# Buck-15.net
KiCad netlist of a schematic drawn in Altium Designer
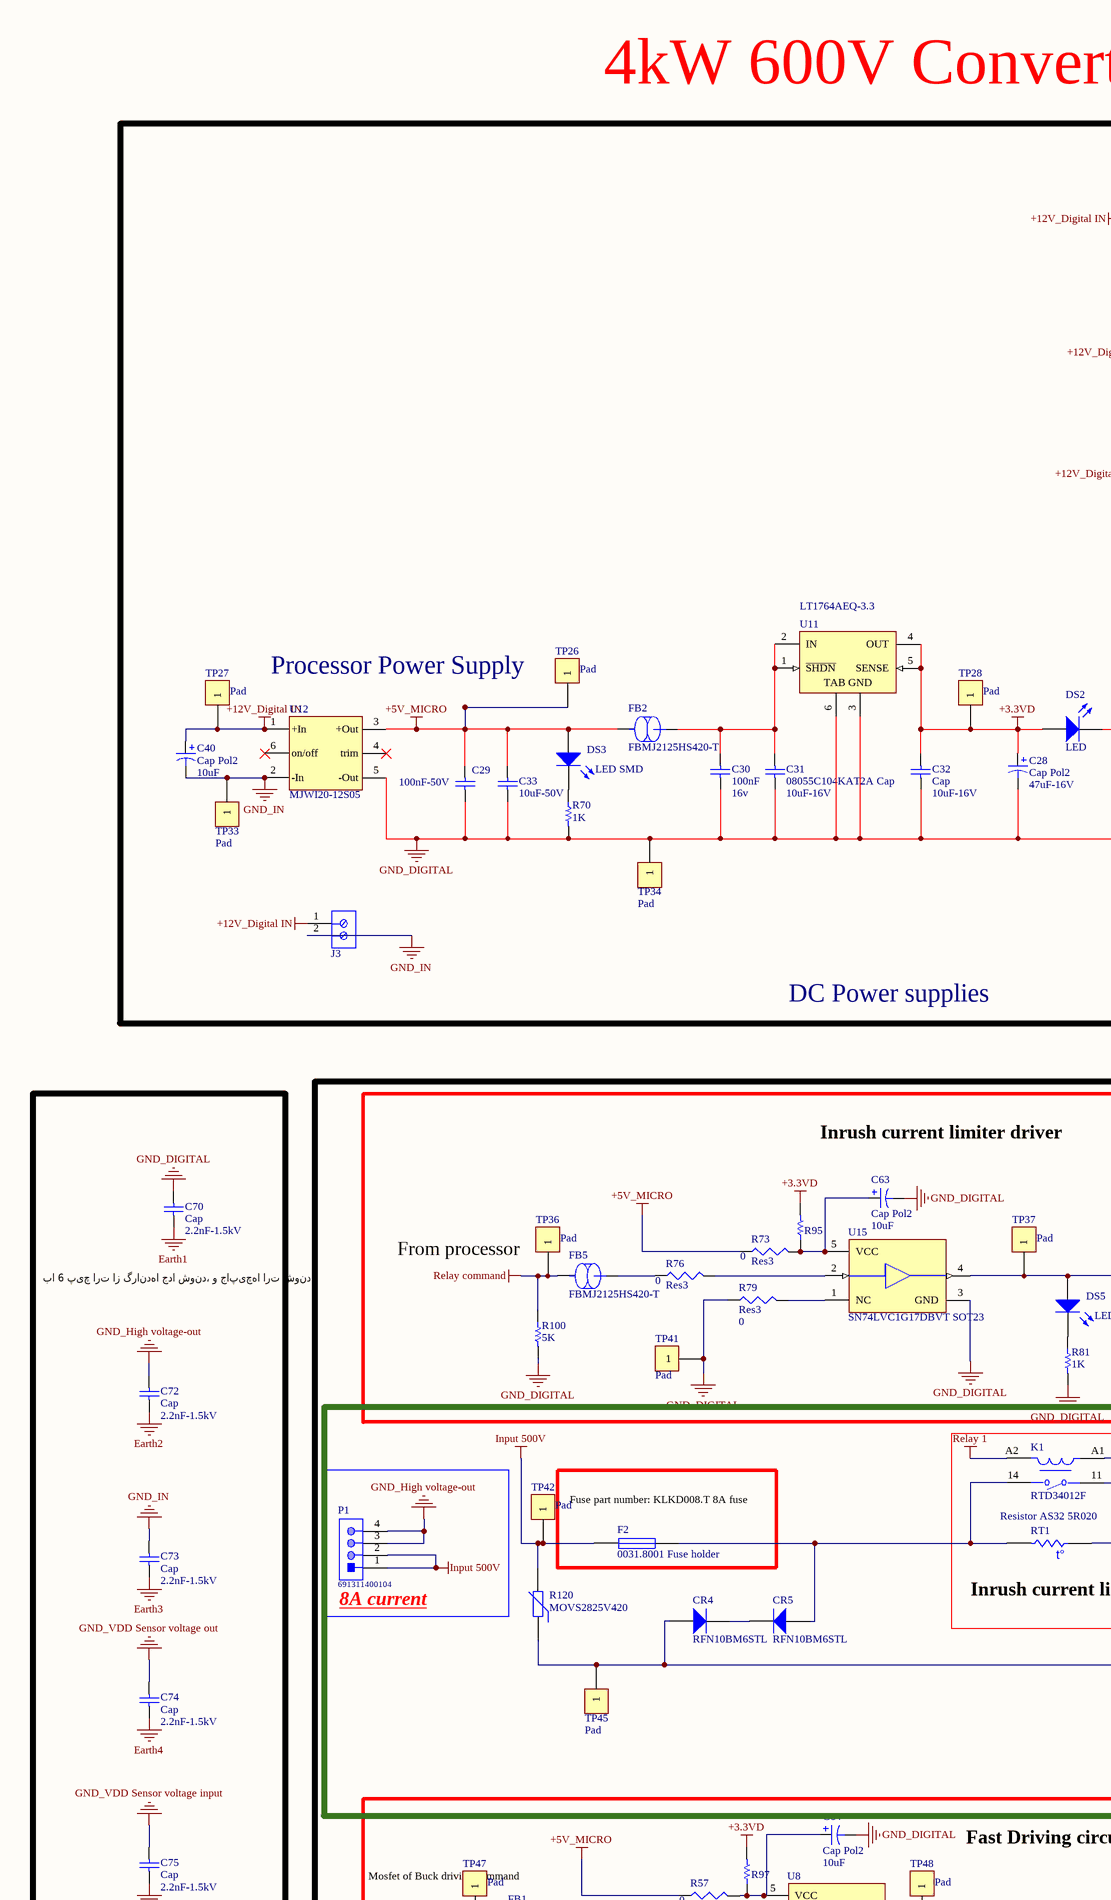
[diagram p0: Buck-15.SchDoc, top left]
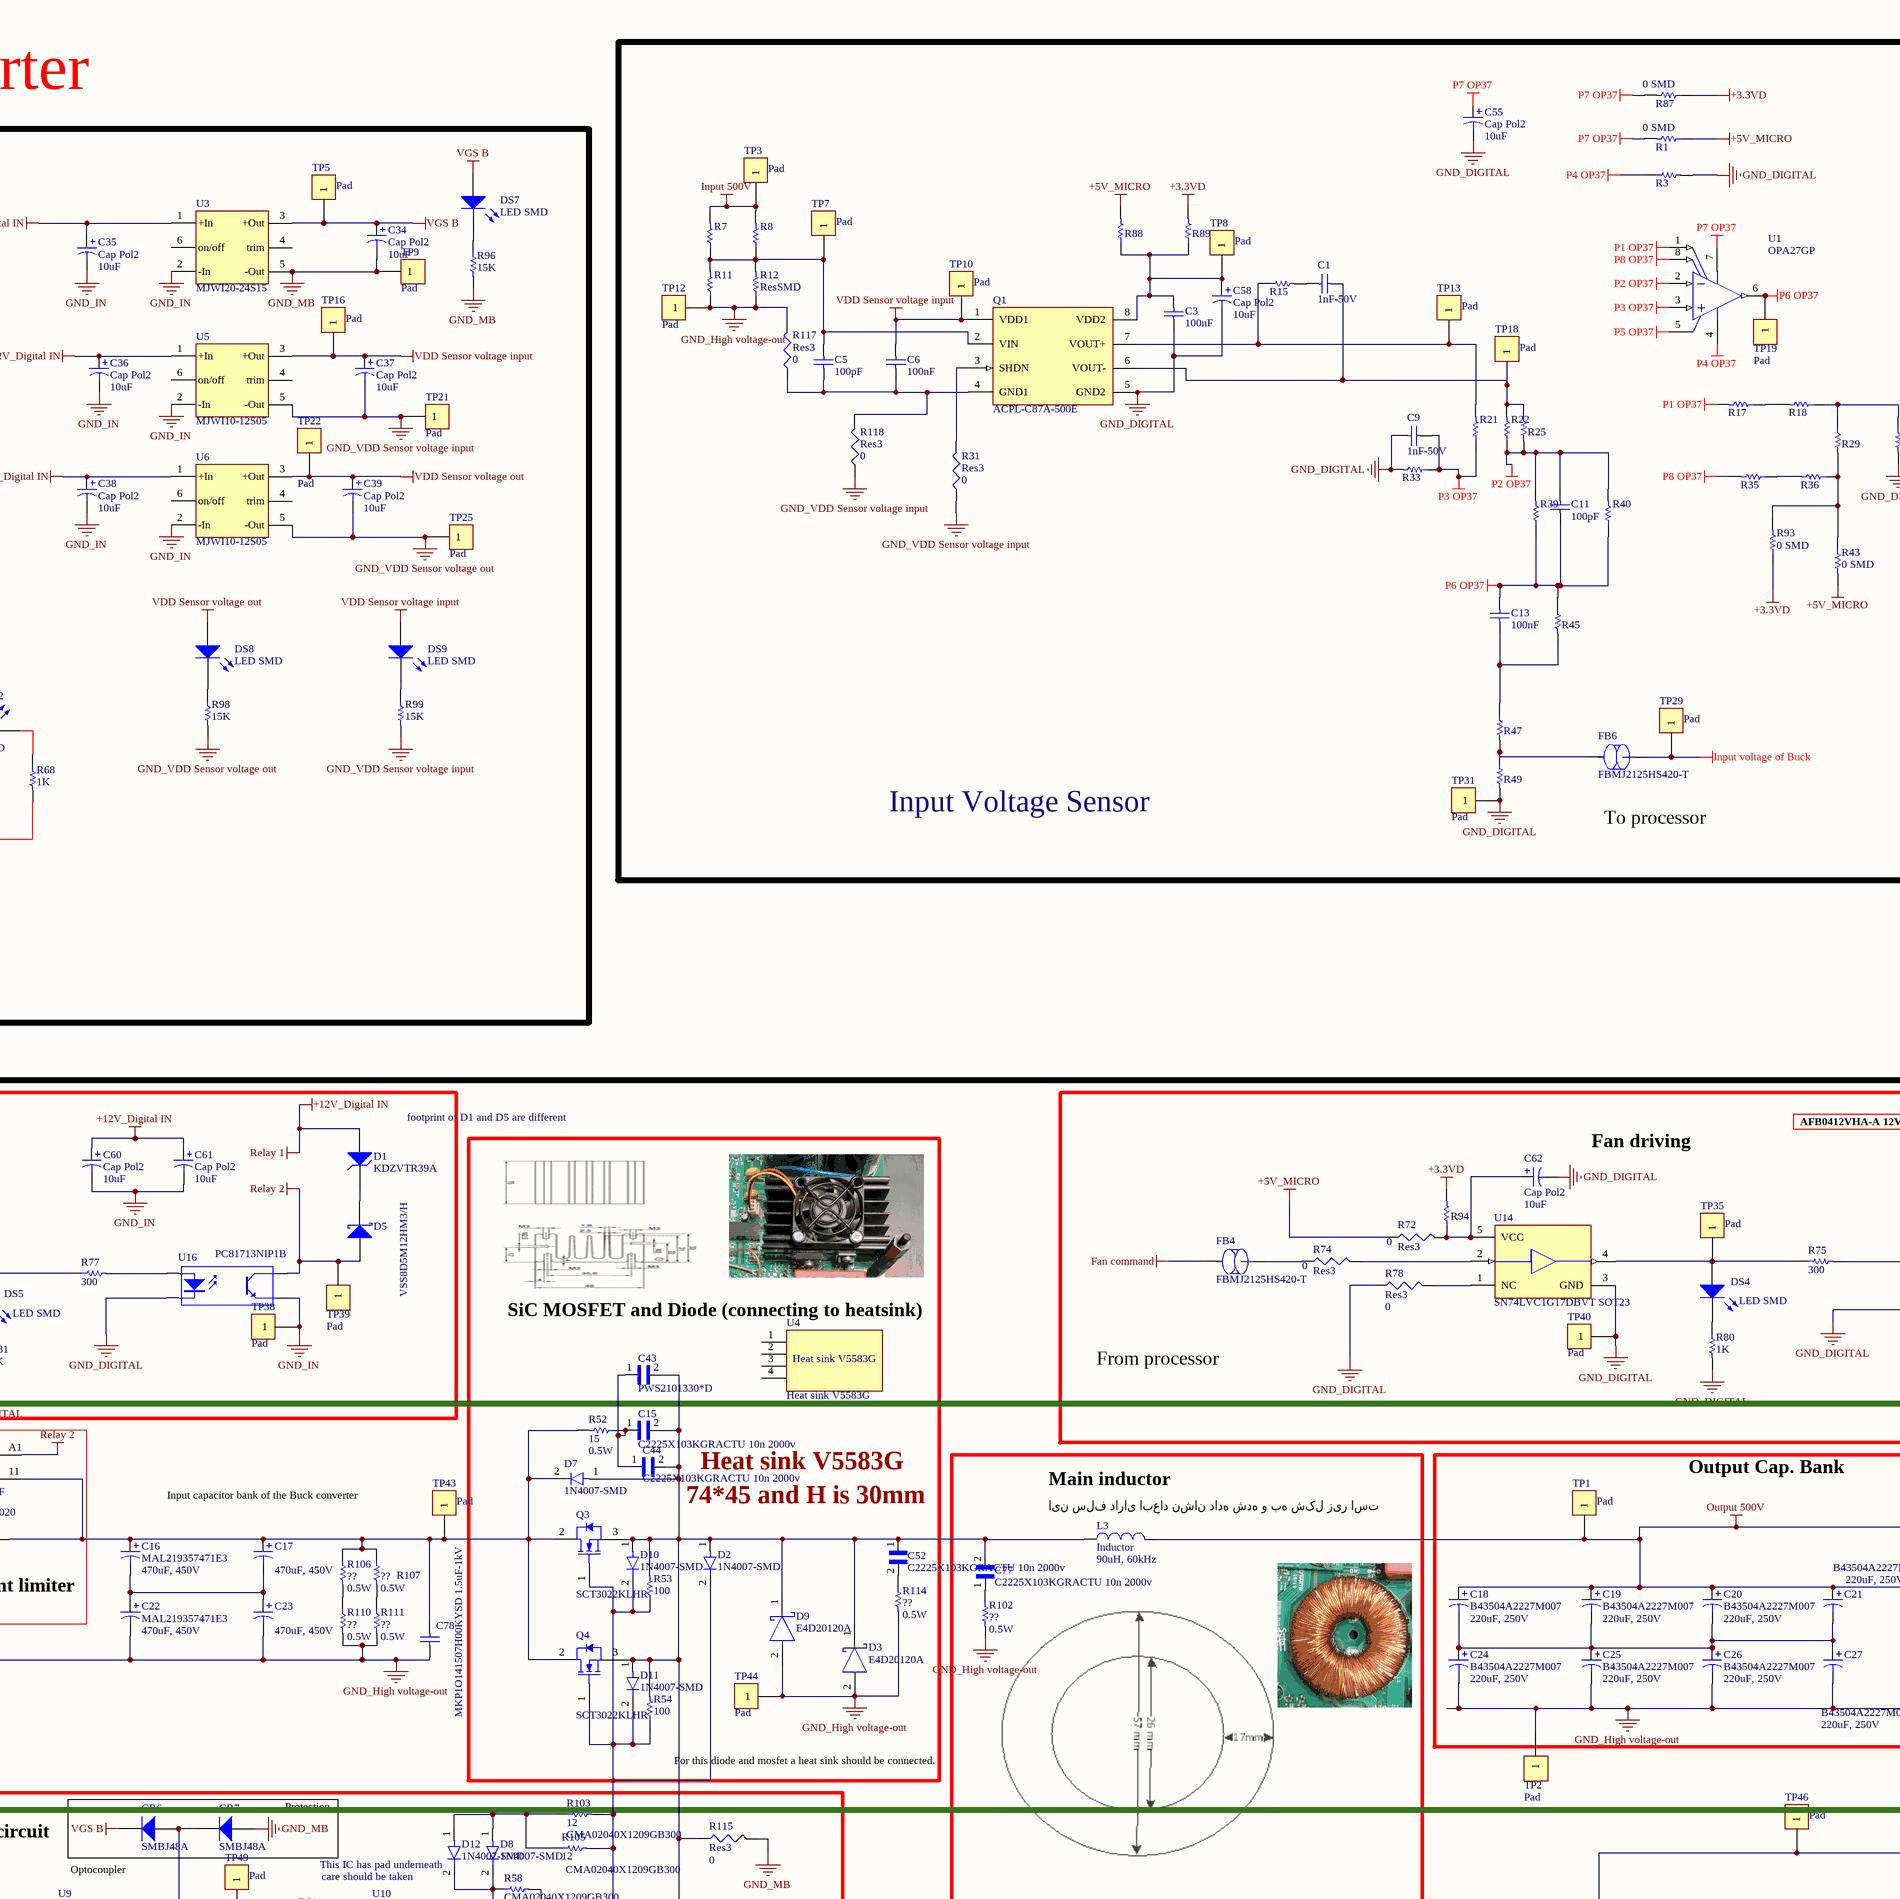
[diagram p1: Buck-15.SchDoc, top middle]
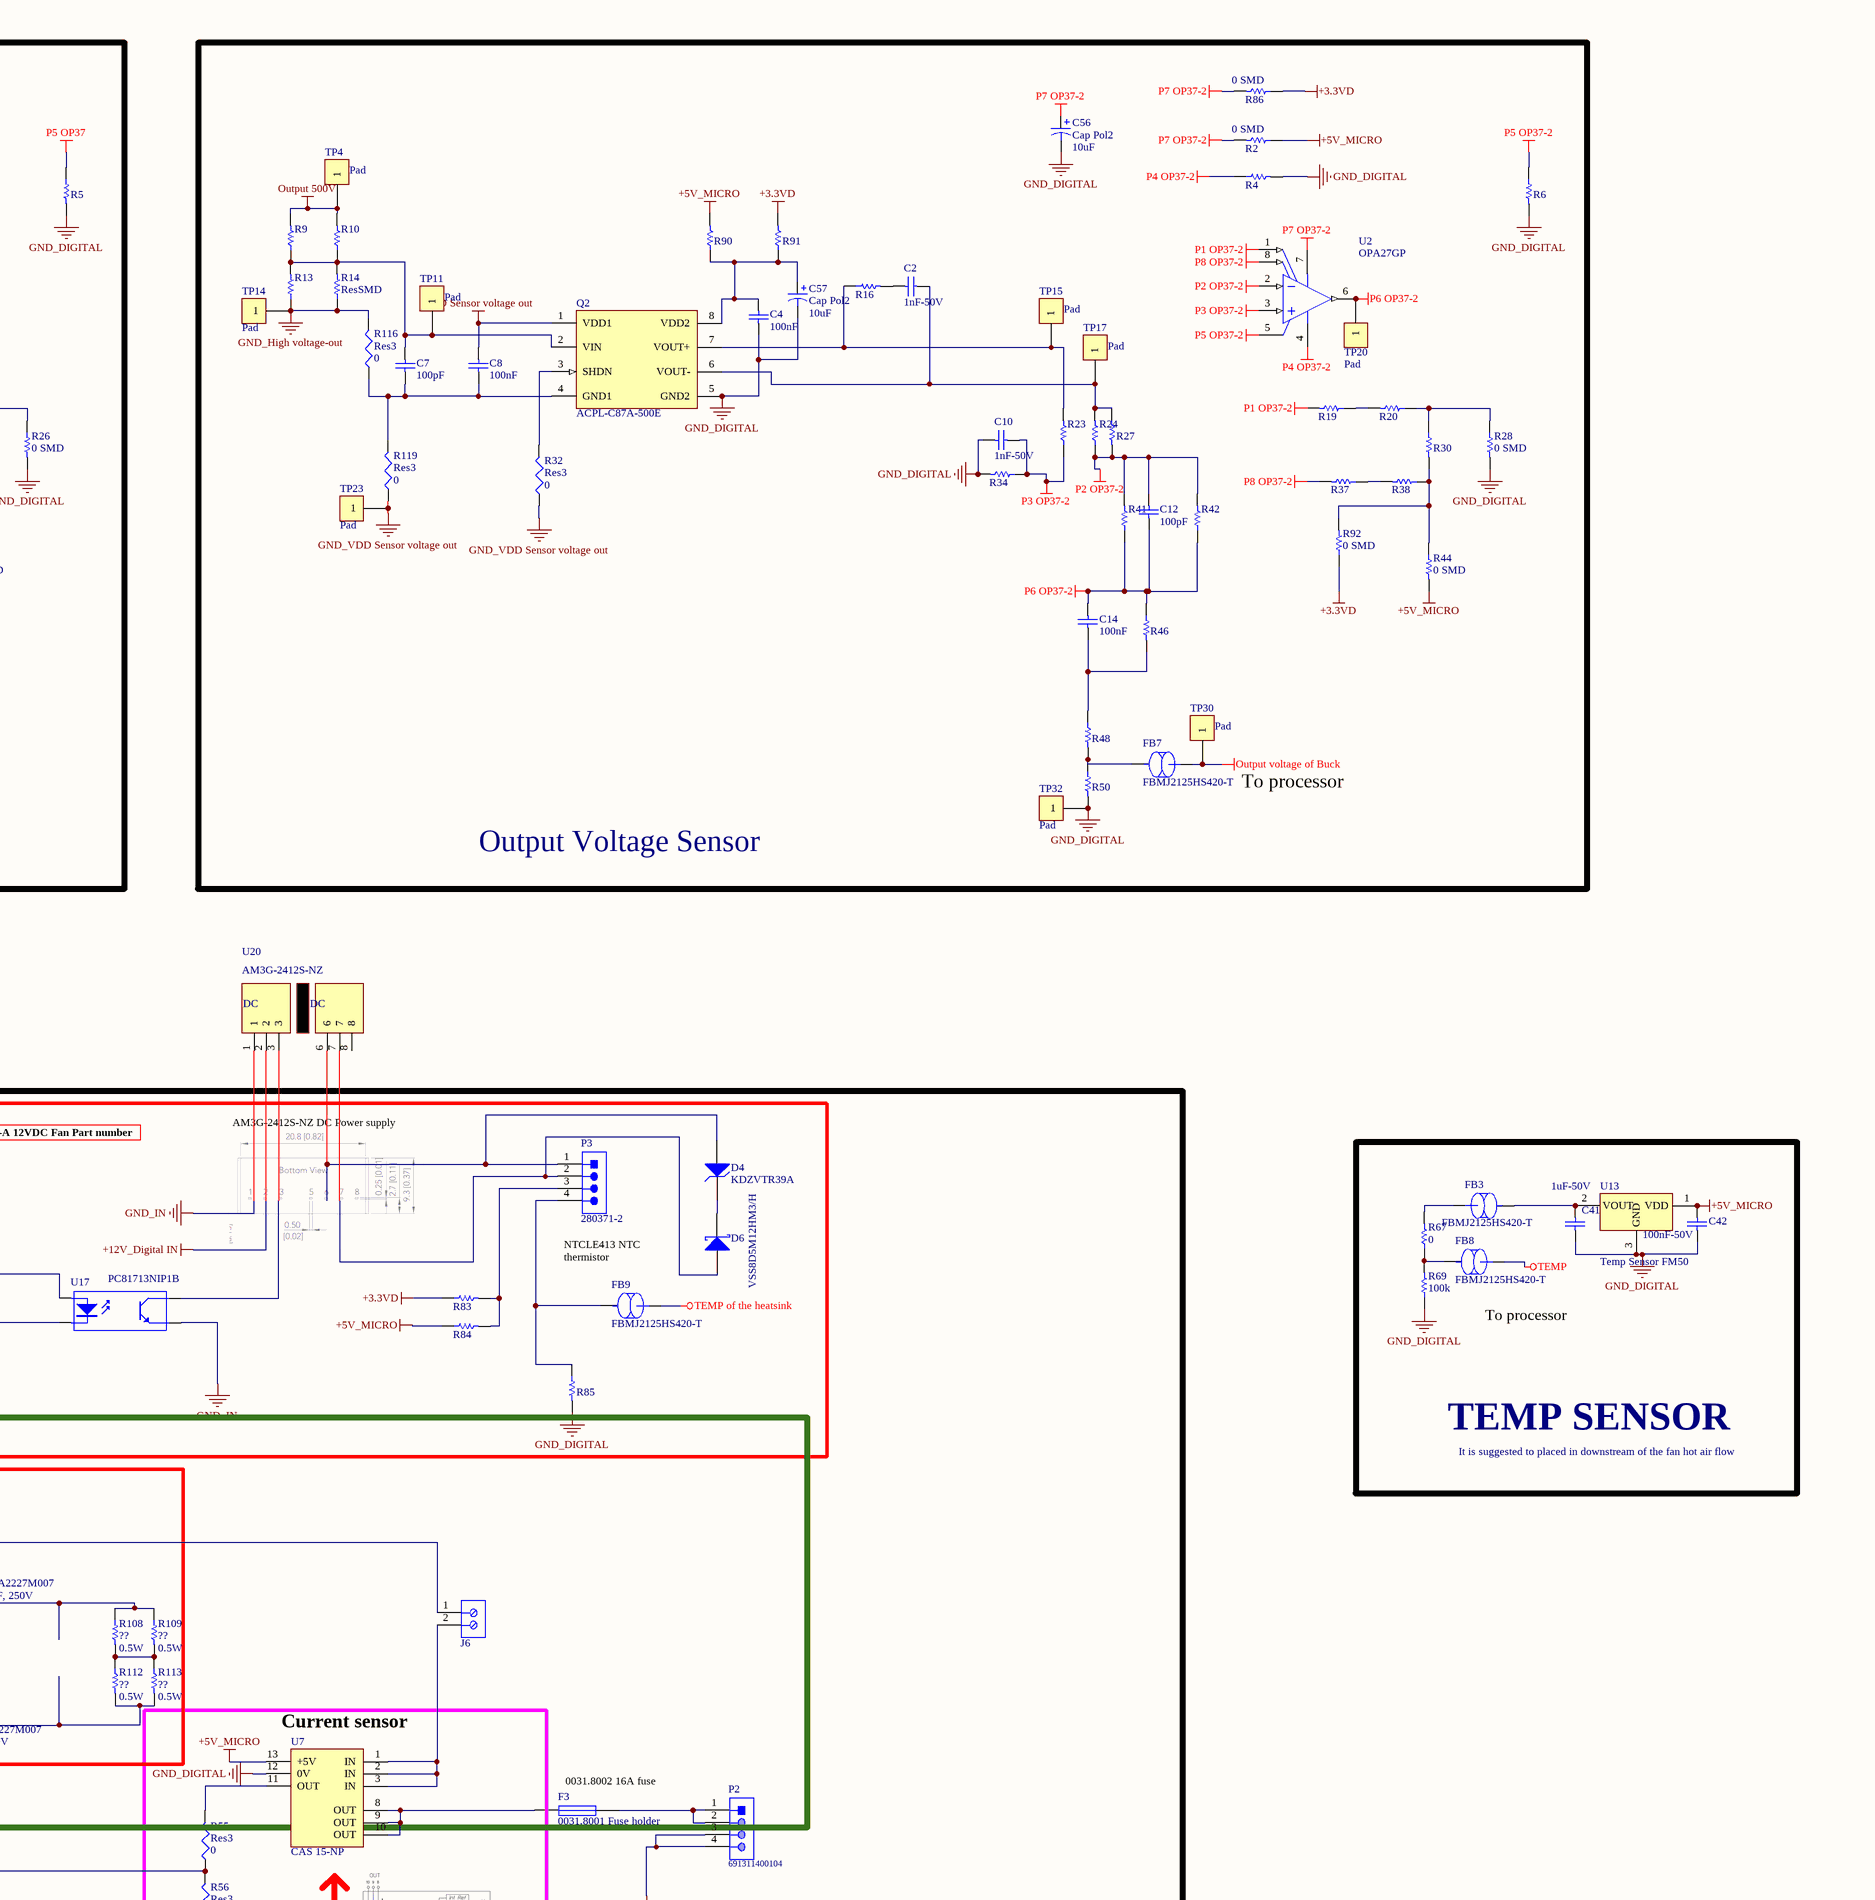
[diagram p2: Buck-15.SchDoc, top right]
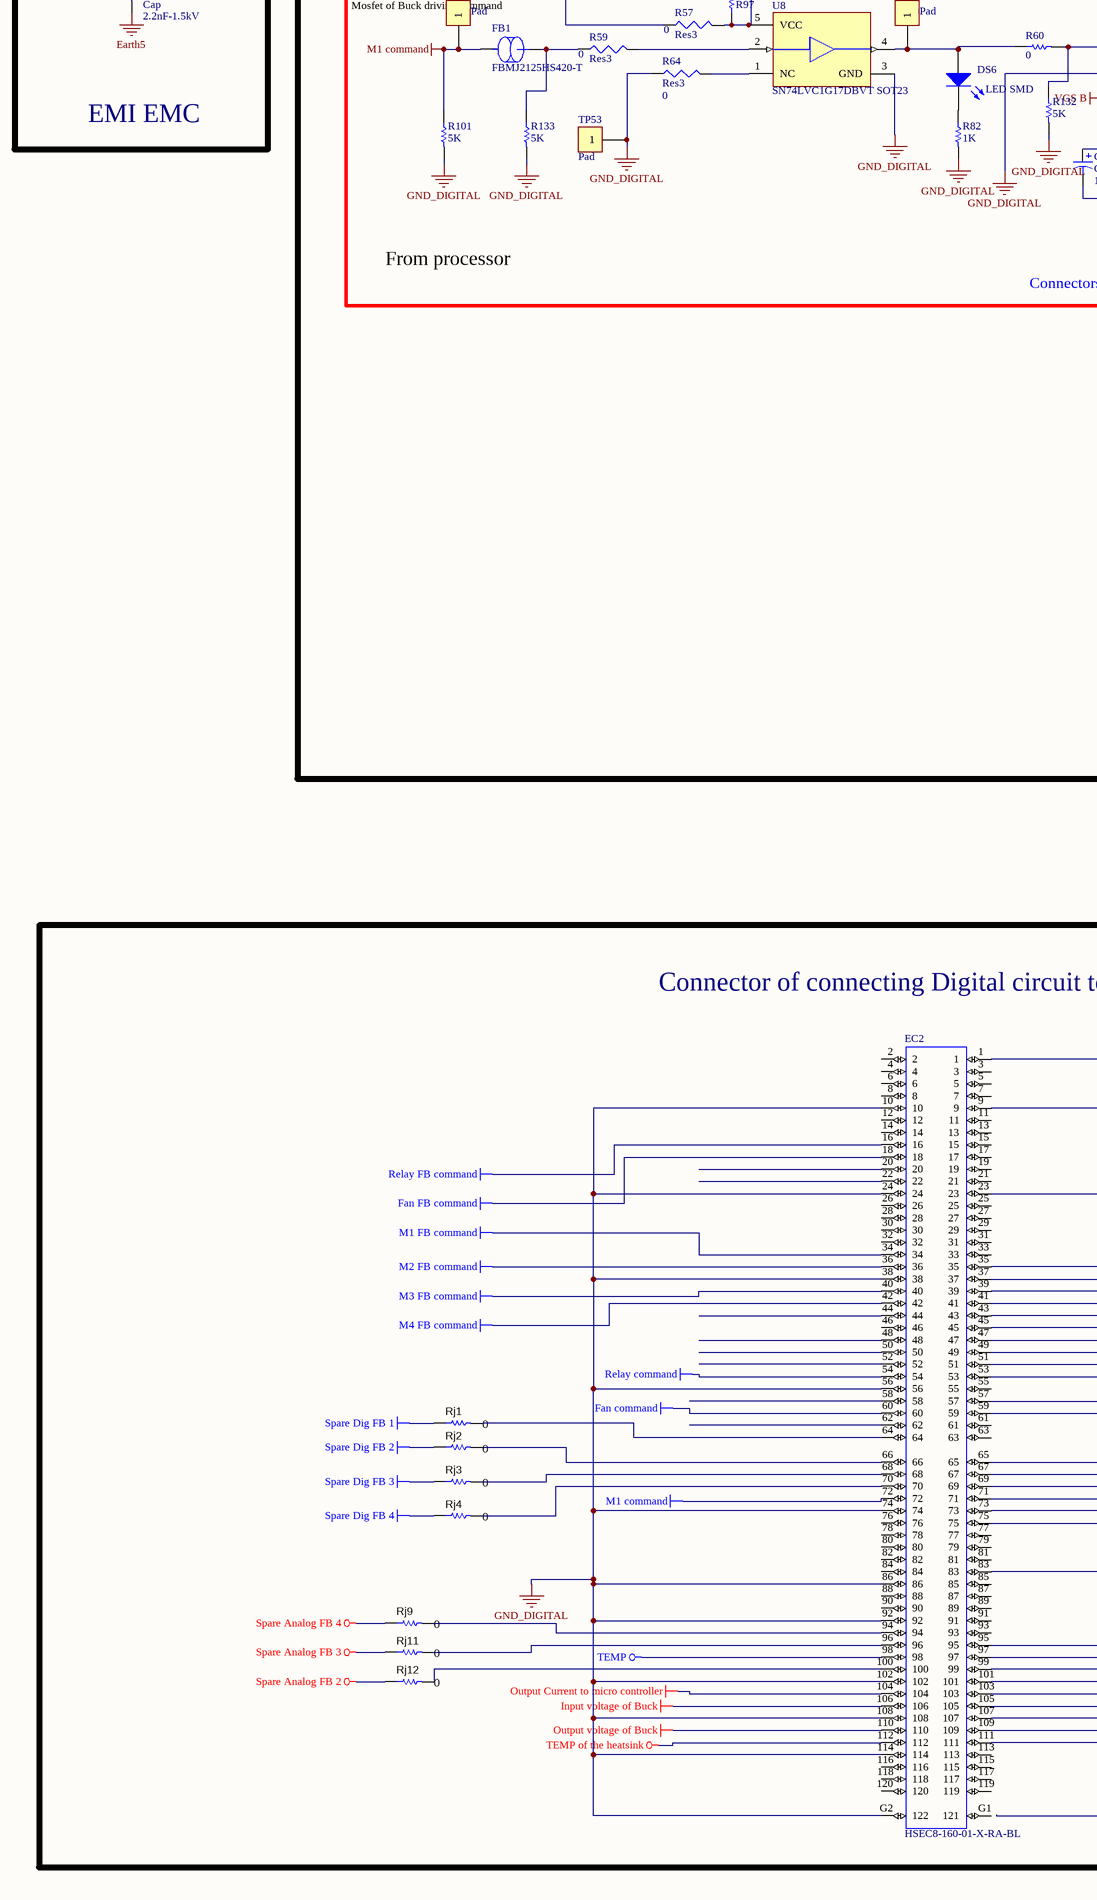
[diagram p3: Buck-15.SchDoc, bottom left]
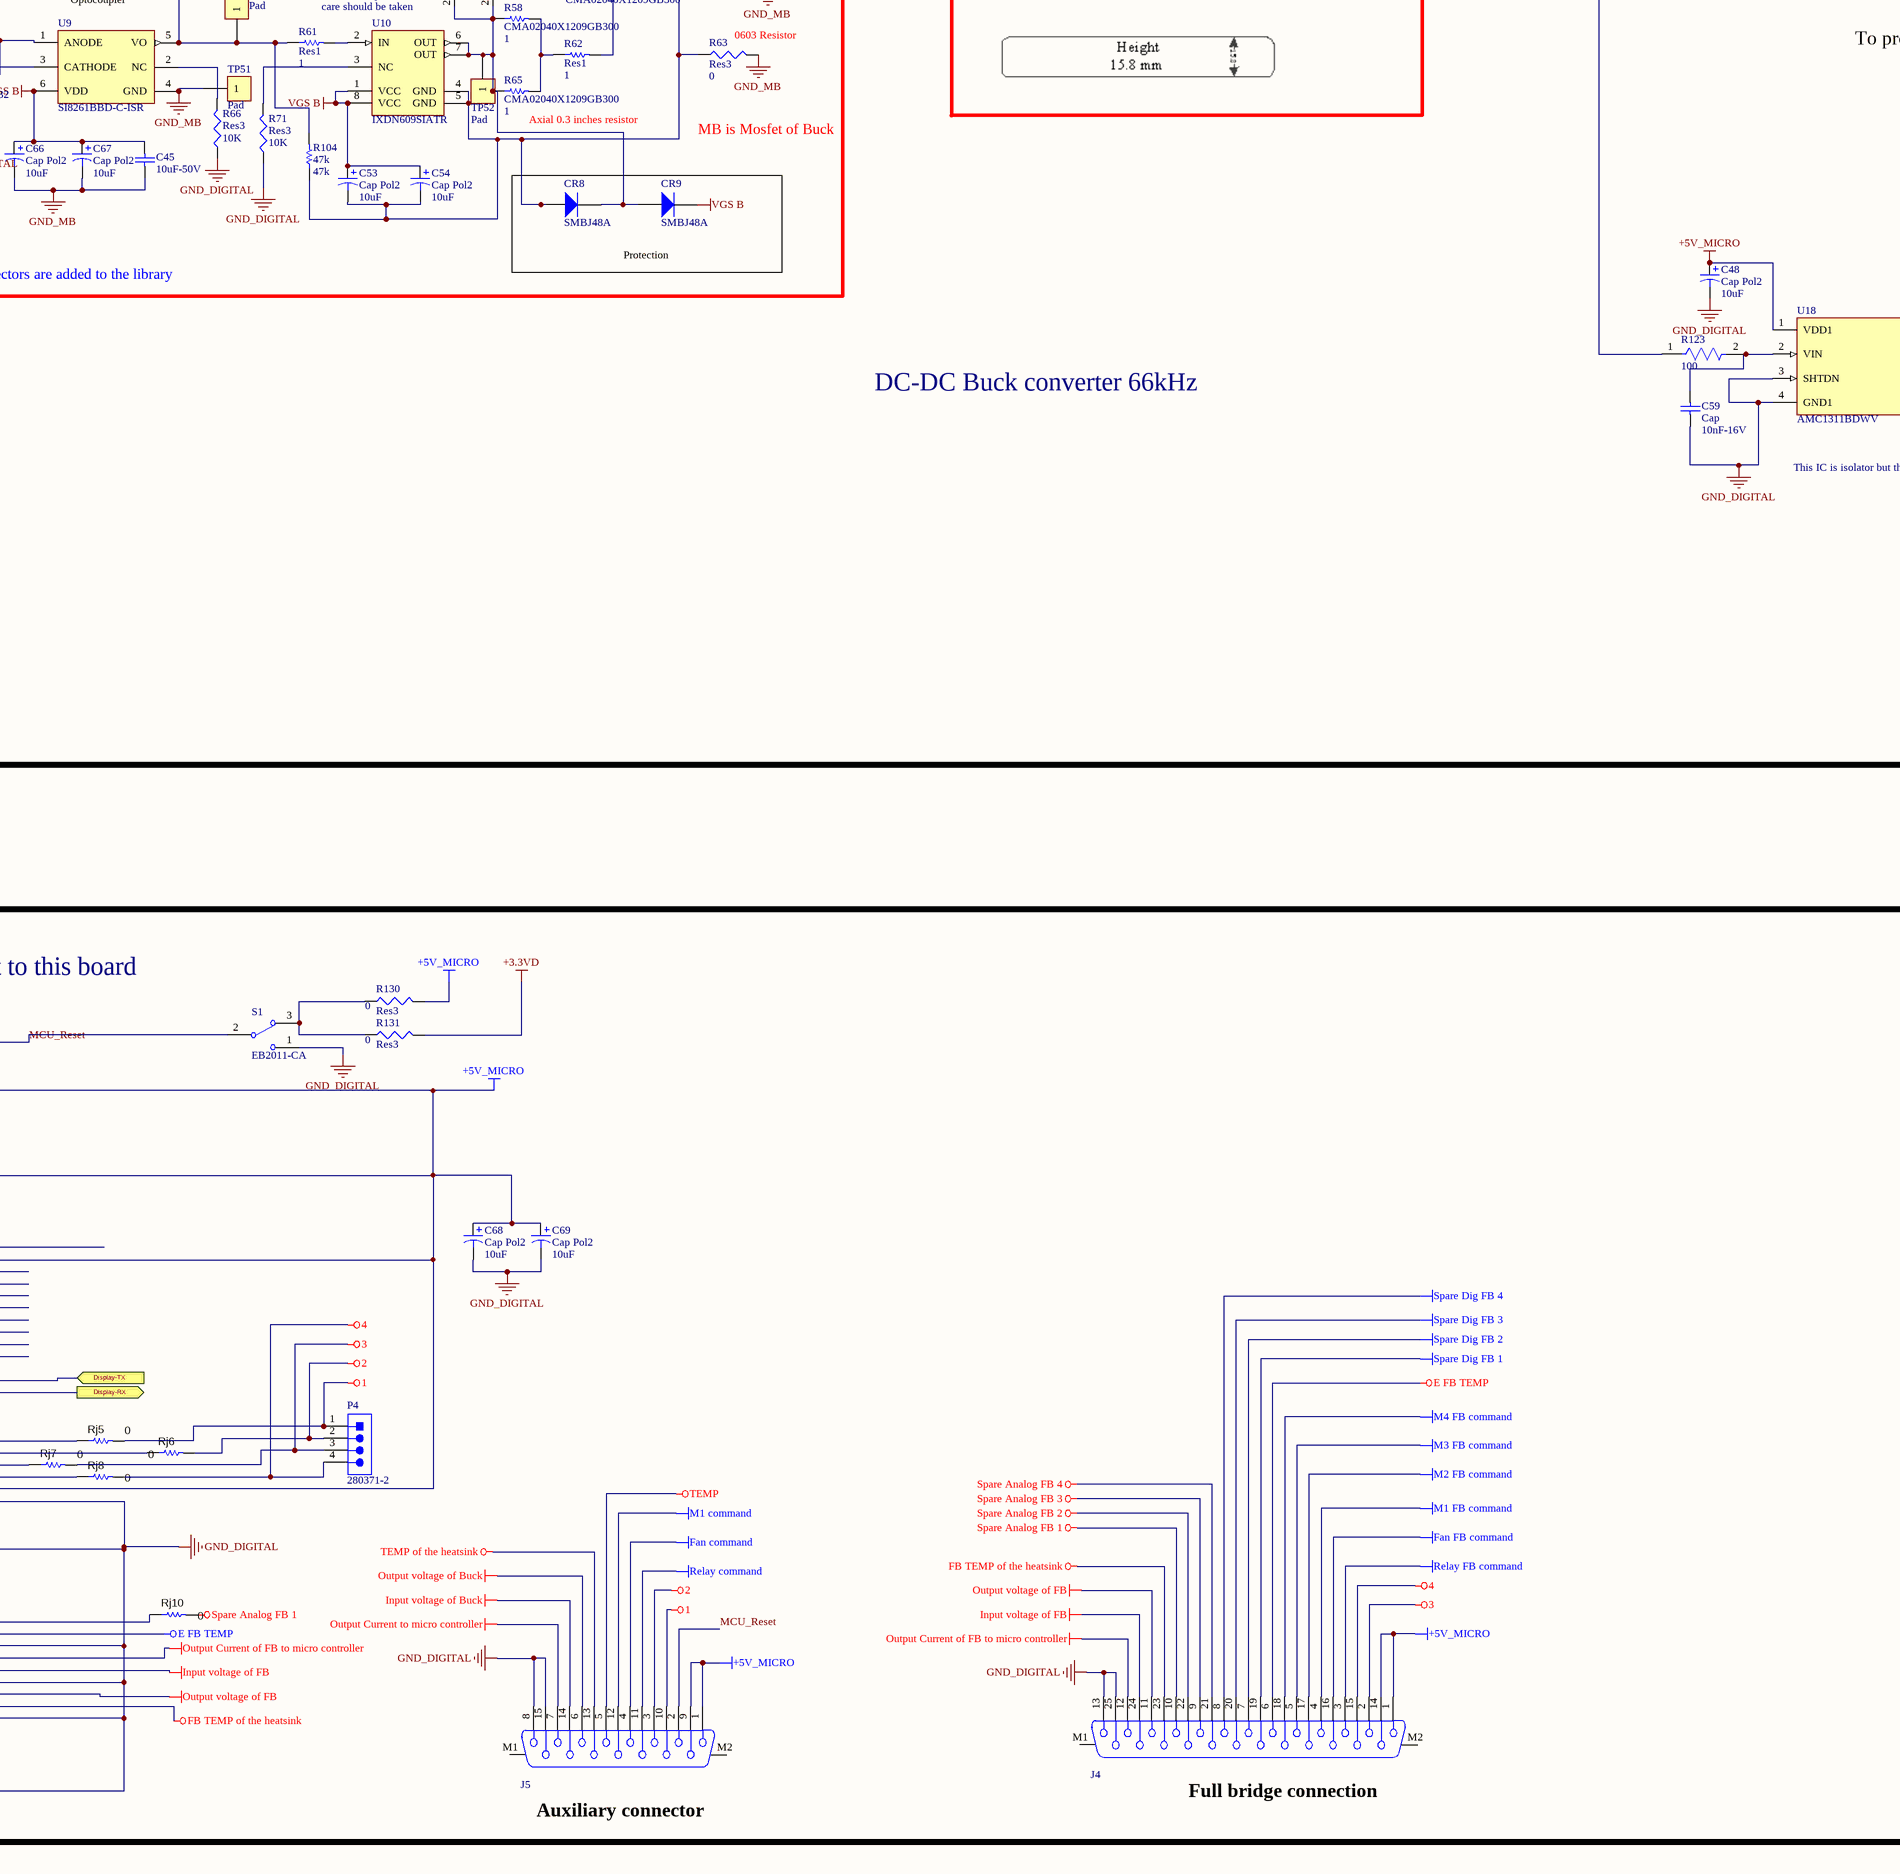
[diagram p4: Buck-15.SchDoc, bottom middle]
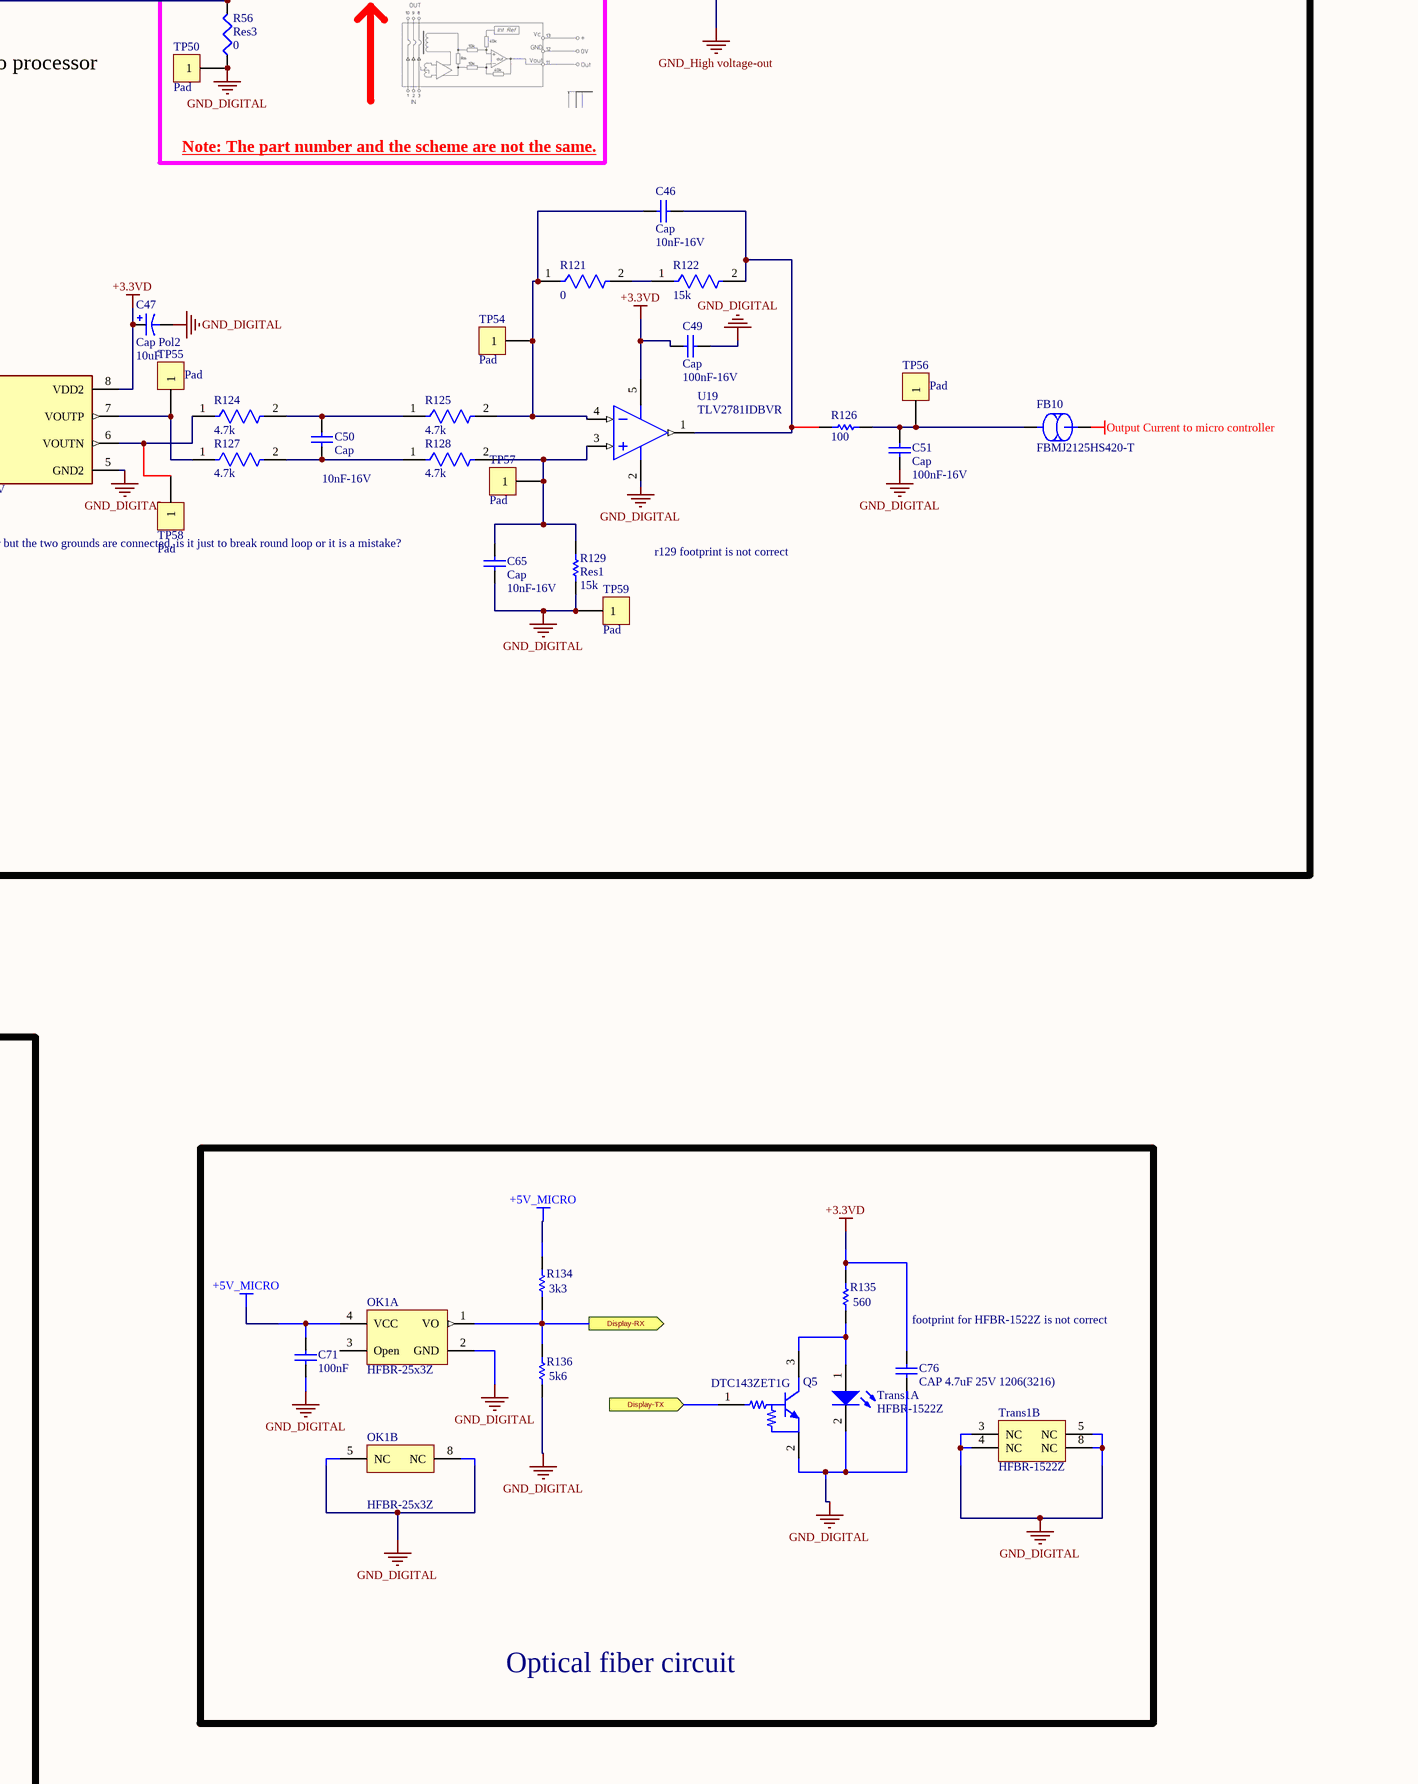
[diagram p5: Buck-15.SchDoc, bottom right]

(export (version "E")
  (design (tool "Eeschema 10.0.6"))
  (components
    (comp (ref "C1") (value "1nF-50V") (footprint "Buck:C0805") (libsource (lib "MYLIB") (part "CapSMD")))
    (comp (ref "C2") (value "1nF-50V") (footprint "Buck:C0805") (libsource (lib "MYLIB") (part "CapSMD")))
    (comp (ref "C3")
      (value "100nF")
      (footprint "Buck:C0805")
      (description "None polar capacitor")
      (libsource (lib "Mylib") (part "Cap ceramic"))
    )
    (comp (ref "C4")
      (value "100nF")
      (footprint "Buck:C0805")
      (description "None polar capacitor")
      (libsource (lib "Mylib") (part "Cap ceramic"))
    )
    (comp (ref "C5")
      (value "100pF")
      (footprint "Buck:C0805")
      (description "None polar capacitor")
      (libsource (lib "Mylib") (part "Cap ceramic"))
    )
    (comp (ref "C6")
      (value "100nF")
      (footprint "Buck:C0805")
      (description "None polar capacitor")
      (libsource (lib "Mylib") (part "Cap ceramic"))
    )
    (comp (ref "C7")
      (value "100pF")
      (footprint "Buck:C0805")
      (description "None polar capacitor")
      (libsource (lib "Mylib") (part "Cap ceramic"))
    )
    (comp (ref "C8")
      (value "100nF")
      (footprint "Buck:C0805")
      (description "None polar capacitor")
      (libsource (lib "Mylib") (part "Cap ceramic"))
    )
    (comp (ref "C9") (value "1nF-50V") (footprint "Buck:C0805") (libsource (lib "MYLIB") (part "CapSMD")))
    (comp (ref "C10") (value "1nF-50V") (footprint "Buck:C0805") (libsource (lib "MYLIB") (part "CapSMD")))
    (comp (ref "C11")
      (value "100pF")
      (footprint "Buck:C0805")
      (description "None polar capacitor")
      (libsource (lib "Mylib") (part "Cap ceramic"))
    )
    (comp (ref "C12")
      (value "100pF")
      (footprint "Buck:C0805")
      (description "None polar capacitor")
      (libsource (lib "Mylib") (part "Cap ceramic"))
    )
    (comp (ref "C13")
      (value "100nF")
      (footprint "Buck:C0805")
      (description "None polar capacitor")
      (libsource (lib "Mylib") (part "Cap ceramic"))
    )
    (comp (ref "C14")
      (value "100nF")
      (footprint "Buck:C0805")
      (description "None polar capacitor")
      (libsource (lib "Mylib") (part "Cap ceramic"))
    )
    (comp (ref "C15")
      (value "C2225X103KGRACTU 10n 2000v")
      (footprint "Buck:C2225")
      (fields (field (name "MF") "AVX") (field (name "MP") "LD052C153JAB2A"))
      (libsource (lib "") (part "Ceramic disk capacitor_1"))
    )
    (comp (ref "C16")
      (value "MAL219357471E3")
      (footprint "Buck:RB-193 PUR-SI-35x50")
      (description "Polarized Capacitor (Axial)")
      (fields (field (name "ALTIUM_VALUE") "470uF, 450V") (field (name "PUBLISHER") "Altium Limited"))
      (libsource (lib "SCH") (part "Cap Pol2"))
    )
    (comp (ref "C17")
      (value "470uF, 450V")
      (footprint "Buck:RB-193 PUR-SI-35x50")
      (description "Polarized Capacitor (Axial)")
      (fields (field (name "Comment") "MAL219357471E3") (field (name "PUBLISHER") "Altium Limited"))
      (libsource (lib "SCH") (part "Cap Pol2"))
    )
    (comp (ref "C18")
      (value "B43504A2227M007")
      (footprint "Buck:RB-B43504")
      (description "Polarized Capacitor (Axial)")
      (fields (field (name "ALTIUM_VALUE") "220uF, 250V") (field (name "PUBLISHER") "Altium Limited"))
      (libsource (lib "SCH") (part "Cap Pol2"))
    )
    (comp (ref "C19")
      (value "B43504A2227M007")
      (footprint "Buck:RB-B43504")
      (description "Polarized Capacitor (Axial)")
      (fields (field (name "ALTIUM_VALUE") "220uF, 250V") (field (name "PUBLISHER") "Altium Limited"))
      (libsource (lib "SCH") (part "Cap Pol2"))
    )
    (comp (ref "C20")
      (value "B43504A2227M007")
      (footprint "Buck:RB-B43504")
      (description "Polarized Capacitor (Axial)")
      (fields (field (name "ALTIUM_VALUE") "220uF, 250V") (field (name "PUBLISHER") "Altium Limited"))
      (libsource (lib "SCH") (part "Cap Pol2"))
    )
    (comp (ref "C21")
      (value "B43504A2227M007")
      (footprint "Buck:RB-B43504")
      (description "Polarized Capacitor (Axial)")
      (fields (field (name "ALTIUM_VALUE") "220uF, 250V") (field (name "PUBLISHER") "Altium Limited"))
      (libsource (lib "SCH") (part "Cap Pol2"))
    )
    (comp (ref "C22")
      (value "MAL219357471E3")
      (footprint "Buck:RB-193 PUR-SI-35x50")
      (description "Polarized Capacitor (Axial)")
      (fields (field (name "ALTIUM_VALUE") "470uF, 450V") (field (name "PUBLISHER") "Altium Limited"))
      (libsource (lib "SCH") (part "Cap Pol2"))
    )
    (comp (ref "C23")
      (value "470uF, 450V")
      (footprint "Buck:RB-193 PUR-SI-35x50")
      (description "Polarized Capacitor (Axial)")
      (fields (field (name "Comment") "MAL219357471E3") (field (name "PUBLISHER") "Altium Limited"))
      (libsource (lib "SCH") (part "Cap Pol2"))
    )
    (comp (ref "C24")
      (value "B43504A2227M007")
      (footprint "Buck:RB-B43504")
      (description "Polarized Capacitor (Axial)")
      (fields (field (name "ALTIUM_VALUE") "220uF, 250V") (field (name "PUBLISHER") "Altium Limited"))
      (libsource (lib "SCH") (part "Cap Pol2"))
    )
    (comp (ref "C25")
      (value "B43504A2227M007")
      (footprint "Buck:RB-B43504")
      (description "Polarized Capacitor (Axial)")
      (fields (field (name "ALTIUM_VALUE") "220uF, 250V") (field (name "PUBLISHER") "Altium Limited"))
      (libsource (lib "SCH") (part "Cap Pol2"))
    )
    (comp (ref "C26")
      (value "B43504A2227M007")
      (footprint "Buck:RB-B43504")
      (description "Polarized Capacitor (Axial)")
      (fields (field (name "ALTIUM_VALUE") "220uF, 250V") (field (name "PUBLISHER") "Altium Limited"))
      (libsource (lib "SCH") (part "Cap Pol2"))
    )
    (comp (ref "C27")
      (value "B43504A2227M007")
      (footprint "Buck:RB-B43504")
      (description "Polarized Capacitor (Axial)")
      (fields (field (name "ALTIUM_VALUE") "220uF, 250V") (field (name "PUBLISHER") "Altium Limited"))
      (libsource (lib "SCH") (part "Cap Pol2"))
    )
    (comp (ref "C28")
      (value "Cap Pol2")
      (footprint "Buck:CAP_Aluminum-G6.3")
      (description "Polarized Capacitor (Axial)")
      (fields (field (name "ALTIUM_VALUE") "47uF-16V") (field (name "PUBLISHER") "Altium Limited"))
      (libsource (lib "SCH") (part "Cap Pol2"))
    )
    (comp (ref "C29") (value "100nF-50V") (footprint "Buck:C0805") (libsource (lib "MYLIB") (part "CapSMD")))
    (comp (ref "C30")
      (value "100nF")
      (footprint "Buck:C0805")
      (description "None polar capacitor")
      (fields (field (name "VOLTE") "16v"))
      (libsource (lib "Mylib") (part "Cap ceramic"))
    )
    (comp (ref "C31")
      (value "08055C104KAT2A Cap")
      (footprint "Buck:C0805")
      (description "Capacitor")
      (fields (field (name "ALTIUM_VALUE") "10uF-16V") (field (name "PUBLISHER") "Altium Limited"))
      (libsource (lib "SCH") (part "Cap"))
    )
    (comp (ref "C32")
      (value "Cap")
      (footprint "Buck:C0805")
      (description "Capacitor")
      (fields (field (name "ALTIUM_VALUE") "10uF-16V") (field (name "PUBLISHER") "Altium Limited"))
      (libsource (lib "SCH") (part "Cap"))
    )
    (comp (ref "C33") (value "10uF-50V") (footprint "Buck:C0805") (libsource (lib "") (part "CapSMD_1")))
    (comp (ref "C34")
      (value "Cap Pol2")
      (footprint "Buck:CAP_Aluminum-G6.3")
      (description "Polarized Capacitor (Axial)")
      (fields (field (name "ALTIUM_VALUE") "10uF") (field (name "PUBLISHER") "Altium Limited"))
      (libsource (lib "SCH") (part "Cap Pol2"))
    )
    (comp (ref "C35")
      (value "Cap Pol2")
      (footprint "Buck:CAP_Aluminum-G6.3")
      (description "Polarized Capacitor (Axial)")
      (fields (field (name "ALTIUM_VALUE") "10uF") (field (name "PUBLISHER") "Altium Limited"))
      (libsource (lib "SCH") (part "Cap Pol2"))
    )
    (comp (ref "C36")
      (value "Cap Pol2")
      (footprint "Buck:CAP_Aluminum-G6.3")
      (description "Polarized Capacitor (Axial)")
      (fields (field (name "ALTIUM_VALUE") "10uF") (field (name "PUBLISHER") "Altium Limited"))
      (libsource (lib "SCH") (part "Cap Pol2"))
    )
    (comp (ref "C37")
      (value "Cap Pol2")
      (footprint "Buck:CAP_Aluminum-G6.3")
      (description "Polarized Capacitor (Axial)")
      (fields (field (name "ALTIUM_VALUE") "10uF") (field (name "PUBLISHER") "Altium Limited"))
      (libsource (lib "SCH") (part "Cap Pol2"))
    )
    (comp (ref "C38")
      (value "Cap Pol2")
      (footprint "Buck:CAP_Aluminum-G6.3")
      (description "Polarized Capacitor (Axial)")
      (fields (field (name "ALTIUM_VALUE") "10uF") (field (name "PUBLISHER") "Altium Limited"))
      (libsource (lib "SCH") (part "Cap Pol2"))
    )
    (comp (ref "C39")
      (value "Cap Pol2")
      (footprint "Buck:CAP_Aluminum-G6.3")
      (description "Polarized Capacitor (Axial)")
      (fields (field (name "ALTIUM_VALUE") "10uF") (field (name "PUBLISHER") "Altium Limited"))
      (libsource (lib "SCH") (part "Cap Pol2"))
    )
    (comp (ref "C40")
      (value "Cap Pol2")
      (footprint "Buck:CAP_Aluminum-G6.3")
      (description "Polarized Capacitor (Axial)")
      (fields (field (name "ALTIUM_VALUE") "10uF") (field (name "PUBLISHER") "Altium Limited"))
      (libsource (lib "SCH") (part "Cap Pol2"))
    )
    (comp (ref "C41") (value "1uF-50V") (footprint "Buck:C0805") (libsource (lib "MYLIB") (part "CapSMD")))
    (comp (ref "C42") (value "100nF-50V") (footprint "Buck:C0805") (libsource (lib "MYLIB") (part "CapSMD")))
    (comp (ref "C43")
      (value "PWS2101330*D")
      (footprint "Buck:AXIAL0.9")
      (fields (field (name "MF") "AVX") (field (name "MP") "LD052C153JAB2A"))
      (libsource (lib "") (part "Ceramic disk capacitor_1"))
    )
    (comp (ref "C44")
      (value "C2225X103KGRACTU 10n 2000v")
      (footprint "Buck:C2225")
      (fields (field (name "MF") "AVX") (field (name "MP") "LD052C153JAB2A"))
      (libsource (lib "") (part "Ceramic disk capacitor_1"))
    )
    (comp (ref "C45") (value "10uF-50V") (footprint "Buck:C0805") (libsource (lib "") (part "CapSMD_1")))
    (comp (ref "C46")
      (value "Cap")
      (footprint "Buck:C0805")
      (description "Capacitor")
      (fields (field (name "ALTIUM_VALUE") "10nF-16V") (field (name "PUBLISHER") "Altium Limited"))
      (libsource (lib "SCH") (part "Cap"))
    )
    (comp (ref "C47")
      (value "Cap Pol2")
      (footprint "Buck:CAP_Aluminum-G6.3")
      (description "Polarized Capacitor (Axial)")
      (fields (field (name "ALTIUM_VALUE") "10uF") (field (name "PUBLISHER") "Altium Limited"))
      (libsource (lib "SCH") (part "Cap Pol2"))
    )
    (comp (ref "C48")
      (value "Cap Pol2")
      (footprint "Buck:CAP_Aluminum-G6.3")
      (description "Polarized Capacitor (Axial)")
      (fields (field (name "ALTIUM_VALUE") "10uF") (field (name "PUBLISHER") "Altium Limited"))
      (libsource (lib "SCH") (part "Cap Pol2"))
    )
    (comp (ref "C49")
      (value "Cap")
      (footprint "Buck:C0805")
      (description "Capacitor")
      (fields (field (name "ALTIUM_VALUE") "100nF-16V") (field (name "PUBLISHER") "Altium Limited"))
      (libsource (lib "SCH") (part "Cap"))
    )
    (comp (ref "C50")
      (value "Cap")
      (footprint "Buck:C0805")
      (description "Capacitor")
      (fields (field (name "ALTIUM_VALUE") "10nF-16V") (field (name "PUBLISHER") "Altium Limited"))
      (libsource (lib "SCH") (part "Cap"))
    )
    (comp (ref "C51")
      (value "Cap")
      (footprint "Buck:C0805")
      (description "Capacitor")
      (fields (field (name "ALTIUM_VALUE") "100nF-16V") (field (name "PUBLISHER") "Altium Limited"))
      (libsource (lib "SCH") (part "Cap"))
    )
    (comp (ref "C52")
      (value "C2225X103KGRACTU 10n 2000v")
      (footprint "Buck:C2225")
      (fields (field (name "MF") "AVX") (field (name "MP") "LD052C153JAB2A"))
      (libsource (lib "") (part "Ceramic disk capacitor_2"))
    )
    (comp (ref "C53")
      (value "Cap Pol2")
      (footprint "Buck:CAP_Aluminum-G6.3")
      (description "Polarized Capacitor (Axial)")
      (fields (field (name "ALTIUM_VALUE") "10uF") (field (name "PUBLISHER") "Altium Limited"))
      (libsource (lib "SCH") (part "Cap Pol2"))
    )
    (comp (ref "C54")
      (value "Cap Pol2")
      (footprint "Buck:CAP_Aluminum-G6.3")
      (description "Polarized Capacitor (Axial)")
      (fields (field (name "ALTIUM_VALUE") "10uF") (field (name "PUBLISHER") "Altium Limited"))
      (libsource (lib "SCH") (part "Cap Pol2"))
    )
    (comp (ref "C55")
      (value "Cap Pol2")
      (footprint "Buck:CAP_Aluminum-G6.3")
      (description "Polarized Capacitor (Axial)")
      (fields (field (name "ALTIUM_VALUE") "10uF") (field (name "PUBLISHER") "Altium Limited"))
      (libsource (lib "SCH") (part "Cap Pol2"))
    )
    (comp (ref "C56")
      (value "Cap Pol2")
      (footprint "Buck:CAP_Aluminum-G6.3")
      (description "Polarized Capacitor (Axial)")
      (fields (field (name "ALTIUM_VALUE") "10uF") (field (name "PUBLISHER") "Altium Limited"))
      (libsource (lib "SCH") (part "Cap Pol2"))
    )
    (comp (ref "C57")
      (value "Cap Pol2")
      (footprint "Buck:CAP_Aluminum-G6.3")
      (description "Polarized Capacitor (Axial)")
      (fields (field (name "ALTIUM_VALUE") "10uF") (field (name "PUBLISHER") "Altium Limited"))
      (libsource (lib "SCH") (part "Cap Pol2"))
    )
    (comp (ref "C58")
      (value "Cap Pol2")
      (footprint "Buck:CAP_Aluminum-G6.3")
      (description "Polarized Capacitor (Axial)")
      (fields (field (name "ALTIUM_VALUE") "10uF") (field (name "PUBLISHER") "Altium Limited"))
      (libsource (lib "SCH") (part "Cap Pol2"))
    )
    (comp (ref "C59")
      (value "Cap")
      (footprint "Buck:C0805")
      (description "Capacitor")
      (fields (field (name "ALTIUM_VALUE") "10nF-16V") (field (name "PUBLISHER") "Altium Limited"))
      (libsource (lib "SCH") (part "Cap"))
    )
    (comp (ref "C60")
      (value "Cap Pol2")
      (footprint "Buck:CAP_Aluminum-G6.3")
      (description "Polarized Capacitor (Axial)")
      (fields (field (name "ALTIUM_VALUE") "10uF") (field (name "PUBLISHER") "Altium Limited"))
      (libsource (lib "SCH") (part "Cap Pol2"))
    )
    (comp (ref "C61")
      (value "Cap Pol2")
      (footprint "Buck:CAP_Aluminum-G6.3")
      (description "Polarized Capacitor (Axial)")
      (fields (field (name "ALTIUM_VALUE") "10uF") (field (name "PUBLISHER") "Altium Limited"))
      (libsource (lib "SCH") (part "Cap Pol2"))
    )
    (comp (ref "C62")
      (value "Cap Pol2")
      (footprint "Buck:CAP_Aluminum-G6.3")
      (description "Polarized Capacitor (Axial)")
      (fields (field (name "ALTIUM_VALUE") "10uF") (field (name "PUBLISHER") "Altium Limited"))
      (libsource (lib "SCH") (part "Cap Pol2"))
    )
    (comp (ref "C63")
      (value "Cap Pol2")
      (footprint "Buck:CAP_Aluminum-G6.3")
      (description "Polarized Capacitor (Axial)")
      (fields (field (name "ALTIUM_VALUE") "10uF") (field (name "PUBLISHER") "Altium Limited"))
      (libsource (lib "SCH") (part "Cap Pol2"))
    )
    (comp (ref "C64")
      (value "Cap Pol2")
      (footprint "Buck:CAP_Aluminum-G6.3")
      (description "Polarized Capacitor (Axial)")
      (fields (field (name "ALTIUM_VALUE") "10uF") (field (name "PUBLISHER") "Altium Limited"))
      (libsource (lib "SCH") (part "Cap Pol2"))
    )
    (comp (ref "C65")
      (value "Cap")
      (footprint "Buck:C0805")
      (description "Capacitor")
      (fields (field (name "ALTIUM_VALUE") "10nF-16V") (field (name "PUBLISHER") "Altium Limited"))
      (libsource (lib "SCH") (part "Cap"))
    )
    (comp (ref "C66")
      (value "Cap Pol2")
      (footprint "Buck:CAP_Aluminum-G6.3")
      (description "Polarized Capacitor (Axial)")
      (fields (field (name "ALTIUM_VALUE") "10uF") (field (name "PUBLISHER") "Altium Limited"))
      (libsource (lib "SCH") (part "Cap Pol2"))
    )
    (comp (ref "C67")
      (value "Cap Pol2")
      (footprint "Buck:CAP_Aluminum-G6.3")
      (description "Polarized Capacitor (Axial)")
      (fields (field (name "ALTIUM_VALUE") "10uF") (field (name "PUBLISHER") "Altium Limited"))
      (libsource (lib "SCH") (part "Cap Pol2"))
    )
    (comp (ref "C68")
      (value "Cap Pol2")
      (footprint "Buck:CAP_Aluminum-G6.3")
      (description "Polarized Capacitor (Axial)")
      (fields (field (name "ALTIUM_VALUE") "10uF") (field (name "PUBLISHER") "Altium Limited"))
      (libsource (lib "SCH") (part "Cap Pol2"))
    )
    (comp (ref "C69")
      (value "Cap Pol2")
      (footprint "Buck:CAP_Aluminum-G6.3")
      (description "Polarized Capacitor (Axial)")
      (fields (field (name "ALTIUM_VALUE") "10uF") (field (name "PUBLISHER") "Altium Limited"))
      (libsource (lib "SCH") (part "Cap Pol2"))
    )
    (comp (ref "C70")
      (value "Cap")
      (footprint "Buck:RAD_13X4X9_P10")
      (description "Capacitor")
      (fields (field (name "AY1222M47Y5UC63L0") "2.2nF-1.5kV") (field (name "PUBLISHER") "Altium Limited"))
      (libsource (lib "SCH") (part "Cap"))
    )
    (comp (ref "C71")
      (value "100nF")
      (footprint "Buck:C0805")
      (description "None polar capacitor")
      (libsource (lib "Mylib") (part "Cap ceramic"))
    )
    (comp (ref "C72")
      (value "Cap")
      (footprint "Buck:RAD_13X4X9_P10")
      (description "Capacitor")
      (fields (field (name "AY1222M47Y5UC63L0") "2.2nF-1.5kV") (field (name "PUBLISHER") "Altium Limited"))
      (libsource (lib "SCH") (part "Cap"))
    )
    (comp (ref "C73")
      (value "Cap")
      (footprint "Buck:RAD_13X4X9_P10")
      (description "Capacitor")
      (fields (field (name "AY1222M47Y5UC63L0") "2.2nF-1.5kV") (field (name "PUBLISHER") "Altium Limited"))
      (libsource (lib "SCH") (part "Cap"))
    )
    (comp (ref "C74")
      (value "Cap")
      (footprint "Buck:RAD_13X4X9_P10")
      (description "Capacitor")
      (fields (field (name "AY1222M47Y5UC63L0") "2.2nF-1.5kV") (field (name "PUBLISHER") "Altium Limited"))
      (libsource (lib "SCH") (part "Cap"))
    )
    (comp (ref "C75")
      (value "Cap")
      (footprint "Buck:RAD_13X4X9_P10")
      (description "Capacitor")
      (fields (field (name "AY1222M47Y5UC63L0") "2.2nF-1.5kV") (field (name "PUBLISHER") "Altium Limited"))
      (libsource (lib "SCH") (part "Cap"))
    )
    (comp (ref "C76")
      (value "CAP 4.7uF 25V 1206(3216)")
      (footprint "Buck:C1206")
      (description "CAP 4.7uF 25V ±5% 1206 (3216 Metric) Thickness 1.9mm SMD")
      (fields (field (name "TOLERANCE") "Â±5%"))
      (libsource (lib "Miscellaneous Devices") (part "CAP"))
    )
    (comp (ref "C77")
      (value "C2225X103KGRACTU 10n 2000v")
      (footprint "Buck:C2225")
      (fields (field (name "MF") "AVX") (field (name "MP") "LD052C153JAB2A"))
      (libsource (lib "Capacitors dip") (part "Ceramic disk capacitor"))
    )
    (comp (ref "C78")
      (value "MKP1O141507H00KYSD 1.5uF-1kV")
      (footprint "Buck:RAD_41.5X24X45.5_P37.5")
      (libsource (lib "MYLIB") (part "CapSMD"))
    )
    (comp (ref "CR4")
      (value "RFN10BM6STL")
      (footprint "Buck:RFN10BM")
      (libsource (lib "MYLIB") (part "DiodeSMD4.5mm"))
    )
    (comp (ref "CR5")
      (value "RFN10BM6STL")
      (footprint "Buck:RFN10BM")
      (libsource (lib "MYLIB") (part "DiodeSMD4.5mm"))
    )
    (comp (ref "CR6")
      (value "SMBJ48A")
      (footprint "Buck:SMB (DO-214AA)")
      (libsource (lib "MYLIB") (part "DiodeSMD4.5mm"))
    )
    (comp (ref "CR7")
      (value "SMBJ48A")
      (footprint "Buck:SMB (DO-214AA)")
      (libsource (lib "MYLIB") (part "DiodeSMD4.5mm"))
    )
    (comp (ref "CR8")
      (value "SMBJ48A")
      (footprint "Buck:SMB (DO-214AA)")
      (libsource (lib "MYLIB") (part "DiodeSMD4.5mm"))
    )
    (comp (ref "CR9")
      (value "SMBJ48A")
      (footprint "Buck:SMB (DO-214AA)")
      (libsource (lib "MYLIB") (part "DiodeSMD4.5mm"))
    )
    (comp (ref "D1")
      (value "KDZVTR39A")
      (footprint "Buck:SOD-123FL")
      (description "Zener Diode")
      (fields (field (name "PUBLISHER") "Altium Limited"))
      (libsource (lib "Miscellaneous Devices") (part "D Zener"))
    )
    (comp (ref "D2")
      (value "1N4007-SMD")
      (footprint "Buck:SMA (DO-214AC)")
      (description "Diode Standard 1000V 1A Through Hole DO-204AL _DO-41_")
      (fields (field (name "MF") "ON Semiconductor") (field (name "MP") "1N4007"))
      (libsource (lib "AC-DC Power supply") (part "1N4007"))
    )
    (comp (ref "D3")
      (value "E4D20120A")
      (footprint "Buck:FP-TO-220-2-MFG")
      (description "E SERIES, 20 AMP, 1200V G4 SCHOT")
      (libsource (lib "Miscellaneous Devices") (part "1d6ec82d83fb6aee721767c19dac4b9"))
    )
    (comp (ref "D4")
      (value "KDZVTR39A")
      (footprint "Buck:SOD-123FL")
      (description "Zener Diode")
      (fields (field (name "PUBLISHER") "Altium Limited"))
      (libsource (lib "Miscellaneous Devices") (part "D Zener"))
    )
    (comp (ref "D5")
      (value "VSS8D5M12HM3/H")
      (footprint "Buck:DO-221AD")
      (description "Schottky Diode")
      (fields (field (name "PUBLISHER") "Altium Limited"))
      (libsource (lib "Miscellaneous Devices") (part "D Schottky"))
    )
    (comp (ref "D6")
      (value "VSS8D5M12HM3/H")
      (footprint "Buck:DO-221AD")
      (description "Schottky Diode")
      (fields (field (name "PUBLISHER") "Altium Limited"))
      (libsource (lib "Miscellaneous Devices") (part "D Schottky"))
    )
    (comp (ref "D7")
      (value "1N4007-SMD")
      (footprint "Buck:SMA (DO-214AC)")
      (description "Diode Standard 1000V 1A Through Hole DO-204AL _DO-41_")
      (fields (field (name "MF") "ON Semiconductor") (field (name "MP") "1N4007"))
      (libsource (lib "AC-DC Power supply") (part "1N4007"))
    )
    (comp (ref "D8")
      (value "1N4007-SMD")
      (footprint "Buck:SMA (DO-214AC)")
      (description "Diode Standard 1000V 1A Through Hole DO-204AL _DO-41_")
      (fields (field (name "MF") "ON Semiconductor") (field (name "MP") "1N4007"))
      (libsource (lib "AC-DC Power supply") (part "1N4007"))
    )
    (comp (ref "D9")
      (value "E4D20120A")
      (footprint "Buck:FP-TO-220-2-MFG")
      (description "E SERIES, 20 AMP, 1200V G4 SCHOT")
      (libsource (lib "Miscellaneous Devices") (part "1d6ec82d83fb6aee721767c19dac4b9"))
    )
    (comp (ref "D10")
      (value "1N4007-SMD")
      (footprint "Buck:SMA (DO-214AC)")
      (description "Diode Standard 1000V 1A Through Hole DO-204AL _DO-41_")
      (fields (field (name "MF") "ON Semiconductor") (field (name "MP") "1N4007"))
      (libsource (lib "AC-DC Power supply") (part "1N4007"))
    )
    (comp (ref "D11")
      (value "1N4007-SMD")
      (footprint "Buck:SMA (DO-214AC)")
      (description "Diode Standard 1000V 1A Through Hole DO-204AL _DO-41_")
      (fields (field (name "MF") "ON Semiconductor") (field (name "MP") "1N4007"))
      (libsource (lib "AC-DC Power supply") (part "1N4007"))
    )
    (comp (ref "D12")
      (value "1N4007-SMD")
      (footprint "Buck:SMA (DO-214AC)")
      (description "Diode Standard 1000V 1A Through Hole DO-204AL _DO-41_")
      (fields (field (name "MF") "ON Semiconductor") (field (name "MP") "1N4007"))
      (libsource (lib "AC-DC Power supply") (part "1N4007"))
    )
    (comp (ref "DS2") (value "LED") (footprint "Buck:LED0805") (libsource (lib "SCH") (part "LED")))
    (comp (ref "DS3")
      (value "LED SMD")
      (footprint "Buck:LED0805")
      (description "Blue SURFACE MOUNT LED LAMP, -40 to +85 ,0805 SIZE")
      (fields (field (name "PART NUMBER") "QTLP630C-7"))
      (libsource (lib "kashizadeh_ali") (part "LED"))
    )
    (comp (ref "DS4")
      (value "LED SMD")
      (footprint "Buck:LED0805")
      (description "Blue SURFACE MOUNT LED LAMP, -40 to +85 ,0805 SIZE")
      (fields (field (name "PART NUMBER") "QTLP630C-7"))
      (libsource (lib "kashizadeh_ali") (part "LED"))
    )
    (comp (ref "DS5")
      (value "LED SMD")
      (footprint "Buck:LED0805")
      (description "Blue SURFACE MOUNT LED LAMP, -40 to +85 ,0805 SIZE")
      (fields (field (name "PART NUMBER") "QTLP630C-7"))
      (libsource (lib "kashizadeh_ali") (part "LED"))
    )
    (comp (ref "DS6")
      (value "LED SMD")
      (footprint "Buck:LED0805")
      (description "Blue SURFACE MOUNT LED LAMP, -40 to +85 ,0805 SIZE")
      (fields (field (name "PART NUMBER") "QTLP630C-7"))
      (libsource (lib "kashizadeh_ali") (part "LED"))
    )
    (comp (ref "DS7") (value "LED SMD") (footprint "Buck:LED0805") (libsource (lib "MYLIB") (part "LED SMD")))
    (comp (ref "DS8") (value "LED SMD") (footprint "Buck:LED0805") (libsource (lib "MYLIB") (part "LED SMD")))
    (comp (ref "DS9") (value "LED SMD") (footprint "Buck:LED0805") (libsource (lib "MYLIB") (part "LED SMD")))
    (comp (ref "EC2")
      (value "HSEC8-160-01-X-RA-BL")
      (footprint "Buck:HSEC816001LRA")
      (description "0.8MM HIGH SPEED ASSEMBLY.")
      (libsource (lib "HSEC8-160-01-X-RA-BL") (part "HSEC8-160-01-X-RA-BL"))
    )
    (comp (ref "F2")
      (value "0031.8001 Fuse holder")
      (footprint "Buck:00318001")
      (description "Fuse")
      (fields (field (name "PUBLISHER") "Altium Limited"))
      (libsource (lib "Miscellaneous Devices") (part "Fuse 1"))
    )
    (comp (ref "F3")
      (value "0031.8001 Fuse holder")
      (footprint "Buck:00318001")
      (description "Fuse")
      (fields (field (name "PUBLISHER") "Altium Limited"))
      (libsource (lib "Miscellaneous Devices") (part "Fuse 1"))
    )
    (comp (ref "FB1")
      (value "FBMJ2125HS420-T")
      (footprint "Buck:L0805")
      (libsource (lib "No_avaran") (part "FERRITE CHIP"))
    )
    (comp (ref "FB2")
      (value "FBMJ2125HS420-T")
      (footprint "Buck:L0805")
      (libsource (lib "No_avaran") (part "FERRITE CHIP"))
    )
    (comp (ref "FB3")
      (value "FBMJ2125HS420-T")
      (footprint "Buck:L0805")
      (libsource (lib "") (part "FERRITE CHIP_1"))
    )
    (comp (ref "FB4")
      (value "FBMJ2125HS420-T")
      (footprint "Buck:L0805")
      (libsource (lib "No_avaran") (part "FERRITE CHIP"))
    )
    (comp (ref "FB5")
      (value "FBMJ2125HS420-T")
      (footprint "Buck:L0805")
      (libsource (lib "No_avaran") (part "FERRITE CHIP"))
    )
    (comp (ref "FB6")
      (value "FBMJ2125HS420-T")
      (footprint "Buck:L0805")
      (libsource (lib "No_avaran") (part "FERRITE CHIP"))
    )
    (comp (ref "FB7")
      (value "FBMJ2125HS420-T")
      (footprint "Buck:L0805")
      (libsource (lib "No_avaran") (part "FERRITE CHIP"))
    )
    (comp (ref "FB8")
      (value "FBMJ2125HS420-T")
      (footprint "Buck:L0805")
      (libsource (lib "No_avaran") (part "FERRITE CHIP"))
    )
    (comp (ref "FB9")
      (value "FBMJ2125HS420-T")
      (footprint "Buck:L0805")
      (libsource (lib "No_avaran") (part "FERRITE CHIP"))
    )
    (comp (ref "FB10")
      (value "FBMJ2125HS420-T")
      (footprint "Buck:L0805")
      (libsource (lib "No_avaran") (part "FERRITE CHIP"))
    )
    (comp (ref "J3")
      (value "691101710002")
      (footprint "Buck:691101710002")
      (description "WR-TBL Series 101 Horizontal Entry Modular, THT, pitch 5mm, 2p")
      (fields (field (name "MANUFACTURER") "Wurth Elektronik"))
      (libsource (lib "Altium_WR-TBL (rev22b)") (part "691101710002"))
    )
    (comp (ref "J4")
      (value "61802525123")
      (footprint "Buck:61802525123")
      (description "WR-DSUB Female PCB Connector, Straight, 25p")
      (fields (field (name "MANUFACTURER") "Wurth Elektronik"))
      (libsource (lib "WR-DSUB") (part "61802525123"))
    )
    (comp (ref "J5")
      (value "61801525123")
      (footprint "Buck:61801525123")
      (description "WR-DSUB Female PCB Connector, Straight, 15p")
      (fields (field (name "MANUFACTURER") "Wurth Elektronik"))
      (libsource (lib "WR-DSUB") (part "61801525123"))
    )
    (comp (ref "J6")
      (value "691101710002")
      (footprint "Buck:691101710002")
      (description "WR-TBL Series 101 Horizontal Entry Modular, THT, pitch 5mm, 2p")
      (fields (field (name "MANUFACTURER") "Wurth Elektronik"))
      (libsource (lib "Altium_WR-TBL (rev22b)") (part "691101710002"))
    )
    (comp (ref "K1")
      (value "RTD34012F")
      (footprint "Buck:FP-RTD34012F-MFG")
      (description "RELAY GEN PURPOSE SPST 16A 12V")
      (libsource (lib "Miscellaneous Devices") (part "36ad11d084bb552319afff42e0065da"))
    )
    (comp (ref "L3")
      (value "Inductor")
      (footprint "Buck:Buck_Inductor_L3")
      (fields (field (name "ALTIUM_VALUE") "90uH, 60kHz") (field (name "PUBLISHER") "Altium Limited"))
      (libsource (lib "Miscellaneous Devices") (part "Inductor"))
    )
    (comp (ref "OK1")
      (value "HFBR-25x3Z")
      (footprint "Buck:HFBR-2533Z")
      (description "The Versatile Fiber Optic Connection, 40 kBd, -40 to 85 degC, 4-Pin, RoHS, Rail/Tube")
      (libsource (lib "HFBR_Tx_Rx") (part "HFBR-25x3Z"))
    )
    (comp (ref "P1")
      (value "691311400104")
      (footprint "Buck:691311400104")
      (description "Serie 3114 - 7.62mm Close Vertical PCB Header WR-TBL, 4 pin")
      (fields (field (name "MANUFACTURER") "Wurth Elektronik") (field (name "PUBLISHER") "WurthElektronik"))
      (libsource (lib "Miscellaneous Devices") (part "WE-CN-1P-M-R4"))
    )
    (comp (ref "P2")
      (value "691311400104")
      (footprint "Buck:691311400104")
      (description "Serie 3114 - 7.62mm Close Vertical PCB Header WR-TBL, 4 pin")
      (fields (field (name "MANUFACTURER") "Wurth Elektronik") (field (name "PUBLISHER") "WurthElektronik"))
      (libsource (lib "Miscellaneous Connectors") (part "WE-CN-1P-M-R4"))
    )
    (comp (ref "P3")
      (value "280371-2")
      (footprint "TECO-280371-2_V")
      (fields (field (name "MANUFACTURER") "TE Connectivity"))
      (libsource (lib "Altium Content Vault") (part "CN-1P-M-R4"))
    )
    (comp (ref "P4")
      (value "280371-2")
      (footprint "TECO-280371-2_V")
      (fields (field (name "MANUFACTURER") "TE Connectivity"))
      (libsource (lib "Altium Content Vault") (part "CN-1P-M-R4"))
    )
    (comp (ref "Q1")
      (value "ACPL-C87A-500E")
      (footprint "FP-SSO-8-MFG")
      (description "IC OPAMP ISOLATION 100KHZ 8SO")
      (libsource (lib "Altium Content Vault") (part "b42ed144594ce334135a4fb1ded0a30"))
    )
    (comp (ref "Q2")
      (value "ACPL-C87A-500E")
      (footprint "FP-SSO-8-MFG")
      (description "IC OPAMP ISOLATION 100KHZ 8SO")
      (libsource (lib "Altium Content Vault") (part "b42ed144594ce334135a4fb1ded0a30"))
    )
    (comp (ref "Q3")
      (value "SCT3022KLHR")
      (footprint "INF-PG-TO247-3-44")
      (fields (field (name "MANUFACTURER") "Infineon") (field (name "PARTNUMBER") "IPW60R099CP"))
      (libsource (lib "Altium Content Vault") (part "INF-NEMOS-GDS-3"))
    )
    (comp (ref "Q4")
      (value "SCT3022KLHR")
      (footprint "INF-PG-TO247-3-44")
      (fields (field (name "MANUFACTURER") "Infineon") (field (name "PARTNUMBER") "IPW60R099CP"))
      (libsource (lib "Altium Content Vault") (part "INF-NEMOS-GDS-3"))
    )
    (comp (ref "Q5")
      (value "DTC143ZET1G")
      (footprint "Buck:ONSC-SC-75-3-463-01_V")
      (fields (field (name "MANUFACTURER") "On Semiconductor"))
      (libsource (lib "Miscellaneous Devices") (part "ONSC-BRT-NPN-B1E2C3-3"))
    )
    (comp (ref "R1") (value "0 SMD") (footprint "Buck:R0805") (libsource (lib "MYLIB") (part "ResSMD")))
    (comp (ref "R2") (value "0 SMD") (footprint "Buck:R0805") (libsource (lib "MYLIB") (part "ResSMD")))
    (comp (ref "R3") (value "ResSMD") (footprint "Buck:R0805") (libsource (lib "MYLIB") (part "ResSMD")))
    (comp (ref "R4") (value "ResSMD") (footprint "Buck:R0805") (libsource (lib "MYLIB") (part "ResSMD")))
    (comp (ref "R5") (value "ResSMD") (footprint "Buck:R0805") (libsource (lib "MYLIB") (part "ResSMD")))
    (comp (ref "R6") (value "ResSMD") (footprint "Buck:R0805") (libsource (lib "MYLIB") (part "ResSMD")))
    (comp (ref "R7") (value "ResSMD") (footprint "Buck:R0805") (libsource (lib "MYLIB") (part "ResSMD")))
    (comp (ref "R8") (value "ResSMD") (footprint "Buck:R0805") (libsource (lib "MYLIB") (part "ResSMD")))
    (comp (ref "R9") (value "ResSMD") (footprint "Buck:R0805") (libsource (lib "MYLIB") (part "ResSMD")))
    (comp (ref "R10") (value "ResSMD") (footprint "Buck:R0805") (libsource (lib "MYLIB") (part "ResSMD")))
    (comp (ref "R11") (value "ResSMD") (footprint "Buck:R0805") (libsource (lib "MYLIB") (part "ResSMD")))
    (comp (ref "R12") (value "ResSMD") (footprint "Buck:R0805") (libsource (lib "MYLIB") (part "ResSMD")))
    (comp (ref "R13") (value "ResSMD") (footprint "Buck:R0805") (libsource (lib "MYLIB") (part "ResSMD")))
    (comp (ref "R14") (value "ResSMD") (footprint "Buck:R0805") (libsource (lib "MYLIB") (part "ResSMD")))
    (comp (ref "R15") (value "ResSMD") (footprint "Buck:R0805") (libsource (lib "MYLIB") (part "ResSMD")))
    (comp (ref "R16") (value "ResSMD") (footprint "Buck:R0805") (libsource (lib "MYLIB") (part "ResSMD")))
    (comp (ref "R17") (value "ResSMD") (footprint "Buck:R0805") (libsource (lib "MYLIB") (part "ResSMD")))
    (comp (ref "R18") (value "ResSMD") (footprint "Buck:R0805") (libsource (lib "MYLIB") (part "ResSMD")))
    (comp (ref "R19") (value "ResSMD") (footprint "Buck:R0805") (libsource (lib "MYLIB") (part "ResSMD")))
    (comp (ref "R20") (value "ResSMD") (footprint "Buck:R0805") (libsource (lib "MYLIB") (part "ResSMD")))
    (comp (ref "R21") (value "ResSMD") (footprint "Buck:R0805") (libsource (lib "MYLIB") (part "ResSMD")))
    (comp (ref "R22") (value "ResSMD") (footprint "Buck:R0805") (libsource (lib "MYLIB") (part "ResSMD")))
    (comp (ref "R23") (value "ResSMD") (footprint "Buck:R0805") (libsource (lib "MYLIB") (part "ResSMD")))
    (comp (ref "R24") (value "ResSMD") (footprint "Buck:R0805") (libsource (lib "MYLIB") (part "ResSMD")))
    (comp (ref "R25") (value "ResSMD") (footprint "Buck:R0805") (libsource (lib "MYLIB") (part "ResSMD")))
    (comp (ref "R26") (value "0 SMD") (footprint "Buck:R0805") (libsource (lib "MYLIB") (part "ResSMD")))
    (comp (ref "R27") (value "ResSMD") (footprint "Buck:R0805") (libsource (lib "MYLIB") (part "ResSMD")))
    (comp (ref "R28") (value "0 SMD") (footprint "Buck:R0805") (libsource (lib "MYLIB") (part "ResSMD")))
    (comp (ref "R29") (value "ResSMD") (footprint "Buck:R0805") (libsource (lib "MYLIB") (part "ResSMD")))
    (comp (ref "R30") (value "ResSMD") (footprint "Buck:R0805") (libsource (lib "MYLIB") (part "ResSMD")))
    (comp (ref "R31")
      (value "Res3")
      (footprint "Buck:R0603")
      (description "Resistor")
      (fields (field (name "ALTIUM_VALUE") "0") (field (name "PUBLISHER") "Altium Limited"))
      (libsource (lib "Miscellaneous Devices") (part "Res3"))
    )
    (comp (ref "R32")
      (value "Res3")
      (footprint "Buck:R0603")
      (description "Resistor")
      (fields (field (name "ALTIUM_VALUE") "0") (field (name "PUBLISHER") "Altium Limited"))
      (libsource (lib "Miscellaneous Devices") (part "Res3"))
    )
    (comp (ref "R33") (value "ResSMD") (footprint "Buck:R0805") (libsource (lib "MYLIB") (part "ResSMD")))
    (comp (ref "R34") (value "ResSMD") (footprint "Buck:R0805") (libsource (lib "MYLIB") (part "ResSMD")))
    (comp (ref "R35") (value "ResSMD") (footprint "Buck:R0805") (libsource (lib "MYLIB") (part "ResSMD")))
    (comp (ref "R36") (value "ResSMD") (footprint "Buck:R0805") (libsource (lib "MYLIB") (part "ResSMD")))
    (comp (ref "R37") (value "ResSMD") (footprint "Buck:R0805") (libsource (lib "MYLIB") (part "ResSMD")))
    (comp (ref "R38") (value "ResSMD") (footprint "Buck:R0805") (libsource (lib "MYLIB") (part "ResSMD")))
    (comp (ref "R39") (value "ResSMD") (footprint "Buck:R0805") (libsource (lib "MYLIB") (part "ResSMD")))
    (comp (ref "R40") (value "ResSMD") (footprint "Buck:R0805") (libsource (lib "MYLIB") (part "ResSMD")))
    (comp (ref "R41") (value "ResSMD") (footprint "Buck:R0805") (libsource (lib "MYLIB") (part "ResSMD")))
    (comp (ref "R42") (value "ResSMD") (footprint "Buck:R0805") (libsource (lib "MYLIB") (part "ResSMD")))
    (comp (ref "R43") (value "0 SMD") (footprint "Buck:R0805") (libsource (lib "MYLIB") (part "ResSMD")))
    (comp (ref "R44") (value "0 SMD") (footprint "Buck:R0805") (libsource (lib "MYLIB") (part "ResSMD")))
    (comp (ref "R45") (value "ResSMD") (footprint "Buck:R0805") (libsource (lib "MYLIB") (part "ResSMD")))
    (comp (ref "R46") (value "ResSMD") (footprint "Buck:R0805") (libsource (lib "MYLIB") (part "ResSMD")))
    (comp (ref "R47") (value "ResSMD") (footprint "Buck:R0805") (libsource (lib "MYLIB") (part "ResSMD")))
    (comp (ref "R48") (value "ResSMD") (footprint "Buck:R0805") (libsource (lib "MYLIB") (part "ResSMD")))
    (comp (ref "R49") (value "ResSMD") (footprint "Buck:R0805") (libsource (lib "MYLIB") (part "ResSMD")))
    (comp (ref "R50") (value "ResSMD") (footprint "Buck:R0805") (libsource (lib "MYLIB") (part "ResSMD")))
    (comp (ref "R52")
      (value "15")
      (footprint "AXIAL-0.5")
      (description "Semiconductor Resistor")
      (fields (field (name "ALTIUM_VALUE") "0.5W") (field (name "PUBLISHER") "Altium Limited"))
      (libsource (lib "Miscellaneous Devices") (part "Res Semi"))
    )
    (comp (ref "R53") (value "100") (footprint "Buck:R0805") (libsource (lib "MYLIB") (part "ResSMD")))
    (comp (ref "R54") (value "100") (footprint "Buck:R0805") (libsource (lib "MYLIB") (part "ResSMD")))
    (comp (ref "R55")
      (value "Res3")
      (footprint "Buck:R0603")
      (description "Resistor")
      (fields (field (name "ALTIUM_VALUE") "0") (field (name "PUBLISHER") "Altium Limited"))
      (libsource (lib "Miscellaneous Devices") (part "Res3"))
    )
    (comp (ref "R56")
      (value "Res3")
      (footprint "Buck:R0603")
      (description "Resistor")
      (fields (field (name "ALTIUM_VALUE") "0") (field (name "PUBLISHER") "Altium Limited"))
      (libsource (lib "Miscellaneous Devices") (part "Res3"))
    )
    (comp (ref "R57")
      (value "Res3")
      (footprint "Buck:R0603")
      (description "Resistor")
      (fields (field (name "ALTIUM_VALUE") "0") (field (name "PUBLISHER") "Altium Limited"))
      (libsource (lib "Miscellaneous Devices") (part "Res3"))
    )
    (comp (ref "R58")
      (value "CMA02040X1209GB300")
      (footprint "Buck:MMF50S")
      (description "Resistor")
      (fields (field (name "ALTIUM_VALUE") "1") (field (name "PUBLISHER") "Altium Limited"))
      (libsource (lib "Miscellaneous Devices") (part "Res1"))
    )
    (comp (ref "R59")
      (value "Res3")
      (footprint "Buck:R0603")
      (description "Resistor")
      (fields (field (name "ALTIUM_VALUE") "0") (field (name "PUBLISHER") "Altium Limited"))
      (libsource (lib "Miscellaneous Devices") (part "Res3"))
    )
    (comp (ref "R60") (value "0") (footprint "Buck:R0805") (libsource (lib "MYLIB") (part "ResSMD")))
    (comp (ref "R61")
      (value "Res1")
      (footprint "Buck:R0805")
      (description "Resistor")
      (fields (field (name "ALTIUM_VALUE") "1") (field (name "PUBLISHER") "Altium Limited"))
      (libsource (lib "Miscellaneous Devices") (part "Res1"))
    )
    (comp (ref "R62")
      (value "Res1")
      (footprint "Buck:R0805")
      (description "Resistor")
      (fields (field (name "ALTIUM_VALUE") "1") (field (name "PUBLISHER") "Altium Limited"))
      (libsource (lib "Miscellaneous Devices") (part "Res1"))
    )
    (comp (ref "R63")
      (value "Res3")
      (footprint "Buck:R0603")
      (description "Resistor")
      (fields (field (name "ALTIUM_VALUE") "0") (field (name "PUBLISHER") "Altium Limited"))
      (libsource (lib "Miscellaneous Devices") (part "Res3"))
    )
    (comp (ref "R64")
      (value "Res3")
      (footprint "Buck:R0603")
      (description "Resistor")
      (fields (field (name "ALTIUM_VALUE") "0") (field (name "PUBLISHER") "Altium Limited"))
      (libsource (lib "Miscellaneous Devices") (part "Res3"))
    )
    (comp (ref "R65")
      (value "CMA02040X1209GB300")
      (footprint "Buck:MMF50S")
      (description "Resistor")
      (fields (field (name "ALTIUM_VALUE") "1") (field (name "PUBLISHER") "Altium Limited"))
      (libsource (lib "Miscellaneous Devices") (part "Res1"))
    )
    (comp (ref "R66")
      (value "Res3")
      (footprint "Buck:R0603")
      (description "Resistor")
      (fields (field (name "ALTIUM_VALUE") "10K") (field (name "PUBLISHER") "Altium Limited"))
      (libsource (lib "Miscellaneous Devices") (part "Res3"))
    )
    (comp (ref "R67") (value "0") (footprint "Buck:R0805") (libsource (lib "MYLIB") (part "ResSMD")))
    (comp (ref "R68")
      (value "1K")
      (footprint "Buck:R0805")
      (description "resistor 1/4 wat")
      (libsource (lib "Mylib") (part "Res"))
    )
    (comp (ref "R69") (value "100k") (footprint "Buck:R0805") (libsource (lib "MYLIB") (part "ResSMD")))
    (comp (ref "R70") (value "1K") (footprint "Buck:R0805") (libsource (lib "MYLIB") (part "ResSMD")))
    (comp (ref "R71")
      (value "Res3")
      (footprint "Buck:R0603")
      (description "Resistor")
      (fields (field (name "ALTIUM_VALUE") "10K") (field (name "PUBLISHER") "Altium Limited"))
      (libsource (lib "Miscellaneous Devices") (part "Res3"))
    )
    (comp (ref "R72")
      (value "Res3")
      (footprint "Buck:R0603")
      (description "Resistor")
      (fields (field (name "ALTIUM_VALUE") "0") (field (name "PUBLISHER") "Altium Limited"))
      (libsource (lib "Miscellaneous Devices") (part "Res3"))
    )
    (comp (ref "R73")
      (value "Res3")
      (footprint "Buck:R0603")
      (description "Resistor")
      (fields (field (name "ALTIUM_VALUE") "0") (field (name "PUBLISHER") "Altium Limited"))
      (libsource (lib "Miscellaneous Devices") (part "Res3"))
    )
    (comp (ref "R74")
      (value "Res3")
      (footprint "Buck:R0603")
      (description "Resistor")
      (fields (field (name "ALTIUM_VALUE") "0") (field (name "PUBLISHER") "Altium Limited"))
      (libsource (lib "Miscellaneous Devices") (part "Res3"))
    )
    (comp (ref "R75")
      (value "300")
      (footprint "Footprint_950322:R0805")
      (libsource (lib "MYLIB") (part "ResSMD"))
    )
    (comp (ref "R76")
      (value "Res3")
      (footprint "Buck:R0603")
      (description "Resistor")
      (fields (field (name "ALTIUM_VALUE") "0") (field (name "PUBLISHER") "Altium Limited"))
      (libsource (lib "Miscellaneous Devices") (part "Res3"))
    )
    (comp (ref "R77")
      (value "300")
      (footprint "Footprint_950322:R0805")
      (libsource (lib "MYLIB") (part "ResSMD"))
    )
    (comp (ref "R78")
      (value "Res3")
      (footprint "Buck:R0603")
      (description "Resistor")
      (fields (field (name "ALTIUM_VALUE") "0") (field (name "PUBLISHER") "Altium Limited"))
      (libsource (lib "Miscellaneous Devices") (part "Res3"))
    )
    (comp (ref "R79")
      (value "Res3")
      (footprint "Buck:R0603")
      (description "Resistor")
      (fields (field (name "ALTIUM_VALUE") "0") (field (name "PUBLISHER") "Altium Limited"))
      (libsource (lib "Miscellaneous Devices") (part "Res3"))
    )
    (comp (ref "R80") (value "1K") (footprint "Buck:R0805") (libsource (lib "MYLIB") (part "ResSMD")))
    (comp (ref "R81") (value "1K") (footprint "Buck:R0805") (libsource (lib "MYLIB") (part "ResSMD")))
    (comp (ref "R82") (value "1K") (footprint "Buck:R0805") (libsource (lib "MYLIB") (part "ResSMD")))
    (comp (ref "R83") (value "ResSMD") (footprint "Buck:R0805") (libsource (lib "MYLIB") (part "ResSMD")))
    (comp (ref "R84") (value "ResSMD") (footprint "Buck:R0805") (libsource (lib "MYLIB") (part "ResSMD")))
    (comp (ref "R85") (value "ResSMD") (footprint "Buck:R0805") (libsource (lib "MYLIB") (part "ResSMD")))
    (comp (ref "R86") (value "0 SMD") (footprint "Buck:R0805") (libsource (lib "MYLIB") (part "ResSMD")))
    (comp (ref "R87") (value "0 SMD") (footprint "Buck:R0805") (libsource (lib "MYLIB") (part "ResSMD")))
    (comp (ref "R88") (value "ResSMD") (footprint "Buck:R0805") (libsource (lib "MYLIB") (part "ResSMD")))
    (comp (ref "R89") (value "ResSMD") (footprint "Buck:R0805") (libsource (lib "MYLIB") (part "ResSMD")))
    (comp (ref "R90") (value "ResSMD") (footprint "Buck:R0805") (libsource (lib "MYLIB") (part "ResSMD")))
    (comp (ref "R91") (value "ResSMD") (footprint "Buck:R0805") (libsource (lib "MYLIB") (part "ResSMD")))
    (comp (ref "R92") (value "0 SMD") (footprint "Buck:R0805") (libsource (lib "MYLIB") (part "ResSMD")))
    (comp (ref "R93") (value "0 SMD") (footprint "Buck:R0805") (libsource (lib "MYLIB") (part "ResSMD")))
    (comp (ref "R94") (value "ResSMD") (footprint "Buck:R0805") (libsource (lib "MYLIB") (part "ResSMD")))
    (comp (ref "R95") (value "ResSMD") (footprint "Buck:R0805") (libsource (lib "MYLIB") (part "ResSMD")))
    (comp (ref "R96") (value "15K") (footprint "Buck:R0805") (libsource (lib "MYLIB") (part "ResSMD")))
    (comp (ref "R97") (value "ResSMD") (footprint "Buck:R0805") (libsource (lib "MYLIB") (part "ResSMD")))
    (comp (ref "R98") (value "15K") (footprint "Buck:R0805") (libsource (lib "MYLIB") (part "ResSMD")))
    (comp (ref "R99") (value "15K") (footprint "Buck:R0805") (libsource (lib "MYLIB") (part "ResSMD")))
    (comp (ref "R100") (value "5K") (footprint "Buck:R0805") (libsource (lib "MYLIB") (part "ResSMD")))
    (comp (ref "R101") (value "5K") (footprint "Buck:R0805") (libsource (lib "MYLIB") (part "ResSMD")))
    (comp (ref "R102")
      (value "??")
      (footprint "AXIAL-0.5")
      (description "Semiconductor Resistor")
      (fields (field (name "ALTIUM_VALUE") "0.5W") (field (name "PUBLISHER") "Altium Limited"))
      (libsource (lib "Miscellaneous Devices") (part "Res Semi"))
    )
    (comp (ref "R103")
      (value "12")
      (footprint "Buck:R0805")
      (description "Semiconductor Resistor")
      (fields (field (name "ALTIUM_VALUE") "CMA02040X1209GB300") (field (name "PUBLISHER") "Altium Limited"))
      (libsource (lib "Miscellaneous Devices") (part "Res Semi"))
    )
    (comp (ref "R104")
      (value "47k")
      (footprint "Buck:R0805")
      (description "Resistor")
      (fields (field (name "ALTIUM_VALUE") "47k") (field (name "PUBLISHER") "Altium Limited"))
      (libsource (lib "Miscellaneous Devices") (part "Res1"))
    )
    (comp (ref "R105")
      (value "12")
      (footprint "Buck:R0805")
      (description "Semiconductor Resistor")
      (fields (field (name "ALTIUM_VALUE") "CMA02040X1209GB300") (field (name "PUBLISHER") "Altium Limited"))
      (libsource (lib "Miscellaneous Devices") (part "Res Semi"))
    )
    (comp (ref "R106")
      (value "??")
      (footprint "AXIAL-0.5")
      (description "Semiconductor Resistor")
      (fields (field (name "ALTIUM_VALUE") "0.5W") (field (name "PUBLISHER") "Altium Limited"))
      (libsource (lib "Miscellaneous Devices") (part "Res Semi"))
    )
    (comp (ref "R107")
      (value "??")
      (footprint "AXIAL-0.5")
      (description "Semiconductor Resistor")
      (fields (field (name "ALTIUM_VALUE") "0.5W") (field (name "PUBLISHER") "Altium Limited"))
      (libsource (lib "Miscellaneous Devices") (part "Res Semi"))
    )
    (comp (ref "R108")
      (value "??")
      (footprint "AXIAL-0.5")
      (description "Semiconductor Resistor")
      (fields (field (name "ALTIUM_VALUE") "0.5W") (field (name "PUBLISHER") "Altium Limited"))
      (libsource (lib "Miscellaneous Devices") (part "Res Semi"))
    )
    (comp (ref "R109")
      (value "??")
      (footprint "AXIAL-0.5")
      (description "Semiconductor Resistor")
      (fields (field (name "ALTIUM_VALUE") "0.5W") (field (name "PUBLISHER") "Altium Limited"))
      (libsource (lib "Miscellaneous Devices") (part "Res Semi"))
    )
    (comp (ref "R110")
      (value "??")
      (footprint "AXIAL-0.5")
      (description "Semiconductor Resistor")
      (fields (field (name "ALTIUM_VALUE") "0.5W") (field (name "PUBLISHER") "Altium Limited"))
      (libsource (lib "Miscellaneous Devices") (part "Res Semi"))
    )
    (comp (ref "R111")
      (value "??")
      (footprint "AXIAL-0.5")
      (description "Semiconductor Resistor")
      (fields (field (name "ALTIUM_VALUE") "0.5W") (field (name "PUBLISHER") "Altium Limited"))
      (libsource (lib "Miscellaneous Devices") (part "Res Semi"))
    )
    (comp (ref "R112")
      (value "??")
      (footprint "AXIAL-0.5")
      (description "Semiconductor Resistor")
      (fields (field (name "ALTIUM_VALUE") "0.5W") (field (name "PUBLISHER") "Altium Limited"))
      (libsource (lib "Miscellaneous Devices") (part "Res Semi"))
    )
    (comp (ref "R113")
      (value "??")
      (footprint "AXIAL-0.5")
      (description "Semiconductor Resistor")
      (fields (field (name "ALTIUM_VALUE") "0.5W") (field (name "PUBLISHER") "Altium Limited"))
      (libsource (lib "Miscellaneous Devices") (part "Res Semi"))
    )
    (comp (ref "R114")
      (value "??")
      (footprint "AXIAL-0.5")
      (description "Semiconductor Resistor")
      (fields (field (name "ALTIUM_VALUE") "0.5W") (field (name "PUBLISHER") "Altium Limited"))
      (libsource (lib "Miscellaneous Devices") (part "Res Semi"))
    )
    (comp (ref "R115")
      (value "Res3")
      (footprint "Buck:R0603")
      (description "Resistor")
      (fields (field (name "ALTIUM_VALUE") "0") (field (name "PUBLISHER") "Altium Limited"))
      (libsource (lib "Miscellaneous Devices") (part "Res3"))
    )
    (comp (ref "R116")
      (value "Res3")
      (footprint "Buck:R0603")
      (description "Resistor")
      (fields (field (name "ALTIUM_VALUE") "0") (field (name "PUBLISHER") "Altium Limited"))
      (libsource (lib "Miscellaneous Devices") (part "Res3"))
    )
    (comp (ref "R117")
      (value "Res3")
      (footprint "Buck:R0603")
      (description "Resistor")
      (fields (field (name "ALTIUM_VALUE") "0") (field (name "PUBLISHER") "Altium Limited"))
      (libsource (lib "Miscellaneous Devices") (part "Res3"))
    )
    (comp (ref "R118")
      (value "Res3")
      (footprint "Buck:R0603")
      (description "Resistor")
      (fields (field (name "ALTIUM_VALUE") "0") (field (name "PUBLISHER") "Altium Limited"))
      (libsource (lib "Miscellaneous Devices") (part "Res3"))
    )
    (comp (ref "R119")
      (value "Res3")
      (footprint "Buck:R0603")
      (description "Resistor")
      (fields (field (name "ALTIUM_VALUE") "0") (field (name "PUBLISHER") "Altium Limited"))
      (libsource (lib "Miscellaneous Devices") (part "Res3"))
    )
    (comp (ref "R120")
      (value "MOVS2825V420")
      (footprint "Buck:MOVS2825V420")
      (description "Varistor (Voltage-Sensitive Resistor)")
      (fields (field (name "PUBLISHER") "Altium Limited"))
      (libsource (lib "Miscellaneous Devices") (part "Res Varistor"))
    )
    (comp (ref "R121")
      (value "0")
      (footprint "Buck:R0805")
      (description "RES Thick Film, 2kΩ, 1%, 0.25W, 100ppm/°C, 1206")
      (fields (field (name "TOLERANCE") "1%"))
      (libsource (lib "Miscellaneous Devices") (part "1029c3af85768c4190bb7ad29bc67b5"))
    )
    (comp (ref "R122")
      (value "15k")
      (footprint "Buck:R0805")
      (description "RES Thick Film, 2kΩ, 1%, 0.25W, 100ppm/°C, 1206")
      (fields (field (name "TOLERANCE") "1%"))
      (libsource (lib "Miscellaneous Devices") (part "1029c3af85768c4190bb7ad29bc67b5"))
    )
    (comp (ref "R123")
      (value "100")
      (footprint "Buck:R0805")
      (description "RES Thick Film, 2kΩ, 1%, 0.25W, 100ppm/°C, 1206")
      (fields (field (name "TOLERANCE") "1%"))
      (libsource (lib "Miscellaneous Devices") (part "1029c3af85768c4190bb7ad29bc67b5"))
    )
    (comp (ref "R124")
      (value "4.7k")
      (footprint "Buck:R0805")
      (description "RES Thick Film, 2kΩ, 1%, 0.25W, 100ppm/°C, 1206")
      (fields (field (name "TOLERANCE") "1%"))
      (libsource (lib "Miscellaneous Devices") (part "1029c3af85768c4190bb7ad29bc67b5"))
    )
    (comp (ref "R125")
      (value "4.7k")
      (footprint "Buck:R0805")
      (description "RES Thick Film, 2kΩ, 1%, 0.25W, 100ppm/°C, 1206")
      (fields (field (name "TOLERANCE") "1%"))
      (libsource (lib "Miscellaneous Devices") (part "1029c3af85768c4190bb7ad29bc67b5"))
    )
    (comp (ref "R126") (value "100") (footprint "Buck:R0805") (libsource (lib "MYLIB") (part "ResSMD")))
    (comp (ref "R127")
      (value "4.7k")
      (footprint "Buck:R0805")
      (description "RES Thick Film, 2kΩ, 1%, 0.25W, 100ppm/°C, 1206")
      (fields (field (name "TOLERANCE") "1%"))
      (libsource (lib "Miscellaneous Devices") (part "1029c3af85768c4190bb7ad29bc67b5"))
    )
    (comp (ref "R128")
      (value "4.7k")
      (footprint "Buck:R0805")
      (description "RES Thick Film, 2kΩ, 1%, 0.25W, 100ppm/°C, 1206")
      (fields (field (name "TOLERANCE") "1%"))
      (libsource (lib "Miscellaneous Devices") (part "1029c3af85768c4190bb7ad29bc67b5"))
    )
    (comp (ref "R129")
      (value "Res1")
      (footprint "Buck:R0805")
      (description "Resistor")
      (fields (field (name "ALTIUM_VALUE") "15k") (field (name "PUBLISHER") "Altium Limited"))
      (libsource (lib "Miscellaneous Devices") (part "Res1"))
    )
    (comp (ref "R130")
      (value "Res3")
      (footprint "Buck:R0603")
      (description "Resistor")
      (fields (field (name "ALTIUM_VALUE") "0") (field (name "PUBLISHER") "Altium Limited"))
      (libsource (lib "Miscellaneous Devices") (part "Res3"))
    )
    (comp (ref "R131")
      (value "Res3")
      (footprint "Buck:R0603")
      (description "Resistor")
      (fields (field (name "ALTIUM_VALUE") "0") (field (name "PUBLISHER") "Altium Limited"))
      (libsource (lib "Miscellaneous Devices") (part "Res3"))
    )
    (comp (ref "R132") (value "5K") (footprint "Buck:R0805") (libsource (lib "MYLIB") (part "ResSMD")))
    (comp (ref "R133") (value "5K") (footprint "Buck:R0805") (libsource (lib "MYLIB") (part "ResSMD")))
    (comp (ref "R134")
      (value "RC0603JR-13820RL")
      (footprint "Buck:R0805")
      (fields (field (name "MANUFACTURER") "Yageo") (field (name "RESISTANCE") "3k3"))
      (libsource (lib "Miscellaneous Devices") (part "RES"))
    )
    (comp (ref "R135")
      (value "RC0603JR-13820RL")
      (footprint "Buck:R0805")
      (fields (field (name "MANUFACTURER") "Yageo") (field (name "RESISTANCE") "560"))
      (libsource (lib "Miscellaneous Devices") (part "RES"))
    )
    (comp (ref "R136")
      (value "RC0603JR-13820RL")
      (footprint "Buck:R0805")
      (fields (field (name "MANUFACTURER") "Yageo") (field (name "RESISTANCE") "5k6"))
      (libsource (lib "Miscellaneous Devices") (part "RES"))
    )
    (comp (ref "Rj1")
      (value "ERJ-3GEY0R00V")
      (footprint "Buck:R0603")
      (description "RES, 0, 5%, 0.1 W, 0603")
      (fields
        (field (name "VALUEDISPLAYED") "0")
        (field (name "MANUFACTURER") "Panasonic")
        (field (name "PUBLISHER") "Texas Instruments")
      )
      (libsource (lib "Resistor_0603") (part "ERJ-3GEY0R00V"))
    )
    (comp (ref "Rj2")
      (value "ERJ-3GEY0R00V")
      (footprint "Buck:R0603")
      (description "RES, 0, 5%, 0.1 W, 0603")
      (fields
        (field (name "VALUEDISPLAYED") "0")
        (field (name "MANUFACTURER") "Panasonic")
        (field (name "PUBLISHER") "Texas Instruments")
      )
      (libsource (lib "Resistor_0603") (part "ERJ-3GEY0R00V"))
    )
    (comp (ref "Rj3")
      (value "ERJ-3GEY0R00V")
      (footprint "Buck:R0603")
      (description "RES, 0, 5%, 0.1 W, 0603")
      (fields
        (field (name "VALUEDISPLAYED") "0")
        (field (name "MANUFACTURER") "Panasonic")
        (field (name "PUBLISHER") "Texas Instruments")
      )
      (libsource (lib "Resistor_0603") (part "ERJ-3GEY0R00V"))
    )
    (comp (ref "Rj4")
      (value "ERJ-3GEY0R00V")
      (footprint "Buck:R0603")
      (description "RES, 0, 5%, 0.1 W, 0603")
      (fields
        (field (name "VALUEDISPLAYED") "0")
        (field (name "MANUFACTURER") "Panasonic")
        (field (name "PUBLISHER") "Texas Instruments")
      )
      (libsource (lib "Resistor_0603") (part "ERJ-3GEY0R00V"))
    )
    (comp (ref "Rj5")
      (value "ERJ-3GEY0R00V")
      (footprint "Buck:R0603")
      (description "RES, 0, 5%, 0.1 W, 0603")
      (fields
        (field (name "VALUEDISPLAYED") "0")
        (field (name "MANUFACTURER") "Panasonic")
        (field (name "PUBLISHER") "Texas Instruments")
      )
      (libsource (lib "Resistor_0603") (part "ERJ-3GEY0R00V"))
    )
    (comp (ref "Rj6")
      (value "ERJ-3GEY0R00V")
      (footprint "Buck:R0603")
      (description "RES, 0, 5%, 0.1 W, 0603")
      (fields
        (field (name "VALUEDISPLAYED") "0")
        (field (name "MANUFACTURER") "Panasonic")
        (field (name "PUBLISHER") "Texas Instruments")
      )
      (libsource (lib "Resistor_0603") (part "ERJ-3GEY0R00V"))
    )
    (comp (ref "Rj7")
      (value "ERJ-3GEY0R00V")
      (footprint "Buck:R0603")
      (description "RES, 0, 5%, 0.1 W, 0603")
      (fields
        (field (name "VALUEDISPLAYED") "0")
        (field (name "MANUFACTURER") "Panasonic")
        (field (name "PUBLISHER") "Texas Instruments")
      )
      (libsource (lib "Resistor_0603") (part "ERJ-3GEY0R00V"))
    )
    (comp (ref "Rj8")
      (value "ERJ-3GEY0R00V")
      (footprint "Buck:R0603")
      (description "RES, 0, 5%, 0.1 W, 0603")
      (fields
        (field (name "VALUEDISPLAYED") "0")
        (field (name "MANUFACTURER") "Panasonic")
        (field (name "PUBLISHER") "Texas Instruments")
      )
      (libsource (lib "Resistor_0603") (part "ERJ-3GEY0R00V"))
    )
    (comp (ref "Rj9")
      (value "ERJ-3GEY0R00V")
      (footprint "Buck:R0603")
      (description "RES, 0, 5%, 0.1 W, 0603")
      (fields
        (field (name "VALUEDISPLAYED") "0")
        (field (name "MANUFACTURER") "Panasonic")
        (field (name "PUBLISHER") "Texas Instruments")
      )
      (libsource (lib "Resistor_0603") (part "ERJ-3GEY0R00V"))
    )
    (comp (ref "Rj10")
      (value "ERJ-3GEY0R00V")
      (footprint "Buck:R0603")
      (description "RES, 0, 5%, 0.1 W, 0603")
      (fields
        (field (name "VALUEDISPLAYED") "0")
        (field (name "MANUFACTURER") "Panasonic")
        (field (name "PUBLISHER") "Texas Instruments")
      )
      (libsource (lib "Resistor_0603") (part "ERJ-3GEY0R00V"))
    )
    (comp (ref "Rj11")
      (value "ERJ-3GEY0R00V")
      (footprint "Buck:R0603")
      (description "RES, 0, 5%, 0.1 W, 0603")
      (fields
        (field (name "VALUEDISPLAYED") "0")
        (field (name "MANUFACTURER") "Panasonic")
        (field (name "PUBLISHER") "Texas Instruments")
      )
      (libsource (lib "Resistor_0603") (part "ERJ-3GEY0R00V"))
    )
    (comp (ref "Rj12")
      (value "ERJ-3GEY0R00V")
      (footprint "Buck:R0603")
      (description "RES, 0, 5%, 0.1 W, 0603")
      (fields
        (field (name "VALUEDISPLAYED") "0")
        (field (name "MANUFACTURER") "Panasonic")
        (field (name "PUBLISHER") "Texas Instruments")
      )
      (libsource (lib "Resistor_0603") (part "ERJ-3GEY0R00V"))
    )
    (comp (ref "RT1")
      (value "Resistor AS32 5R020")
      (footprint "Buck:AS32 5R020")
      (description "Thermistor")
      (fields (field (name "PUBLISHER") "Altium Limited"))
      (libsource (lib "Miscellaneous Devices") (part "Res Thermal"))
    )
    (comp (ref "S1")
      (value "EB2011-CA")
      (footprint "Buck:EB2011-CA")
      (description "SPDT Subminiature Toggle Switch, Right Angle Mounting, Vertical Actuation")
      (fields (field (name "PUBLISHER") "Altium Limited"))
      (libsource (lib "Miscellaneous Devices") (part "SW-SPDT"))
    )
    (comp (ref "TP1")
      (value "Pad")
      (footprint "Buck:TP-0.5mm")
      (libsource (lib "MYLIB") (part "Con1 pin-Small"))
    )
    (comp (ref "TP2")
      (value "Pad")
      (footprint "Buck:TP-0.5mm")
      (libsource (lib "") (part "Con1 pin-Small_2"))
    )
    (comp (ref "TP3")
      (value "Pad")
      (footprint "Buck:TP-0.5mm")
      (libsource (lib "MYLIB") (part "Con1 pin-Small"))
    )
    (comp (ref "TP4")
      (value "Pad")
      (footprint "Buck:TP-0.5mm")
      (libsource (lib "MYLIB") (part "Con1 pin-Small"))
    )
    (comp (ref "TP5")
      (value "Pad")
      (footprint "Buck:TP-0.5mm")
      (libsource (lib "MYLIB") (part "Con1 pin-Small"))
    )
    (comp (ref "TP7")
      (value "Pad")
      (footprint "Buck:TP-0.5mm")
      (libsource (lib "MYLIB") (part "Con1 pin-Small"))
    )
    (comp (ref "TP8")
      (value "Pad")
      (footprint "Buck:TP-0.5mm")
      (libsource (lib "MYLIB") (part "Con1 pin-Small"))
    )
    (comp (ref "TP9")
      (value "Pad")
      (footprint "Buck:TP-0.5mm")
      (libsource (lib "") (part "Con1 pin-Small_3"))
    )
    (comp (ref "TP10")
      (value "Pad")
      (footprint "Buck:TP-0.5mm")
      (libsource (lib "MYLIB") (part "Con1 pin-Small"))
    )
    (comp (ref "TP11")
      (value "Pad")
      (footprint "Buck:TP-0.5mm")
      (libsource (lib "MYLIB") (part "Con1 pin-Small"))
    )
    (comp (ref "TP12")
      (value "Pad")
      (footprint "Buck:TP-0.5mm")
      (libsource (lib "") (part "Con1 pin-Small_1"))
    )
    (comp (ref "TP13")
      (value "Pad")
      (footprint "Buck:TP-0.5mm")
      (libsource (lib "MYLIB") (part "Con1 pin-Small"))
    )
    (comp (ref "TP14")
      (value "Pad")
      (footprint "Buck:TP-0.5mm")
      (libsource (lib "") (part "Con1 pin-Small_1"))
    )
    (comp (ref "TP15")
      (value "Pad")
      (footprint "Buck:TP-0.5mm")
      (libsource (lib "MYLIB") (part "Con1 pin-Small"))
    )
    (comp (ref "TP16")
      (value "Pad")
      (footprint "Buck:TP-0.5mm")
      (libsource (lib "MYLIB") (part "Con1 pin-Small"))
    )
    (comp (ref "TP17")
      (value "Pad")
      (footprint "Buck:TP-0.5mm")
      (libsource (lib "MYLIB") (part "Con1 pin-Small"))
    )
    (comp (ref "TP18")
      (value "Pad")
      (footprint "Buck:TP-0.5mm")
      (libsource (lib "MYLIB") (part "Con1 pin-Small"))
    )
    (comp (ref "TP19")
      (value "Pad")
      (footprint "Buck:TP-0.5mm")
      (libsource (lib "") (part "Con1 pin-Small_2"))
    )
    (comp (ref "TP20")
      (value "Pad")
      (footprint "Buck:TP-0.5mm")
      (libsource (lib "") (part "Con1 pin-Small_2"))
    )
    (comp (ref "TP21")
      (value "Pad")
      (footprint "Buck:TP-0.5mm")
      (libsource (lib "") (part "Con1 pin-Small_3"))
    )
    (comp (ref "TP22")
      (value "Pad")
      (footprint "Buck:TP-0.5mm")
      (libsource (lib "MYLIB") (part "Con1 pin-Small"))
    )
    (comp (ref "TP23")
      (value "Pad")
      (footprint "Buck:TP-0.5mm")
      (libsource (lib "") (part "Con1 pin-Small_1"))
    )
    (comp (ref "TP25")
      (value "Pad")
      (footprint "Buck:TP-0.5mm")
      (libsource (lib "") (part "Con1 pin-Small_3"))
    )
    (comp (ref "TP26")
      (value "Pad")
      (footprint "Buck:TP-0.5mm")
      (libsource (lib "MYLIB") (part "Con1 pin-Small"))
    )
    (comp (ref "TP27")
      (value "Pad")
      (footprint "Buck:TP-0.5mm")
      (libsource (lib "MYLIB") (part "Con1 pin-Small"))
    )
    (comp (ref "TP28")
      (value "Pad")
      (footprint "Buck:TP-0.5mm")
      (libsource (lib "MYLIB") (part "Con1 pin-Small"))
    )
    (comp (ref "TP29")
      (value "Pad")
      (footprint "Buck:TP-0.5mm")
      (libsource (lib "MYLIB") (part "Con1 pin-Small"))
    )
    (comp (ref "TP30")
      (value "Pad")
      (footprint "Buck:TP-0.5mm")
      (libsource (lib "MYLIB") (part "Con1 pin-Small"))
    )
    (comp (ref "TP31")
      (value "Pad")
      (footprint "Buck:TP-0.5mm")
      (libsource (lib "") (part "Con1 pin-Small_1"))
    )
    (comp (ref "TP32")
      (value "Pad")
      (footprint "Buck:TP-0.5mm")
      (libsource (lib "") (part "Con1 pin-Small_1"))
    )
    (comp (ref "TP33")
      (value "Pad")
      (footprint "Buck:TP-0.5mm")
      (libsource (lib "") (part "Con1 pin-Small_2"))
    )
    (comp (ref "TP34")
      (value "Pad")
      (footprint "Buck:TP-0.5mm")
      (libsource (lib "") (part "Con1 pin-Small_2"))
    )
    (comp (ref "TP35")
      (value "Pad")
      (footprint "Buck:TP-0.5mm")
      (libsource (lib "MYLIB") (part "Con1 pin-Small"))
    )
    (comp (ref "TP36")
      (value "Pad")
      (footprint "Buck:TP-0.5mm")
      (libsource (lib "MYLIB") (part "Con1 pin-Small"))
    )
    (comp (ref "TP37")
      (value "Pad")
      (footprint "Buck:TP-0.5mm")
      (libsource (lib "MYLIB") (part "Con1 pin-Small"))
    )
    (comp (ref "TP38")
      (value "Pad")
      (footprint "Buck:TP-0.5mm")
      (libsource (lib "") (part "Con1 pin-Small_1"))
    )
    (comp (ref "TP39")
      (value "Pad")
      (footprint "Buck:TP-0.5mm")
      (libsource (lib "") (part "Con1 pin-Small_2"))
    )
    (comp (ref "TP40")
      (value "Pad")
      (footprint "Buck:TP-0.5mm")
      (libsource (lib "") (part "Con1 pin-Small_1"))
    )
    (comp (ref "TP41")
      (value "Pad")
      (footprint "Buck:TP-0.5mm")
      (libsource (lib "") (part "Con1 pin-Small_1"))
    )
    (comp (ref "TP42")
      (value "Pad")
      (footprint "Buck:TP-0.5mm")
      (libsource (lib "MYLIB") (part "Con1 pin-Small"))
    )
    (comp (ref "TP43")
      (value "Pad")
      (footprint "Buck:TP-0.5mm")
      (libsource (lib "MYLIB") (part "Con1 pin-Small"))
    )
    (comp (ref "TP44")
      (value "Pad")
      (footprint "Buck:TP-0.5mm")
      (libsource (lib "") (part "Con1 pin-Small_1"))
    )
    (comp (ref "TP45")
      (value "Pad")
      (footprint "Buck:TP-0.5mm")
      (libsource (lib "") (part "Con1 pin-Small_2"))
    )
    (comp (ref "TP46")
      (value "Pad")
      (footprint "Buck:TP-0.5mm")
      (libsource (lib "MYLIB") (part "Con1 pin-Small"))
    )
    (comp (ref "TP47")
      (value "Pad")
      (footprint "Buck:TP-0.5mm")
      (libsource (lib "MYLIB") (part "Con1 pin-Small"))
    )
    (comp (ref "TP48")
      (value "Pad")
      (footprint "Buck:TP-0.5mm")
      (libsource (lib "MYLIB") (part "Con1 pin-Small"))
    )
    (comp (ref "TP49")
      (value "Pad")
      (footprint "Buck:TP-0.5mm")
      (libsource (lib "MYLIB") (part "Con1 pin-Small"))
    )
    (comp (ref "TP50")
      (value "Pad")
      (footprint "Buck:TP-0.5mm")
      (libsource (lib "") (part "Con1 pin-Small_1"))
    )
    (comp (ref "TP51")
      (value "Pad")
      (footprint "Buck:TP-0.5mm")
      (libsource (lib "") (part "Con1 pin-Small_3"))
    )
    (comp (ref "TP52")
      (value "Pad")
      (footprint "Buck:TP-0.5mm")
      (libsource (lib "") (part "Con1 pin-Small_2"))
    )
    (comp (ref "TP53")
      (value "Pad")
      (footprint "Buck:TP-0.5mm")
      (libsource (lib "") (part "Con1 pin-Small_1"))
    )
    (comp (ref "TP54")
      (value "Pad")
      (footprint "Buck:TP-0.5mm")
      (libsource (lib "") (part "Con1 pin-Small_1"))
    )
    (comp (ref "TP55")
      (value "Pad")
      (footprint "Buck:TP-0.5mm")
      (libsource (lib "MYLIB") (part "Con1 pin-Small"))
    )
    (comp (ref "TP56")
      (value "Pad")
      (footprint "Buck:TP-0.5mm")
      (libsource (lib "MYLIB") (part "Con1 pin-Small"))
    )
    (comp (ref "TP57")
      (value "Pad")
      (footprint "Buck:TP-0.5mm")
      (libsource (lib "") (part "Con1 pin-Small_1"))
    )
    (comp (ref "TP58")
      (value "Pad")
      (footprint "Buck:TP-0.5mm")
      (libsource (lib "") (part "Con1 pin-Small_2"))
    )
    (comp (ref "TP59")
      (value "Pad")
      (footprint "Buck:TP-0.5mm")
      (libsource (lib "") (part "Con1 pin-Small_3"))
    )
    (comp (ref "Trans1")
      (value "HFBR-1522Z")
      (footprint "Buck:HFBR-1522Z")
      (description "The Versatile Fiber Optic Connection, 5 V, -40 to 85 degC, 6-Pin THD, RoHS, Tube")
      (fields (field (name "MANUFACTURER") "Avago"))
      (libsource (lib "") (part "HFBR-1522Z_1"))
    )
    (comp (ref "U1")
      (value "OPA27GP")
      (footprint "P0008A")
      (fields (field (name "MANUFACTURER") "Texas Instruments"))
      (libsource (lib "Altium Content Vault") (part "TI-OPA27-X8"))
    )
    (comp (ref "U2")
      (value "OPA27GP")
      (footprint "P0008A")
      (fields (field (name "MANUFACTURER") "Texas Instruments"))
      (libsource (lib "Altium Content Vault") (part "TI-OPA27-X8"))
    )
    (comp (ref "U3")
      (value "MJWI20-24S15")
      (footprint "Buck:MJWI15-24S15")
      (libsource (lib "MYLIB") (part "MINMAX-MJWI20"))
    )
    (comp (ref "U4")
      (value "Heat sink V5583G")
      (footprint "Buck:Buck_heatsink")
      (libsource (lib "Buck") (part "Heat sink V5583G"))
    )
    (comp (ref "U5")
      (value "MJWI10-12S05")
      (footprint "Buck:MJWI15-24S05")
      (libsource (lib "MYLIB") (part "MINMAX-MJWI20"))
    )
    (comp (ref "U6")
      (value "MJWI10-12S05")
      (footprint "Buck:MJWI15-24S05")
      (libsource (lib "MYLIB") (part "MINMAX-MJWI20"))
    )
    (comp (ref "U7")
      (value "CAS 15-NP")
      (footprint "Buck:CAS 15-NP")
      (description "Current Transducer, 5 V, -40 to 85 degC, 10-Pin THD, RoHS, Tray")
      (fields (field (name "MANUFACTURER") "LEM") (field (name "PARTNUMBER") "LTSR 15-NP"))
      (libsource (lib "Buck") (part "CAS 15-NP"))
    )
    (comp (ref "U8")
      (value "SN74LVC1G17DBVT SOT23")
      (footprint "SOT95P280X145-5N:SOT95P280X145-5N")
      (description "IC BUF NON-INVERT 5.5V SC70-5")
      (libsource (lib "Miscellaneous Devices") (part "333895c48767551a2a38df23237d11a"))
    )
    (comp (ref "U9")
      (value "SI8261BBD-C-ISR")
      (footprint "SLAB-SDIP6_N")
      (fields (field (name "PARTNUMBER") "Si8261BBD-C-IS") (field (name "MANUFACTURER") "Silicon Labs"))
      (libsource (lib "Altium Content Vault") (part "SLAB-Si8261X-SDIP-6"))
    )
    (comp (ref "U10")
      (value "IXDN609SIATR")
      (footprint "Buck:IXDN609SIATR")
      (fields (field (name "PARTNUMBER") "IXDN609SI"))
      (libsource (lib "Miscellaneous Devices") (part "IXYS-IXDN609-8"))
    )
    (comp (ref "U11")
      (value "LT1764AEQ-3.3")
      (footprint "Buck:LT1764AEQ33TRPBF")
      (fields (field (name "MANUFACTURER") "Linear Technology"))
      (libsource (lib "Linear Technology Power Management LDO Linear Regulators") (part "LT1764AEQ-3.3"))
    )
    (comp (ref "U12")
      (value "MJWI20-12S05")
      (footprint "Buck:MJWI15-24S05")
      (libsource (lib "MYLIB") (part "MINMAX-MJWI20"))
    )
    (comp (ref "U13")
      (value "Temp Sensor FM50")
      (footprint "Buck:SOT-23")
      (libsource (lib "MYLIB") (part "Temp Sensor FM50"))
    )
    (comp (ref "U14")
      (value "SN74LVC1G17DBVT SOT23")
      (footprint "SOT95P280X145-5N:SOT95P280X145-5N")
      (description "IC BUF NON-INVERT 5.5V SC70-5")
      (libsource (lib "Miscellaneous Devices") (part "333895c48767551a2a38df23237d11a"))
    )
    (comp (ref "U15")
      (value "SN74LVC1G17DBVT SOT23")
      (footprint "SOT95P280X145-5N")
      (description "IC BUF NON-INVERT 5.5V SC70-5")
      (libsource (lib "Miscellaneous Devices") (part "333895c48767551a2a38df23237d11a"))
    )
    (comp (ref "U16")
      (value "PC81713NIP1B")
      (footprint "Buck:SOP-4L")
      (libsource (lib "MYLIB") (part "PC817"))
    )
    (comp (ref "U17")
      (value "PC81713NIP1B")
      (footprint "Buck:SOP-4L")
      (libsource (lib "MYLIB") (part "PC817"))
    )
    (comp (ref "U18")
      (value "AMC1311BDWV")
      (footprint "FP-DWV0008A-MFG")
      (description "IC ISOLATION 8SOIC")
      (fields
        (field (name "MANUFACTURER") "Texas Instruments")
        (field (name "OCTOPART") "https://octopart.com/amc1311bdwv-texas+instruments-88030782")
      )
      (libsource (lib "Altium Content Vault") (part "59c49c505aa37719ef898ce9673978d"))
    )
    (comp (ref "U19")
      (value "TLV2781IDBVR")
      (footprint "DBV0005A_L")
      (fields (field (name "PARTNUMBER") "OPA320AIDBVR") (field (name "MANUFACTURER") "Texas Instruments"))
      (libsource (lib "Altium Content Vault") (part "TI-OPA_SM7XXXX-DBV5"))
    )
    (comp (ref "U20")
      (value "AM3G-2412S-NZ")
      (footprint "Buck:AM3G-2412S-NZ")
      (libsource (lib "Buck") (part "AM3G-2412S-NZ"))
    )
  )
  (nets
    (net (code "1") (name "+3.3VD") (class "Default")
      (node (ref "C28") (pin "1") (pinfunction "1_1") (pintype "passive"))
      (node (ref "C32") (pin "2") (pinfunction "2_2") (pintype "passive"))
      (node (ref "C47") (pin "1") (pinfunction "1_1") (pintype "passive"))
      (node (ref "C49") (pin "2") (pinfunction "2_2") (pintype "passive"))
      (node (ref "C76") (pin "2") (pinfunction "2_2") (pintype "passive"))
      (node (ref "DS2") (pin "1") (pinfunction "A_1") (pintype "passive"))
      (node (ref "R131") (pin "2") (pinfunction "2_2") (pintype "passive"))
      (node (ref "R135") (pin "1") (pinfunction "1_1") (pintype "passive"))
      (node (ref "R83") (pin "1") (pinfunction "1_1") (pintype "passive"))
      (node (ref "R86") (pin "1") (pinfunction "1_1") (pintype "passive"))
      (node (ref "R87") (pin "1") (pinfunction "1_1") (pintype "passive"))
      (node (ref "R89") (pin "2") (pinfunction "2_2") (pintype "passive"))
      (node (ref "R91") (pin "2") (pinfunction "2_2") (pintype "passive"))
      (node (ref "R92") (pin "1") (pinfunction "1_1") (pintype "passive"))
      (node (ref "R93") (pin "1") (pinfunction "1_1") (pintype "passive"))
      (node (ref "R94") (pin "2") (pinfunction "2_2") (pintype "passive"))
      (node (ref "R95") (pin "2") (pinfunction "2_2") (pintype "passive"))
      (node (ref "R97") (pin "2") (pinfunction "2_2") (pintype "passive"))
      (node (ref "TP28") (pin "1") (pinfunction "1_1") (pintype "passive"))
      (node (ref "U11") (pin "4") (pinfunction "OUT_4") (pintype "power_in"))
      (node (ref "U11") (pin "5") (pinfunction "SENSE_5") (pintype "input"))
      (node (ref "U18") (pin "8") (pinfunction "VDD2_8") (pintype "power_in"))
      (node (ref "U19") (pin "5") (pinfunction "V+_5") (pintype "power_in"))
    )
    (net (code "2") (name "+5V_MICRO") (class "Default")
      (node (ref "C29") (pin "2") (pinfunction "2_2") (pintype "passive"))
      (node (ref "C33") (pin "2") (pinfunction "2_2") (pintype "passive"))
      (node (ref "C42") (pin "2") (pinfunction "2_2") (pintype "passive"))
      (node (ref "C48") (pin "1") (pinfunction "1_1") (pintype "passive"))
      (node (ref "C68") (pin "1") (pinfunction "1_1") (pintype "passive"))
      (node (ref "C69") (pin "1") (pinfunction "1_1") (pintype "passive"))
      (node (ref "C71") (pin "1") (pinfunction "1_1") (pintype "passive"))
      (node (ref "DS3") (pin "1") (pinfunction "A_1") (pintype "passive"))
      (node (ref "EC2") (pin "23") (pinfunction "23_23") (pintype "bidirectional"))
      (node (ref "EC2") (pin "37") (pinfunction "37_37") (pintype "bidirectional"))
      (node (ref "EC2") (pin "73") (pinfunction "73_73") (pintype "bidirectional"))
      (node (ref "EC2") (pin "9") (pinfunction "9_9") (pintype "bidirectional"))
      (node (ref "FB2") (pin "1") (pinfunction "1_1") (pintype "power_in"))
      (node (ref "J4") (pin "1") (pinfunction "1_1") (pintype "passive"))
      (node (ref "J4") (pin "14") (pinfunction "14_14") (pintype "passive"))
      (node (ref "J5") (pin "1") (pinfunction "1_1") (pintype "passive"))
      (node (ref "J5") (pin "9") (pinfunction "9_9") (pintype "passive"))
      (node (ref "OK1") (pin "4") (pinfunction "VCC_4") (pintype "power_in"))
      (node (ref "R1") (pin "1") (pinfunction "1_1") (pintype "passive"))
      (node (ref "R130") (pin "2") (pinfunction "2_2") (pintype "passive"))
      (node (ref "R134") (pin "1") (pinfunction "1_1") (pintype "passive"))
      (node (ref "R2") (pin "1") (pinfunction "1_1") (pintype "passive"))
      (node (ref "R43") (pin "2") (pinfunction "2_2") (pintype "passive"))
      (node (ref "R44") (pin "2") (pinfunction "2_2") (pintype "passive"))
      (node (ref "R57") (pin "1") (pinfunction "1_1") (pintype "passive"))
      (node (ref "R72") (pin "1") (pinfunction "1_1") (pintype "passive"))
      (node (ref "R73") (pin "1") (pinfunction "1_1") (pintype "passive"))
      (node (ref "R84") (pin "1") (pinfunction "1_1") (pintype "passive"))
      (node (ref "R88") (pin "2") (pinfunction "2_2") (pintype "passive"))
      (node (ref "R90") (pin "2") (pinfunction "2_2") (pintype "passive"))
      (node (ref "TP26") (pin "1") (pinfunction "1_1") (pintype "passive"))
      (node (ref "U12") (pin "3") (pinfunction "+Out_3") (pintype "passive"))
      (node (ref "U13") (pin "1") (pinfunction "VDD_1") (pintype "passive"))
      (node (ref "U18") (pin "1") (pinfunction "VDD1_1") (pintype "power_in"))
      (node (ref "U7") (pin "13") (pinfunction "+5V_13") (pintype "passive"))
    )
    (net (code "3") (name "+12V_Digital IN") (class "Default")
      (node (ref "C35") (pin "1") (pinfunction "1_1") (pintype "passive"))
      (node (ref "C36") (pin "1") (pinfunction "1_1") (pintype "passive"))
      (node (ref "C38") (pin "1") (pinfunction "1_1") (pintype "passive"))
      (node (ref "C40") (pin "1") (pinfunction "1_1") (pintype "passive"))
      (node (ref "C60") (pin "1") (pinfunction "1_1") (pintype "passive"))
      (node (ref "C61") (pin "1") (pinfunction "1_1") (pintype "passive"))
      (node (ref "D1") (pin "1") (pinfunction "A_1") (pintype "passive"))
      (node (ref "J3") (pin "1") (pinfunction "1_1") (pintype "passive"))
      (node (ref "K1") (pin "A2") (pinfunction "A2_A2") (pintype "passive"))
      (node (ref "TP27") (pin "1") (pinfunction "1_1") (pintype "passive"))
      (node (ref "U12") (pin "1") (pinfunction "+In_1") (pintype "passive"))
      (node (ref "U20") (pin "2") (pinfunction "2_2") (pintype "passive"))
      (node (ref "U3") (pin "1") (pinfunction "+In_1") (pintype "passive"))
      (node (ref "U5") (pin "1") (pinfunction "+In_1") (pintype "passive"))
      (node (ref "U6") (pin "1") (pinfunction "+In_1") (pintype "passive"))
    )
    (net (code "4") (name "/Display-RX") (class "Default")
      (node (ref "EC2") (pin "59") (pinfunction "59_59") (pintype "bidirectional"))
      (node (ref "OK1") (pin "1") (pinfunction "VO_1") (pintype "output"))
      (node (ref "R134") (pin "2") (pinfunction "2_2") (pintype "passive"))
      (node (ref "R136") (pin "1") (pinfunction "1_1") (pintype "passive"))
    )
    (net (code "5") (name "/Display-TX") (class "Default")
      (node (ref "EC2") (pin "57") (pinfunction "57_57") (pintype "bidirectional"))
      (node (ref "Q5") (pin "1") (pinfunction "B_1") (pintype "passive"))
    )
    (net (code "6") (name "/MCU_Reset") (class "Default")
      (node (ref "EC2") (pin "1") (pinfunction "1_1") (pintype "bidirectional"))
      (node (ref "J5") (pin "2") (pinfunction "2_2") (pintype "passive"))
      (node (ref "S1") (pin "2") (pinfunction "2_2") (pintype "passive"))
    )
    (net (code "7") (name "1") (class "Default")
      (node (ref "J5") (pin "10") (pinfunction "10_10") (pintype "passive"))
      (node (ref "P4") (pin "1") (pinfunction "1_1") (pintype "passive"))
      (node (ref "Rj5") (pin "2") (pinfunction "2_2") (pintype "passive"))
    )
    (net (code "8") (name "2") (class "Default")
      (node (ref "J5") (pin "3") (pinfunction "3_3") (pintype "passive"))
      (node (ref "P4") (pin "2") (pinfunction "2_2") (pintype "passive"))
      (node (ref "Rj6") (pin "2") (pinfunction "2_2") (pintype "passive"))
    )
    (net (code "9") (name "3") (class "Default")
      (node (ref "J4") (pin "2") (pinfunction "2_2") (pintype "passive"))
      (node (ref "P4") (pin "3") (pinfunction "3_3") (pintype "passive"))
      (node (ref "Rj7") (pin "2") (pinfunction "2_2") (pintype "passive"))
    )
    (net (code "10") (name "4") (class "Default")
      (node (ref "J4") (pin "15") (pinfunction "15_15") (pintype "passive"))
      (node (ref "P4") (pin "4") (pinfunction "4_4") (pintype "passive"))
      (node (ref "Rj8") (pin "2") (pinfunction "2_2") (pintype "passive"))
    )
    (net (code "11") (name "E FB TEMP") (class "Default")
      (node (ref "EC2") (pin "97") (pinfunction "97_97") (pintype "bidirectional"))
      (node (ref "J4") (pin "6") (pinfunction "6_6") (pintype "passive"))
    )
    (net (code "12") (name "Earth1") (class "Default")
      (node (ref "C70") (pin "1") (pinfunction "1_1") (pintype "passive"))
    )
    (net (code "13") (name "Earth2") (class "Default")
      (node (ref "C72") (pin "1") (pinfunction "1_1") (pintype "passive"))
    )
    (net (code "14") (name "Earth3") (class "Default")
      (node (ref "C73") (pin "1") (pinfunction "1_1") (pintype "passive"))
    )
    (net (code "15") (name "Earth4") (class "Default")
      (node (ref "C74") (pin "1") (pinfunction "1_1") (pintype "passive"))
    )
    (net (code "16") (name "Earth5") (class "Default")
      (node (ref "C75") (pin "1") (pinfunction "1_1") (pintype "passive"))
    )
    (net (code "17") (name "FB TEMP of the heatsink") (class "Default")
      (node (ref "EC2") (pin "109") (pinfunction "109_109") (pintype "bidirectional"))
      (node (ref "J4") (pin "23") (pinfunction "23_23") (pintype "passive"))
    )
    (net (code "18") (name "Fan FB command") (class "Default")
      (node (ref "EC2") (pin "18") (pinfunction "18_18") (pintype "bidirectional"))
      (node (ref "J4") (pin "16") (pinfunction "16_16") (pintype "passive"))
    )
    (net (code "19") (name "Fan command") (class "Default")
      (node (ref "EC2") (pin "60") (pinfunction "60_60") (pintype "bidirectional"))
      (node (ref "FB4") (pin "1") (pinfunction "1_1") (pintype "power_in"))
      (node (ref "J5") (pin "4") (pinfunction "4_4") (pintype "passive"))
    )
    (net (code "20") (name "GND_DIGITAL") (class "Default")
      (node (ref "C10") (pin "2") (pinfunction "2_2") (pintype "passive"))
      (node (ref "C28") (pin "2") (pinfunction "2_2") (pintype "passive"))
      (node (ref "C29") (pin "1") (pinfunction "1_1") (pintype "passive"))
      (node (ref "C3") (pin "2") (pinfunction "2_2") (pintype "passive"))
      (node (ref "C30") (pin "1") (pinfunction "1_1") (pintype "passive"))
      (node (ref "C31") (pin "1") (pinfunction "1_1") (pintype "passive"))
      (node (ref "C32") (pin "1") (pinfunction "1_1") (pintype "passive"))
      (node (ref "C33") (pin "1") (pinfunction "1_1") (pintype "passive"))
      (node (ref "C4") (pin "2") (pinfunction "2_2") (pintype "passive"))
      (node (ref "C41") (pin "1") (pinfunction "1_1") (pintype "passive"))
      (node (ref "C42") (pin "1") (pinfunction "1_1") (pintype "passive"))
      (node (ref "C47") (pin "2") (pinfunction "2_2") (pintype "passive"))
      (node (ref "C48") (pin "2") (pinfunction "2_2") (pintype "passive"))
      (node (ref "C49") (pin "1") (pinfunction "1_1") (pintype "passive"))
      (node (ref "C51") (pin "1") (pinfunction "1_1") (pintype "passive"))
      (node (ref "C55") (pin "2") (pinfunction "2_2") (pintype "passive"))
      (node (ref "C56") (pin "2") (pinfunction "2_2") (pintype "passive"))
      (node (ref "C57") (pin "2") (pinfunction "2_2") (pintype "passive"))
      (node (ref "C58") (pin "2") (pinfunction "2_2") (pintype "passive"))
      (node (ref "C59") (pin "1") (pinfunction "1_1") (pintype "passive"))
      (node (ref "C62") (pin "2") (pinfunction "2_2") (pintype "passive"))
      (node (ref "C63") (pin "2") (pinfunction "2_2") (pintype "passive"))
      (node (ref "C64") (pin "2") (pinfunction "2_2") (pintype "passive"))
      (node (ref "C65") (pin "1") (pinfunction "1_1") (pintype "passive"))
      (node (ref "C68") (pin "2") (pinfunction "2_2") (pintype "passive"))
      (node (ref "C69") (pin "2") (pinfunction "2_2") (pintype "passive"))
      (node (ref "C70") (pin "2") (pinfunction "2_2") (pintype "passive"))
      (node (ref "C71") (pin "2") (pinfunction "2_2") (pintype "passive"))
      (node (ref "C76") (pin "1") (pinfunction "1_1") (pintype "passive"))
      (node (ref "C9") (pin "2") (pinfunction "2_2") (pintype "passive"))
      (node (ref "EC2") (pin "10") (pinfunction "10_10") (pintype "bidirectional"))
      (node (ref "EC2") (pin "102") (pinfunction "102_102") (pintype "bidirectional"))
      (node (ref "EC2") (pin "105") (pinfunction "105_105") (pintype "bidirectional"))
      (node (ref "EC2") (pin "108") (pinfunction "108_108") (pintype "bidirectional"))
      (node (ref "EC2") (pin "111") (pinfunction "111_111") (pintype "bidirectional"))
      (node (ref "EC2") (pin "114") (pinfunction "114_114") (pintype "bidirectional"))
      (node (ref "EC2") (pin "24") (pinfunction "24_24") (pintype "bidirectional"))
      (node (ref "EC2") (pin "38") (pinfunction "38_38") (pintype "bidirectional"))
      (node (ref "EC2") (pin "56") (pinfunction "56_56") (pintype "bidirectional"))
      (node (ref "EC2") (pin "74") (pinfunction "74_74") (pintype "bidirectional"))
      (node (ref "EC2") (pin "75") (pinfunction "75_75") (pintype "bidirectional"))
      (node (ref "EC2") (pin "83") (pinfunction "83_83") (pintype "bidirectional"))
      (node (ref "EC2") (pin "86") (pinfunction "86_86") (pintype "bidirectional"))
      (node (ref "EC2") (pin "92") (pinfunction "92_92") (pintype "bidirectional"))
      (node (ref "EC2") (pin "99") (pinfunction "99_99") (pintype "bidirectional"))
      (node (ref "EC2") (pin "G2") (pinfunction "122_G2") (pintype "bidirectional"))
      (node (ref "J4") (pin "13") (pinfunction "13_13") (pintype "passive"))
      (node (ref "J4") (pin "25") (pinfunction "25_25") (pintype "passive"))
      (node (ref "J5") (pin "15") (pinfunction "15_15") (pintype "passive"))
      (node (ref "J5") (pin "8") (pinfunction "8_8") (pintype "passive"))
      (node (ref "OK1") (pin "2") (pinfunction "GND_2") (pintype "power_in"))
      (node (ref "OK1") (pin "5") (pinfunction "NC_5") (pintype "passive"))
      (node (ref "OK1") (pin "8") (pinfunction "NC_8") (pintype "passive"))
      (node (ref "Q1") (pin "5") (pinfunction "GND2_5") (pintype "power_in"))
      (node (ref "Q2") (pin "5") (pinfunction "GND2_5") (pintype "power_in"))
      (node (ref "Q5") (pin "2") (pinfunction "E_2") (pintype "passive"))
      (node (ref "R100") (pin "2") (pinfunction "2_2") (pintype "passive"))
      (node (ref "R101") (pin "2") (pinfunction "2_2") (pintype "passive"))
      (node (ref "R129") (pin "1") (pinfunction "1_1") (pintype "passive"))
      (node (ref "R132") (pin "2") (pinfunction "2_2") (pintype "passive"))
      (node (ref "R133") (pin "2") (pinfunction "2_2") (pintype "passive"))
      (node (ref "R136") (pin "2") (pinfunction "2_2") (pintype "passive"))
      (node (ref "R26") (pin "2") (pinfunction "2_2") (pintype "passive"))
      (node (ref "R28") (pin "2") (pinfunction "2_2") (pintype "passive"))
      (node (ref "R3") (pin "2") (pinfunction "2_2") (pintype "passive"))
      (node (ref "R33") (pin "2") (pinfunction "2_2") (pintype "passive"))
      (node (ref "R34") (pin "2") (pinfunction "2_2") (pintype "passive"))
      (node (ref "R4") (pin "2") (pinfunction "2_2") (pintype "passive"))
      (node (ref "R49") (pin "2") (pinfunction "2_2") (pintype "passive"))
      (node (ref "R5") (pin "2") (pinfunction "2_2") (pintype "passive"))
      (node (ref "R50") (pin "2") (pinfunction "2_2") (pintype "passive"))
      (node (ref "R56") (pin "1") (pinfunction "1_1") (pintype "passive"))
      (node (ref "R6") (pin "2") (pinfunction "2_2") (pintype "passive"))
      (node (ref "R64") (pin "1") (pinfunction "1_1") (pintype "passive"))
      (node (ref "R66") (pin "1") (pinfunction "1_1") (pintype "passive"))
      (node (ref "R68") (pin "2") (pinfunction "2_2") (pintype "passive"))
      (node (ref "R69") (pin "1") (pinfunction "1_1") (pintype "passive"))
      (node (ref "R70") (pin "2") (pinfunction "2_2") (pintype "passive"))
      (node (ref "R71") (pin "1") (pinfunction "1_1") (pintype "passive"))
      (node (ref "R78") (pin "1") (pinfunction "1_1") (pintype "passive"))
      (node (ref "R79") (pin "1") (pinfunction "1_1") (pintype "passive"))
      (node (ref "R80") (pin "2") (pinfunction "2_2") (pintype "passive"))
      (node (ref "R81") (pin "2") (pinfunction "2_2") (pintype "passive"))
      (node (ref "R82") (pin "2") (pinfunction "2_2") (pintype "passive"))
      (node (ref "R85") (pin "2") (pinfunction "2_2") (pintype "passive"))
      (node (ref "S1") (pin "1") (pinfunction "1_1") (pintype "passive"))
      (node (ref "TP31") (pin "1") (pinfunction "1_1") (pintype "passive"))
      (node (ref "TP32") (pin "1") (pinfunction "1_1") (pintype "passive"))
      (node (ref "TP34") (pin "1") (pinfunction "1_1") (pintype "passive"))
      (node (ref "TP40") (pin "1") (pinfunction "1_1") (pintype "passive"))
      (node (ref "TP41") (pin "1") (pinfunction "1_1") (pintype "passive"))
      (node (ref "TP50") (pin "1") (pinfunction "1_1") (pintype "passive"))
      (node (ref "TP53") (pin "1") (pinfunction "1_1") (pintype "passive"))
      (node (ref "TP59") (pin "1") (pinfunction "1_1") (pintype "passive"))
      (node (ref "Trans1") (pin "2") (pinfunction "CATHODE_2") (pintype "passive"))
      (node (ref "Trans1") (pin "3") (pinfunction "NC_3") (pintype "passive"))
      (node (ref "Trans1") (pin "4") (pinfunction "NC_4") (pintype "passive"))
      (node (ref "Trans1") (pin "5") (pinfunction "NC_5") (pintype "passive"))
      (node (ref "Trans1") (pin "8") (pinfunction "NC_8") (pintype "passive"))
      (node (ref "U11") (pin "3") (pinfunction "GND_3") (pintype "power_in"))
      (node (ref "U11") (pin "6") (pinfunction "TAB_6") (pintype "power_in"))
      (node (ref "U12") (pin "5") (pinfunction "-Out_5") (pintype "passive"))
      (node (ref "U13") (pin "3") (pinfunction "GND_3") (pintype "passive"))
      (node (ref "U14") (pin "3") (pinfunction "GND_3") (pintype "power_in"))
      (node (ref "U15") (pin "3") (pinfunction "GND_3") (pintype "power_in"))
      (node (ref "U16") (pin "2") (pinfunction "K_2") (pintype "passive"))
      (node (ref "U17") (pin "2") (pinfunction "K_2") (pintype "passive"))
      (node (ref "U18") (pin "3") (pinfunction "SHTDN_3") (pintype "input"))
      (node (ref "U18") (pin "4") (pinfunction "GND1_4") (pintype "power_in"))
      (node (ref "U18") (pin "5") (pinfunction "GND2_5") (pintype "power_in"))
      (node (ref "U19") (pin "2") (pinfunction "V-_2") (pintype "power_in"))
      (node (ref "U7") (pin "12") (pinfunction "0V_12") (pintype "passive"))
      (node (ref "U8") (pin "3") (pinfunction "GND_3") (pintype "power_in"))
      (node (ref "U9") (pin "3") (pinfunction "CATHODE_3") (pintype "passive"))
    )
    (net (code "21") (name "GND_High voltage-out") (class "Default")
      (node (ref "C22") (pin "2") (pinfunction "2_2") (pintype "passive"))
      (node (ref "C23") (pin "2") (pinfunction "2_2") (pintype "passive"))
      (node (ref "C24") (pin "2") (pinfunction "2_2") (pintype "passive"))
      (node (ref "C25") (pin "2") (pinfunction "2_2") (pintype "passive"))
      (node (ref "C26") (pin "2") (pinfunction "2_2") (pintype "passive"))
      (node (ref "C27") (pin "2") (pinfunction "2_2") (pintype "passive"))
      (node (ref "C72") (pin "2") (pinfunction "2_2") (pintype "passive"))
      (node (ref "C78") (pin "1") (pinfunction "1_1") (pintype "passive"))
      (node (ref "CR4") (pin "1") (pinfunction "A_1") (pintype "passive"))
      (node (ref "D3") (pin "2") (pinfunction "A_2") (pintype "passive"))
      (node (ref "D9") (pin "2") (pinfunction "A_2") (pintype "passive"))
      (node (ref "P1") (pin "3") (pinfunction "3_3") (pintype "passive"))
      (node (ref "P1") (pin "4") (pinfunction "4_4") (pintype "passive"))
      (node (ref "P2") (pin "3") (pinfunction "3_3") (pintype "passive"))
      (node (ref "P2") (pin "4") (pinfunction "4_4") (pintype "passive"))
      (node (ref "R102") (pin "2") (pinfunction "2_2") (pintype "passive"))
      (node (ref "R11") (pin "1") (pinfunction "1_1") (pintype "passive"))
      (node (ref "R110") (pin "2") (pinfunction "2_2") (pintype "passive"))
      (node (ref "R111") (pin "2") (pinfunction "2_2") (pintype "passive"))
      (node (ref "R112") (pin "2") (pinfunction "2_2") (pintype "passive"))
      (node (ref "R113") (pin "2") (pinfunction "2_2") (pintype "passive"))
      (node (ref "R114") (pin "2") (pinfunction "2_2") (pintype "passive"))
      (node (ref "R116") (pin "2") (pinfunction "2_2") (pintype "passive"))
      (node (ref "R117") (pin "2") (pinfunction "2_2") (pintype "passive"))
      (node (ref "R12") (pin "1") (pinfunction "1_1") (pintype "passive"))
      (node (ref "R120") (pin "1") (pinfunction "1_1") (pintype "passive"))
      (node (ref "R13") (pin "1") (pinfunction "1_1") (pintype "passive"))
      (node (ref "R14") (pin "1") (pinfunction "1_1") (pintype "passive"))
      (node (ref "TP12") (pin "1") (pinfunction "1_1") (pintype "passive"))
      (node (ref "TP14") (pin "1") (pinfunction "1_1") (pintype "passive"))
      (node (ref "TP2") (pin "1") (pinfunction "1_1") (pintype "passive"))
      (node (ref "TP44") (pin "1") (pinfunction "1_1") (pintype "passive"))
      (node (ref "TP45") (pin "1") (pinfunction "1_1") (pintype "passive"))
    )
    (net (code "22") (name "GND_IN") (class "Default")
      (node (ref "C35") (pin "2") (pinfunction "2_2") (pintype "passive"))
      (node (ref "C36") (pin "2") (pinfunction "2_2") (pintype "passive"))
      (node (ref "C38") (pin "2") (pinfunction "2_2") (pintype "passive"))
      (node (ref "C40") (pin "2") (pinfunction "2_2") (pintype "passive"))
      (node (ref "C60") (pin "2") (pinfunction "2_2") (pintype "passive"))
      (node (ref "C61") (pin "2") (pinfunction "2_2") (pintype "passive"))
      (node (ref "C73") (pin "2") (pinfunction "2_2") (pintype "passive"))
      (node (ref "J3") (pin "2") (pinfunction "2_2") (pintype "passive"))
      (node (ref "TP33") (pin "1") (pinfunction "1_1") (pintype "passive"))
      (node (ref "TP38") (pin "1") (pinfunction "1_1") (pintype "passive"))
      (node (ref "U12") (pin "2") (pinfunction "-In_2") (pintype "passive"))
      (node (ref "U16") (pin "3") (pinfunction "E_3") (pintype "passive"))
      (node (ref "U17") (pin "3") (pinfunction "E_3") (pintype "passive"))
      (node (ref "U20") (pin "1") (pinfunction "1_1") (pintype "passive"))
      (node (ref "U3") (pin "2") (pinfunction "-In_2") (pintype "passive"))
      (node (ref "U5") (pin "2") (pinfunction "-In_2") (pintype "passive"))
      (node (ref "U6") (pin "2") (pinfunction "-In_2") (pintype "passive"))
    )
    (net (code "23") (name "GND_MB") (class "Default")
      (node (ref "C34") (pin "2") (pinfunction "2_2") (pintype "passive"))
      (node (ref "C45") (pin "1") (pinfunction "1_1") (pintype "passive"))
      (node (ref "C66") (pin "2") (pinfunction "2_2") (pintype "passive"))
      (node (ref "C67") (pin "2") (pinfunction "2_2") (pintype "passive"))
      (node (ref "CR7") (pin "1") (pinfunction "A_1") (pintype "passive"))
      (node (ref "R115") (pin "2") (pinfunction "2_2") (pintype "passive"))
      (node (ref "R63") (pin "2") (pinfunction "2_2") (pintype "passive"))
      (node (ref "R96") (pin "2") (pinfunction "2_2") (pintype "passive"))
      (node (ref "TP51") (pin "1") (pinfunction "1_1") (pintype "passive"))
      (node (ref "TP9") (pin "1") (pinfunction "1_1") (pintype "passive"))
      (node (ref "U3") (pin "5") (pinfunction "-Out_5") (pintype "passive"))
      (node (ref "U9") (pin "4") (pinfunction "GND_4") (pintype "power_in"))
    )
    (net (code "24") (name "GND_VDD Sensor voltage input") (class "Default")
      (node (ref "C37") (pin "2") (pinfunction "2_2") (pintype "passive"))
      (node (ref "C75") (pin "2") (pinfunction "2_2") (pintype "passive"))
      (node (ref "R118") (pin "1") (pinfunction "1_1") (pintype "passive"))
      (node (ref "R31") (pin "1") (pinfunction "1_1") (pintype "passive"))
      (node (ref "R99") (pin "2") (pinfunction "2_2") (pintype "passive"))
      (node (ref "TP21") (pin "1") (pinfunction "1_1") (pintype "passive"))
      (node (ref "U5") (pin "5") (pinfunction "-Out_5") (pintype "passive"))
    )
    (net (code "25") (name "GND_VDD Sensor voltage out") (class "Default")
      (node (ref "C39") (pin "2") (pinfunction "2_2") (pintype "passive"))
      (node (ref "C74") (pin "2") (pinfunction "2_2") (pintype "passive"))
      (node (ref "R119") (pin "1") (pinfunction "1_1") (pintype "passive"))
      (node (ref "R32") (pin "1") (pinfunction "1_1") (pintype "passive"))
      (node (ref "R98") (pin "2") (pinfunction "2_2") (pintype "passive"))
      (node (ref "TP23") (pin "1") (pinfunction "1_1") (pintype "passive"))
      (node (ref "TP25") (pin "1") (pinfunction "1_1") (pintype "passive"))
      (node (ref "U6") (pin "5") (pinfunction "-Out_5") (pintype "passive"))
    )
    (net (code "26") (name "Input 500V") (class "Default")
      (node (ref "F2") (pin "1") (pinfunction "1_1") (pintype "passive"))
      (node (ref "P1") (pin "1") (pinfunction "1_1") (pintype "passive"))
      (node (ref "P1") (pin "2") (pinfunction "2_2") (pintype "passive"))
      (node (ref "R120") (pin "2") (pinfunction "2_2") (pintype "passive"))
      (node (ref "R7") (pin "2") (pinfunction "2_2") (pintype "passive"))
      (node (ref "R8") (pin "2") (pinfunction "2_2") (pintype "passive"))
      (node (ref "TP3") (pin "1") (pinfunction "1_1") (pintype "passive"))
      (node (ref "TP42") (pin "1") (pinfunction "1_1") (pintype "passive"))
    )
    (net (code "27") (name "Input voltage of Buck") (class "Default")
      (node (ref "EC2") (pin "106") (pinfunction "106_106") (pintype "bidirectional"))
      (node (ref "FB6") (pin "2") (pinfunction "2_2") (pintype "power_in"))
      (node (ref "J5") (pin "14") (pinfunction "14_14") (pintype "passive"))
      (node (ref "TP29") (pin "1") (pinfunction "1_1") (pintype "passive"))
    )
    (net (code "28") (name "Input voltage of FB") (class "Default")
      (node (ref "EC2") (pin "103") (pinfunction "103_103") (pintype "bidirectional"))
      (node (ref "J4") (pin "24") (pinfunction "24_24") (pintype "passive"))
    )
    (net (code "29") (name "M1 FB command") (class "Default")
      (node (ref "EC2") (pin "34") (pinfunction "34_34") (pintype "bidirectional"))
      (node (ref "J4") (pin "4") (pinfunction "4_4") (pintype "passive"))
    )
    (net (code "30") (name "M1 command") (class "Default")
      (node (ref "EC2") (pin "72") (pinfunction "72_72") (pintype "bidirectional"))
      (node (ref "FB1") (pin "1") (pinfunction "1_1") (pintype "power_in"))
      (node (ref "J5") (pin "12") (pinfunction "12_12") (pintype "passive"))
      (node (ref "R101") (pin "1") (pinfunction "1_1") (pintype "passive"))
      (node (ref "TP47") (pin "1") (pinfunction "1_1") (pintype "passive"))
    )
    (net (code "31") (name "M2 FB command") (class "Default")
      (node (ref "EC2") (pin "36") (pinfunction "36_36") (pintype "bidirectional"))
      (node (ref "J4") (pin "17") (pinfunction "17_17") (pintype "passive"))
    )
    (net (code "32") (name "M3 FB command") (class "Default")
      (node (ref "EC2") (pin "40") (pinfunction "40_40") (pintype "bidirectional"))
      (node (ref "J4") (pin "5") (pinfunction "5_5") (pintype "passive"))
    )
    (net (code "33") (name "M4 FB command") (class "Default")
      (node (ref "EC2") (pin "42") (pinfunction "42_42") (pintype "bidirectional"))
      (node (ref "J4") (pin "18") (pinfunction "18_18") (pintype "passive"))
    )
    (net (code "34") (name "Net-(C1-Pad2)") (class "Default")
      (node (ref "C1") (pin "2") (pinfunction "2_2") (pintype "passive"))
      (node (ref "R15") (pin "2") (pinfunction "2_2") (pintype "passive"))
    )
    (net (code "35") (name "Net-(C2-Pad2)") (class "Default")
      (node (ref "C2") (pin "2") (pinfunction "2_2") (pintype "passive"))
      (node (ref "R16") (pin "2") (pinfunction "2_2") (pintype "passive"))
    )
    (net (code "36") (name "Net-(C13-Pad2)") (class "Default")
      (node (ref "C13") (pin "2") (pinfunction "2_2") (pintype "passive"))
      (node (ref "R45") (pin "2") (pinfunction "2_2") (pintype "passive"))
      (node (ref "R47") (pin "1") (pinfunction "1_1") (pintype "passive"))
    )
    (net (code "37") (name "Net-(C14-Pad2)") (class "Default")
      (node (ref "C14") (pin "2") (pinfunction "2_2") (pintype "passive"))
      (node (ref "R46") (pin "2") (pinfunction "2_2") (pintype "passive"))
      (node (ref "R48") (pin "1") (pinfunction "1_1") (pintype "passive"))
    )
    (net (code "38") (name "Net-(C15-Pad1)") (class "Default")
      (node (ref "C15") (pin "1") (pinfunction "1_1") (pintype "passive"))
      (node (ref "C43") (pin "1") (pinfunction "1_1") (pintype "passive"))
      (node (ref "C44") (pin "1") (pinfunction "1_1") (pintype "passive"))
      (node (ref "R52") (pin "1") (pinfunction "1_1") (pintype "passive"))
    )
    (net (code "39") (name "Net-(C16-Pad2)") (class "Default")
      (node (ref "C16") (pin "2") (pinfunction "2_2") (pintype "passive"))
      (node (ref "C17") (pin "2") (pinfunction "2_2") (pintype "passive"))
      (node (ref "C22") (pin "1") (pinfunction "1_1") (pintype "passive"))
      (node (ref "C23") (pin "1") (pinfunction "1_1") (pintype "passive"))
    )
    (net (code "40") (name "Net-(C18-Pad2)") (class "Default")
      (node (ref "C18") (pin "2") (pinfunction "2_2") (pintype "passive"))
      (node (ref "C19") (pin "2") (pinfunction "2_2") (pintype "passive"))
      (node (ref "C20") (pin "2") (pinfunction "2_2") (pintype "passive"))
      (node (ref "C21") (pin "2") (pinfunction "2_2") (pintype "passive"))
      (node (ref "C24") (pin "1") (pinfunction "1_1") (pintype "passive"))
      (node (ref "C25") (pin "1") (pinfunction "1_1") (pintype "passive"))
      (node (ref "C26") (pin "1") (pinfunction "1_1") (pintype "passive"))
      (node (ref "C27") (pin "1") (pinfunction "1_1") (pintype "passive"))
    )
    (net (code "41") (name "Net-(C50-Pad1)") (class "Default")
      (node (ref "C50") (pin "1") (pinfunction "1_1") (pintype "passive"))
      (node (ref "R127") (pin "2") (pinfunction "2_2") (pintype "passive"))
      (node (ref "R128") (pin "1") (pinfunction "1_1") (pintype "passive"))
    )
    (net (code "42") (name "Net-(C50-Pad2)") (class "Default")
      (node (ref "C50") (pin "2") (pinfunction "2_2") (pintype "passive"))
      (node (ref "R124") (pin "2") (pinfunction "2_2") (pintype "passive"))
      (node (ref "R125") (pin "1") (pinfunction "1_1") (pintype "passive"))
    )
    (net (code "43") (name "Net-(C51-Pad2)") (class "Default")
      (node (ref "C51") (pin "2") (pinfunction "2_2") (pintype "passive"))
      (node (ref "FB10") (pin "1") (pinfunction "1_1") (pintype "power_in"))
      (node (ref "R126") (pin "2") (pinfunction "2_2") (pintype "passive"))
      (node (ref "TP56") (pin "1") (pinfunction "1_1") (pintype "passive"))
    )
    (net (code "44") (name "Net-(C52-Pad2)") (class "Default")
      (node (ref "C52") (pin "2") (pinfunction "2_2") (pintype "passive"))
      (node (ref "R114") (pin "1") (pinfunction "1_1") (pintype "passive"))
    )
    (net (code "45") (name "Net-(C77-Pad1)") (class "Default")
      (node (ref "C77") (pin "1") (pinfunction "1_1") (pintype "passive"))
      (node (ref "R102") (pin "1") (pinfunction "1_1") (pintype "passive"))
    )
    (net (code "46") (name "Net-(CR4-K)") (class "Default")
      (node (ref "CR4") (pin "2") (pinfunction "K_2") (pintype "passive"))
      (node (ref "CR5") (pin "2") (pinfunction "K_2") (pintype "passive"))
    )
    (net (code "47") (name "Net-(CR5-A)") (class "Default")
      (node (ref "CR5") (pin "1") (pinfunction "A_1") (pintype "passive"))
      (node (ref "F2") (pin "2") (pinfunction "2_2") (pintype "passive"))
      (node (ref "K1") (pin "14") (pinfunction "14_14") (pintype "passive"))
      (node (ref "RT1") (pin "2") (pinfunction "2_2") (pintype "passive"))
    )
    (net (code "48") (name "Net-(CR6-A)") (class "Default")
      (node (ref "CR6") (pin "1") (pinfunction "A_1") (pintype "passive"))
      (node (ref "CR7") (pin "2") (pinfunction "K_2") (pintype "passive"))
      (node (ref "R104") (pin "2") (pinfunction "2_2") (pintype "passive"))
      (node (ref "R61") (pin "1") (pinfunction "1_1") (pintype "passive"))
      (node (ref "TP49") (pin "1") (pinfunction "1_1") (pintype "passive"))
      (node (ref "U9") (pin "5") (pinfunction "VO_5") (pintype "output"))
    )
    (net (code "49") (name "Net-(CR8-A)") (class "Default")
      (node (ref "C15") (pin "2") (pinfunction "2_2") (pintype "passive"))
      (node (ref "C43") (pin "2") (pinfunction "2_2") (pintype "passive"))
      (node (ref "C44") (pin "2") (pinfunction "2_2") (pintype "passive"))
      (node (ref "C52") (pin "1") (pinfunction "1_1") (pintype "passive"))
      (node (ref "C53") (pin "2") (pinfunction "2_2") (pintype "passive"))
      (node (ref "C54") (pin "2") (pinfunction "2_2") (pintype "passive"))
      (node (ref "C77") (pin "2") (pinfunction "2_2") (pintype "passive"))
      (node (ref "CR8") (pin "1") (pinfunction "A_1") (pintype "passive"))
      (node (ref "D10") (pin "1") (pinfunction "A_1") (pintype "passive"))
      (node (ref "D11") (pin "1") (pinfunction "A_1") (pintype "passive"))
      (node (ref "D2") (pin "1") (pinfunction "A_1") (pintype "passive"))
      (node (ref "D3") (pin "1") (pinfunction "C_1") (pintype "passive"))
      (node (ref "D7") (pin "1") (pinfunction "A_1") (pintype "passive"))
      (node (ref "D9") (pin "1") (pinfunction "C_1") (pintype "passive"))
      (node (ref "L3") (pin "1") (pinfunction "1_1") (pintype "passive"))
      (node (ref "Q3") (pin "3") (pinfunction "SOURCE_3") (pintype "passive"))
      (node (ref "Q4") (pin "3") (pinfunction "SOURCE_3") (pintype "passive"))
      (node (ref "R104") (pin "1") (pinfunction "1_1") (pintype "passive"))
      (node (ref "R115") (pin "1") (pinfunction "1_1") (pintype "passive"))
      (node (ref "R53") (pin "2") (pinfunction "2_2") (pintype "passive"))
      (node (ref "R54") (pin "2") (pinfunction "2_2") (pintype "passive"))
      (node (ref "R63") (pin "1") (pinfunction "1_1") (pintype "passive"))
      (node (ref "U10") (pin "4") (pinfunction "GND_4") (pintype "power_in"))
      (node (ref "U10") (pin "5") (pinfunction "GND_5") (pintype "power_in"))
    )
    (net (code "50") (name "Net-(CR8-K)") (class "Default")
      (node (ref "CR8") (pin "2") (pinfunction "K_2") (pintype "passive"))
      (node (ref "CR9") (pin "1") (pinfunction "A_1") (pintype "passive"))
      (node (ref "D12") (pin "2") (pinfunction "C_2") (pintype "passive"))
      (node (ref "D8") (pin "2") (pinfunction "C_2") (pintype "passive"))
      (node (ref "R58") (pin "1") (pinfunction "1_1") (pintype "passive"))
      (node (ref "R65") (pin "1") (pinfunction "1_1") (pintype "passive"))
      (node (ref "TP52") (pin "1") (pinfunction "1_1") (pintype "passive"))
      (node (ref "U10") (pin "6") (pinfunction "OUT_6") (pintype "output"))
      (node (ref "U10") (pin "7") (pinfunction "OUT_7") (pintype "output"))
    )
    (net (code "51") (name "Net-(D1-K)") (class "Default")
      (node (ref "D1") (pin "2") (pinfunction "K_2") (pintype "passive"))
      (node (ref "D5") (pin "2") (pinfunction "K_2") (pintype "passive"))
    )
    (net (code "52") (name "Net-(D4-A)") (class "Default")
      (node (ref "D4") (pin "1") (pinfunction "A_1") (pintype "passive"))
      (node (ref "P3") (pin "1") (pinfunction "1_1") (pintype "passive"))
      (node (ref "U20") (pin "6") (pinfunction "6_6") (pintype "passive"))
    )
    (net (code "53") (name "Net-(D4-K)") (class "Default")
      (node (ref "D4") (pin "2") (pinfunction "K_2") (pintype "passive"))
      (node (ref "D6") (pin "2") (pinfunction "K_2") (pintype "passive"))
    )
    (net (code "54") (name "Net-(D6-A)") (class "Default")
      (node (ref "D6") (pin "1") (pinfunction "A_1") (pintype "passive"))
      (node (ref "P3") (pin "2") (pinfunction "2_2") (pintype "passive"))
      (node (ref "U20") (pin "7") (pinfunction "7_7") (pintype "passive"))
    )
    (net (code "55") (name "Net-(D7-C)") (class "Default")
      (node (ref "C16") (pin "1") (pinfunction "1_1") (pintype "passive"))
      (node (ref "C17") (pin "1") (pinfunction "1_1") (pintype "passive"))
      (node (ref "C78") (pin "2") (pinfunction "2_2") (pintype "passive"))
      (node (ref "D7") (pin "2") (pinfunction "C_2") (pintype "passive"))
      (node (ref "K1") (pin "11") (pinfunction "11_11") (pintype "passive"))
      (node (ref "Q3") (pin "2") (pinfunction "DRAIN_2") (pintype "passive"))
      (node (ref "Q4") (pin "2") (pinfunction "DRAIN_2") (pintype "passive"))
      (node (ref "R106") (pin "1") (pinfunction "1_1") (pintype "passive"))
      (node (ref "R107") (pin "1") (pinfunction "1_1") (pintype "passive"))
      (node (ref "R52") (pin "2") (pinfunction "2_2") (pintype "passive"))
      (node (ref "RT1") (pin "1") (pinfunction "1_1") (pintype "passive"))
      (node (ref "TP43") (pin "1") (pinfunction "1_1") (pintype "passive"))
    )
    (net (code "56") (name "Net-(D10-C)") (class "Default")
      (node (ref "D10") (pin "2") (pinfunction "C_2") (pintype "passive"))
      (node (ref "D11") (pin "2") (pinfunction "C_2") (pintype "passive"))
      (node (ref "D2") (pin "2") (pinfunction "C_2") (pintype "passive"))
      (node (ref "Q3") (pin "1") (pinfunction "GATE_1") (pintype "passive"))
      (node (ref "Q4") (pin "1") (pinfunction "GATE_1") (pintype "passive"))
      (node (ref "R103") (pin "2") (pinfunction "2_2") (pintype "passive"))
      (node (ref "R105") (pin "2") (pinfunction "2_2") (pintype "passive"))
      (node (ref "R53") (pin "1") (pinfunction "1_1") (pintype "passive"))
      (node (ref "R54") (pin "1") (pinfunction "1_1") (pintype "passive"))
      (node (ref "R62") (pin "2") (pinfunction "2_2") (pintype "passive"))
    )
    (net (code "57") (name "Net-(D12-A)") (class "Default")
      (node (ref "D12") (pin "1") (pinfunction "A_1") (pintype "passive"))
      (node (ref "D8") (pin "1") (pinfunction "A_1") (pintype "passive"))
      (node (ref "R103") (pin "1") (pinfunction "1_1") (pintype "passive"))
      (node (ref "R105") (pin "1") (pinfunction "1_1") (pintype "passive"))
    )
    (net (code "58") (name "Net-(DS2-K)") (class "Default")
      (node (ref "DS2") (pin "2") (pinfunction "K_2") (pintype "passive"))
      (node (ref "R68") (pin "1") (pinfunction "1_1") (pintype "passive"))
    )
    (net (code "59") (name "Net-(DS3-K)") (class "Default")
      (node (ref "DS3") (pin "2") (pinfunction "K_2") (pintype "passive"))
      (node (ref "R70") (pin "1") (pinfunction "1_1") (pintype "passive"))
    )
    (net (code "60") (name "Net-(DS4-A)") (class "Default")
      (node (ref "DS4") (pin "1") (pinfunction "A_1") (pintype "passive"))
      (node (ref "R75") (pin "1") (pinfunction "1_1") (pintype "passive"))
      (node (ref "TP35") (pin "1") (pinfunction "1_1") (pintype "passive"))
      (node (ref "U14") (pin "4") (pinfunction "Y_4") (pintype "output"))
    )
    (net (code "61") (name "Net-(DS4-K)") (class "Default")
      (node (ref "DS4") (pin "2") (pinfunction "K_2") (pintype "passive"))
      (node (ref "R80") (pin "1") (pinfunction "1_1") (pintype "passive"))
    )
    (net (code "62") (name "Net-(DS5-A)") (class "Default")
      (node (ref "DS5") (pin "1") (pinfunction "A_1") (pintype "passive"))
      (node (ref "R77") (pin "1") (pinfunction "1_1") (pintype "passive"))
      (node (ref "TP37") (pin "1") (pinfunction "1_1") (pintype "passive"))
      (node (ref "U15") (pin "4") (pinfunction "Y_4") (pintype "output"))
    )
    (net (code "63") (name "Net-(DS5-K)") (class "Default")
      (node (ref "DS5") (pin "2") (pinfunction "K_2") (pintype "passive"))
      (node (ref "R81") (pin "1") (pinfunction "1_1") (pintype "passive"))
    )
    (net (code "64") (name "Net-(DS6-A)") (class "Default")
      (node (ref "DS6") (pin "1") (pinfunction "A_1") (pintype "passive"))
      (node (ref "R60") (pin "1") (pinfunction "1_1") (pintype "passive"))
      (node (ref "TP48") (pin "1") (pinfunction "1_1") (pintype "passive"))
      (node (ref "U8") (pin "4") (pinfunction "Y_4") (pintype "output"))
    )
    (net (code "65") (name "Net-(DS6-K)") (class "Default")
      (node (ref "DS6") (pin "2") (pinfunction "K_2") (pintype "passive"))
      (node (ref "R82") (pin "1") (pinfunction "1_1") (pintype "passive"))
    )
    (net (code "66") (name "Net-(DS7-K)") (class "Default")
      (node (ref "DS7") (pin "2") (pinfunction "K_2") (pintype "passive"))
      (node (ref "R96") (pin "1") (pinfunction "1_1") (pintype "passive"))
    )
    (net (code "67") (name "Net-(DS8-K)") (class "Default")
      (node (ref "DS8") (pin "2") (pinfunction "K_2") (pintype "passive"))
      (node (ref "R98") (pin "1") (pinfunction "1_1") (pintype "passive"))
    )
    (net (code "68") (name "Net-(DS9-K)") (class "Default")
      (node (ref "DS9") (pin "2") (pinfunction "K_2") (pintype "passive"))
      (node (ref "R99") (pin "1") (pinfunction "1_1") (pintype "passive"))
    )
    (net (code "69") (name "Net-(EC2-Pad64)") (class "Default")
      (node (ref "EC2") (pin "64") (pinfunction "64_64") (pintype "bidirectional"))
      (node (ref "Rj1") (pin "2") (pinfunction "2_2") (pintype "passive"))
    )
    (net (code "70") (name "Net-(EC2-Pad65)") (class "Default")
      (node (ref "EC2") (pin "65") (pinfunction "65_65") (pintype "bidirectional"))
      (node (ref "Rj5") (pin "1") (pinfunction "1_1") (pintype "passive"))
    )
    (net (code "71") (name "Net-(EC2-Pad66)") (class "Default")
      (node (ref "EC2") (pin "66") (pinfunction "66_66") (pintype "bidirectional"))
      (node (ref "Rj2") (pin "2") (pinfunction "2_2") (pintype "passive"))
    )
    (net (code "72") (name "Net-(EC2-Pad67)") (class "Default")
      (node (ref "EC2") (pin "67") (pinfunction "67_67") (pintype "bidirectional"))
      (node (ref "Rj6") (pin "1") (pinfunction "1_1") (pintype "passive"))
    )
    (net (code "73") (name "Net-(EC2-Pad68)") (class "Default")
      (node (ref "EC2") (pin "68") (pinfunction "68_68") (pintype "bidirectional"))
      (node (ref "Rj3") (pin "2") (pinfunction "2_2") (pintype "passive"))
    )
    (net (code "74") (name "Net-(EC2-Pad69)") (class "Default")
      (node (ref "EC2") (pin "69") (pinfunction "69_69") (pintype "bidirectional"))
      (node (ref "Rj7") (pin "1") (pinfunction "1_1") (pintype "passive"))
    )
    (net (code "75") (name "Net-(EC2-Pad70)") (class "Default")
      (node (ref "EC2") (pin "70") (pinfunction "70_70") (pintype "bidirectional"))
      (node (ref "Rj4") (pin "2") (pinfunction "2_2") (pintype "passive"))
    )
    (net (code "76") (name "Net-(EC2-Pad71)") (class "Default")
      (node (ref "EC2") (pin "71") (pinfunction "71_71") (pintype "bidirectional"))
      (node (ref "Rj8") (pin "1") (pinfunction "1_1") (pintype "passive"))
    )
    (net (code "77") (name "Net-(EC2-Pad94)") (class "Default")
      (node (ref "EC2") (pin "94") (pinfunction "94_94") (pintype "bidirectional"))
      (node (ref "Rj9") (pin "2") (pinfunction "2_2") (pintype "passive"))
    )
    (net (code "78") (name "Net-(EC2-Pad95)") (class "Default")
      (node (ref "EC2") (pin "95") (pinfunction "95_95") (pintype "bidirectional"))
      (node (ref "Rj10") (pin "1") (pinfunction "1_1") (pintype "passive"))
    )
    (net (code "79") (name "Net-(EC2-Pad96)") (class "Default")
      (node (ref "EC2") (pin "96") (pinfunction "96_96") (pintype "bidirectional"))
      (node (ref "Rj11") (pin "2") (pinfunction "2_2") (pintype "passive"))
    )
    (net (code "80") (name "Net-(EC2-Pad100)") (class "Default")
      (node (ref "EC2") (pin "100") (pinfunction "100_100") (pintype "bidirectional"))
      (node (ref "Rj12") (pin "2") (pinfunction "2_2") (pintype "passive"))
    )
    (net (code "81") (name "Net-(F3-Pad1)") (class "Default")
      (node (ref "F3") (pin "1") (pinfunction "1_1") (pintype "passive"))
      (node (ref "U7") (pin "10") (pinfunction "OUT_10") (pintype "passive"))
      (node (ref "U7") (pin "8") (pinfunction "OUT_8") (pintype "passive"))
      (node (ref "U7") (pin "9") (pinfunction "OUT_9") (pintype "passive"))
    )
    (net (code "82") (name "Net-(F3-Pad2)") (class "Default")
      (node (ref "F3") (pin "2") (pinfunction "2_2") (pintype "passive"))
      (node (ref "P2") (pin "1") (pinfunction "1_1") (pintype "passive"))
      (node (ref "P2") (pin "2") (pinfunction "2_2") (pintype "passive"))
    )
    (net (code "83") (name "Net-(FB1-Pad2)") (class "Default")
      (node (ref "FB1") (pin "2") (pinfunction "2_2") (pintype "power_in"))
      (node (ref "R133") (pin "1") (pinfunction "1_1") (pintype "passive"))
      (node (ref "R59") (pin "1") (pinfunction "1_1") (pintype "passive"))
    )
    (net (code "84") (name "Net-(FB3-Pad2)") (class "Default")
      (node (ref "FB3") (pin "2") (pinfunction "2_2") (pintype "power_in"))
      (node (ref "R67") (pin "2") (pinfunction "2_2") (pintype "passive"))
    )
    (net (code "85") (name "Net-(FB4-Pad2)") (class "Default")
      (node (ref "FB4") (pin "2") (pinfunction "2_2") (pintype "power_in"))
      (node (ref "R74") (pin "1") (pinfunction "1_1") (pintype "passive"))
    )
    (net (code "86") (name "Net-(FB5-Pad2)") (class "Default")
      (node (ref "FB5") (pin "2") (pinfunction "2_2") (pintype "power_in"))
      (node (ref "R76") (pin "1") (pinfunction "1_1") (pintype "passive"))
    )
    (net (code "87") (name "Net-(FB6-Pad1)") (class "Default")
      (node (ref "FB6") (pin "1") (pinfunction "1_1") (pintype "power_in"))
      (node (ref "R47") (pin "2") (pinfunction "2_2") (pintype "passive"))
      (node (ref "R49") (pin "1") (pinfunction "1_1") (pintype "passive"))
    )
    (net (code "88") (name "Net-(FB7-Pad1)") (class "Default")
      (node (ref "FB7") (pin "1") (pinfunction "1_1") (pintype "power_in"))
      (node (ref "R48") (pin "2") (pinfunction "2_2") (pintype "passive"))
      (node (ref "R50") (pin "1") (pinfunction "1_1") (pintype "passive"))
    )
    (net (code "89") (name "Net-(FB8-Pad1)") (class "Default")
      (node (ref "FB8") (pin "1") (pinfunction "1_1") (pintype "power_in"))
      (node (ref "R67") (pin "1") (pinfunction "1_1") (pintype "passive"))
      (node (ref "R69") (pin "2") (pinfunction "2_2") (pintype "passive"))
    )
    (net (code "90") (name "Net-(FB9-Pad1)") (class "Default")
      (node (ref "FB9") (pin "1") (pinfunction "1_1") (pintype "power_in"))
      (node (ref "P3") (pin "4") (pinfunction "4_4") (pintype "passive"))
      (node (ref "R85") (pin "1") (pinfunction "1_1") (pintype "passive"))
    )
    (net (code "91") (name "Net-(J6-Pad2)") (class "Default")
      (node (ref "J6") (pin "2") (pinfunction "2_2") (pintype "passive"))
      (node (ref "U7") (pin "1") (pinfunction "IN_1") (pintype "passive"))
      (node (ref "U7") (pin "2") (pinfunction "IN_2") (pintype "passive"))
      (node (ref "U7") (pin "3") (pinfunction "IN_3") (pintype "passive"))
    )
    (net (code "92") (name "Net-(P3-Pad3)") (class "Default")
      (node (ref "P3") (pin "3") (pinfunction "3_3") (pintype "passive"))
      (node (ref "R83") (pin "2") (pinfunction "2_2") (pintype "passive"))
      (node (ref "R84") (pin "2") (pinfunction "2_2") (pintype "passive"))
    )
    (net (code "93") (name "Net-(Q1-GND1)") (class "Default")
      (node (ref "C5") (pin "2") (pinfunction "2_2") (pintype "passive"))
      (node (ref "C6") (pin "2") (pinfunction "2_2") (pintype "passive"))
      (node (ref "Q1") (pin "4") (pinfunction "GND1_4") (pintype "power_in"))
      (node (ref "R117") (pin "1") (pinfunction "1_1") (pintype "passive"))
      (node (ref "R118") (pin "2") (pinfunction "2_2") (pintype "passive"))
    )
    (net (code "94") (name "Net-(Q1-SHDN)") (class "Default")
      (node (ref "Q1") (pin "3") (pinfunction "SHDN_3") (pintype "input"))
      (node (ref "R31") (pin "2") (pinfunction "2_2") (pintype "passive"))
    )
    (net (code "95") (name "Net-(Q1-VDD2)") (class "Default")
      (node (ref "C3") (pin "1") (pinfunction "1_1") (pintype "passive"))
      (node (ref "C58") (pin "1") (pinfunction "1_1") (pintype "passive"))
      (node (ref "Q1") (pin "8") (pinfunction "VDD2_8") (pintype "power_in"))
      (node (ref "R88") (pin "1") (pinfunction "1_1") (pintype "passive"))
      (node (ref "R89") (pin "1") (pinfunction "1_1") (pintype "passive"))
      (node (ref "TP8") (pin "1") (pinfunction "1_1") (pintype "passive"))
    )
    (net (code "96") (name "Net-(Q1-VIN)") (class "Default")
      (node (ref "C5") (pin "1") (pinfunction "1_1") (pintype "passive"))
      (node (ref "Q1") (pin "2") (pinfunction "VIN_2") (pintype "power_in"))
      (node (ref "R11") (pin "2") (pinfunction "2_2") (pintype "passive"))
      (node (ref "R12") (pin "2") (pinfunction "2_2") (pintype "passive"))
      (node (ref "R7") (pin "1") (pinfunction "1_1") (pintype "passive"))
      (node (ref "R8") (pin "1") (pinfunction "1_1") (pintype "passive"))
      (node (ref "TP7") (pin "1") (pinfunction "1_1") (pintype "passive"))
    )
    (net (code "97") (name "Net-(Q1-VOUT+)") (class "Default")
      (node (ref "Q1") (pin "7") (pinfunction "VOUT+_7") (pintype "passive"))
      (node (ref "R15") (pin "1") (pinfunction "1_1") (pintype "passive"))
      (node (ref "R21") (pin "2") (pinfunction "2_2") (pintype "passive"))
      (node (ref "TP13") (pin "1") (pinfunction "1_1") (pintype "passive"))
    )
    (net (code "98") (name "Net-(Q1-VOUT-)") (class "Default")
      (node (ref "C1") (pin "1") (pinfunction "1_1") (pintype "passive"))
      (node (ref "Q1") (pin "6") (pinfunction "VOUT-_6") (pintype "passive"))
      (node (ref "R22") (pin "2") (pinfunction "2_2") (pintype "passive"))
      (node (ref "R25") (pin "1") (pinfunction "1_1") (pintype "passive"))
      (node (ref "TP18") (pin "1") (pinfunction "1_1") (pintype "passive"))
    )
    (net (code "99") (name "Net-(Q2-GND1)") (class "Default")
      (node (ref "C7") (pin "2") (pinfunction "2_2") (pintype "passive"))
      (node (ref "C8") (pin "2") (pinfunction "2_2") (pintype "passive"))
      (node (ref "Q2") (pin "4") (pinfunction "GND1_4") (pintype "power_in"))
      (node (ref "R116") (pin "1") (pinfunction "1_1") (pintype "passive"))
      (node (ref "R119") (pin "2") (pinfunction "2_2") (pintype "passive"))
    )
    (net (code "100") (name "Net-(Q2-SHDN)") (class "Default")
      (node (ref "Q2") (pin "3") (pinfunction "SHDN_3") (pintype "input"))
      (node (ref "R32") (pin "2") (pinfunction "2_2") (pintype "passive"))
    )
    (net (code "101") (name "Net-(Q2-VDD2)") (class "Default")
      (node (ref "C4") (pin "1") (pinfunction "1_1") (pintype "passive"))
      (node (ref "C57") (pin "1") (pinfunction "1_1") (pintype "passive"))
      (node (ref "Q2") (pin "8") (pinfunction "VDD2_8") (pintype "power_in"))
      (node (ref "R90") (pin "1") (pinfunction "1_1") (pintype "passive"))
      (node (ref "R91") (pin "1") (pinfunction "1_1") (pintype "passive"))
    )
    (net (code "102") (name "Net-(Q2-VIN)") (class "Default")
      (node (ref "C7") (pin "1") (pinfunction "1_1") (pintype "passive"))
      (node (ref "Q2") (pin "2") (pinfunction "VIN_2") (pintype "power_in"))
      (node (ref "R10") (pin "1") (pinfunction "1_1") (pintype "passive"))
      (node (ref "R13") (pin "2") (pinfunction "2_2") (pintype "passive"))
      (node (ref "R14") (pin "2") (pinfunction "2_2") (pintype "passive"))
      (node (ref "R9") (pin "1") (pinfunction "1_1") (pintype "passive"))
      (node (ref "TP11") (pin "1") (pinfunction "1_1") (pintype "passive"))
    )
    (net (code "103") (name "Net-(Q2-VOUT+)") (class "Default")
      (node (ref "Q2") (pin "7") (pinfunction "VOUT+_7") (pintype "passive"))
      (node (ref "R16") (pin "1") (pinfunction "1_1") (pintype "passive"))
      (node (ref "R23") (pin "2") (pinfunction "2_2") (pintype "passive"))
      (node (ref "TP15") (pin "1") (pinfunction "1_1") (pintype "passive"))
    )
    (net (code "104") (name "Net-(Q2-VOUT-)") (class "Default")
      (node (ref "C2") (pin "1") (pinfunction "1_1") (pintype "passive"))
      (node (ref "Q2") (pin "6") (pinfunction "VOUT-_6") (pintype "passive"))
      (node (ref "R24") (pin "2") (pinfunction "2_2") (pintype "passive"))
      (node (ref "R27") (pin "1") (pinfunction "1_1") (pintype "passive"))
      (node (ref "TP17") (pin "1") (pinfunction "1_1") (pintype "passive"))
    )
    (net (code "105") (name "Net-(Q5-C)") (class "Default")
      (node (ref "Q5") (pin "3") (pinfunction "C_3") (pintype "passive"))
      (node (ref "R135") (pin "2") (pinfunction "2_2") (pintype "passive"))
      (node (ref "Trans1") (pin "1") (pinfunction "ANODE_1") (pintype "passive"))
    )
    (net (code "106") (name "Net-(R17-Pad1)") (class "Default")
      (node (ref "R17") (pin "1") (pinfunction "1_1") (pintype "passive"))
      (node (ref "R18") (pin "2") (pinfunction "2_2") (pintype "passive"))
    )
    (net (code "107") (name "Net-(R18-Pad1)") (class "Default")
      (node (ref "R18") (pin "1") (pinfunction "1_1") (pintype "passive"))
      (node (ref "R26") (pin "1") (pinfunction "1_1") (pintype "passive"))
      (node (ref "R29") (pin "1") (pinfunction "1_1") (pintype "passive"))
    )
    (net (code "108") (name "Net-(R19-Pad1)") (class "Default")
      (node (ref "R19") (pin "1") (pinfunction "1_1") (pintype "passive"))
      (node (ref "R20") (pin "2") (pinfunction "2_2") (pintype "passive"))
    )
    (net (code "109") (name "Net-(R20-Pad1)") (class "Default")
      (node (ref "R20") (pin "1") (pinfunction "1_1") (pintype "passive"))
      (node (ref "R28") (pin "1") (pinfunction "1_1") (pintype "passive"))
      (node (ref "R30") (pin "1") (pinfunction "1_1") (pintype "passive"))
    )
    (net (code "110") (name "Net-(R29-Pad2)") (class "Default")
      (node (ref "R29") (pin "2") (pinfunction "2_2") (pintype "passive"))
      (node (ref "R36") (pin "1") (pinfunction "1_1") (pintype "passive"))
      (node (ref "R43") (pin "1") (pinfunction "1_1") (pintype "passive"))
      (node (ref "R93") (pin "2") (pinfunction "2_2") (pintype "passive"))
    )
    (net (code "111") (name "Net-(R30-Pad2)") (class "Default")
      (node (ref "R30") (pin "2") (pinfunction "2_2") (pintype "passive"))
      (node (ref "R38") (pin "1") (pinfunction "1_1") (pintype "passive"))
      (node (ref "R44") (pin "1") (pinfunction "1_1") (pintype "passive"))
      (node (ref "R92") (pin "2") (pinfunction "2_2") (pintype "passive"))
    )
    (net (code "112") (name "Net-(R35-Pad1)") (class "Default")
      (node (ref "R35") (pin "1") (pinfunction "1_1") (pintype "passive"))
      (node (ref "R36") (pin "2") (pinfunction "2_2") (pintype "passive"))
    )
    (net (code "113") (name "Net-(R37-Pad1)") (class "Default")
      (node (ref "R37") (pin "1") (pinfunction "1_1") (pintype "passive"))
      (node (ref "R38") (pin "2") (pinfunction "2_2") (pintype "passive"))
    )
    (net (code "114") (name "Net-(R55-Pad2)") (class "Default")
      (node (ref "R55") (pin "2") (pinfunction "2_2") (pintype "passive"))
      (node (ref "U7") (pin "11") (pinfunction "OUT_11") (pintype "passive"))
    )
    (net (code "115") (name "Net-(R58-Pad2)") (class "Default")
      (node (ref "R58") (pin "2") (pinfunction "2_2") (pintype "passive"))
      (node (ref "R62") (pin "1") (pinfunction "1_1") (pintype "passive"))
      (node (ref "R65") (pin "2") (pinfunction "2_2") (pintype "passive"))
    )
    (net (code "116") (name "Net-(R106-Pad2)") (class "Default")
      (node (ref "R106") (pin "2") (pinfunction "2_2") (pintype "passive"))
      (node (ref "R110") (pin "1") (pinfunction "1_1") (pintype "passive"))
    )
    (net (code "117") (name "Net-(R107-Pad2)") (class "Default")
      (node (ref "R107") (pin "2") (pinfunction "2_2") (pintype "passive"))
      (node (ref "R111") (pin "1") (pinfunction "1_1") (pintype "passive"))
    )
    (net (code "118") (name "Net-(R108-Pad2)") (class "Default")
      (node (ref "R108") (pin "2") (pinfunction "2_2") (pintype "passive"))
      (node (ref "R109") (pin "2") (pinfunction "2_2") (pintype "passive"))
      (node (ref "R112") (pin "1") (pinfunction "1_1") (pintype "passive"))
      (node (ref "R113") (pin "1") (pinfunction "1_1") (pintype "passive"))
    )
    (net (code "119") (name "Net-(R121-Pad2)") (class "Default")
      (node (ref "R121") (pin "2") (pinfunction "2_2") (pintype "passive"))
      (node (ref "R122") (pin "1") (pinfunction "1_1") (pintype "passive"))
    )
    (net (code "120") (name "Net-(R123-Pad1)") (class "Default")
      (node (ref "R123") (pin "1") (pinfunction "1_1") (pintype "passive"))
      (node (ref "R55") (pin "1") (pinfunction "1_1") (pintype "passive"))
      (node (ref "R56") (pin "2") (pinfunction "2_2") (pintype "passive"))
      (node (ref "TP46") (pin "1") (pinfunction "1_1") (pintype "passive"))
    )
    (net (code "121") (name "Net-(R130-Pad1)") (class "Default")
      (node (ref "R130") (pin "1") (pinfunction "1_1") (pintype "passive"))
      (node (ref "R131") (pin "1") (pinfunction "1_1") (pintype "passive"))
      (node (ref "S1") (pin "3") (pinfunction "3_3") (pintype "passive"))
    )
    (net (code "122") (name "Net-(U8-A)") (class "Default")
      (node (ref "R59") (pin "2") (pinfunction "2_2") (pintype "passive"))
      (node (ref "U8") (pin "2") (pinfunction "A_2") (pintype "input"))
    )
    (net (code "123") (name "Net-(U8-NC)") (class "Default")
      (node (ref "R64") (pin "2") (pinfunction "2_2") (pintype "passive"))
      (node (ref "U8") (pin "1") (pinfunction "NC_1") (pintype "passive"))
    )
    (net (code "124") (name "Net-(U8-VCC)") (class "Default")
      (node (ref "C64") (pin "1") (pinfunction "1_1") (pintype "passive"))
      (node (ref "R57") (pin "2") (pinfunction "2_2") (pintype "passive"))
      (node (ref "R97") (pin "1") (pinfunction "1_1") (pintype "passive"))
      (node (ref "U8") (pin "5") (pinfunction "VCC_5") (pintype "power_in"))
    )
    (net (code "125") (name "Net-(U9-ANODE)") (class "Default")
      (node (ref "R132") (pin "1") (pinfunction "1_1") (pintype "passive"))
      (node (ref "R60") (pin "2") (pinfunction "2_2") (pintype "passive"))
      (node (ref "U9") (pin "1") (pinfunction "ANODE_1") (pintype "passive"))
    )
    (net (code "126") (name "Net-(U9-NC)") (class "Default")
      (node (ref "R66") (pin "2") (pinfunction "2_2") (pintype "passive"))
      (node (ref "U9") (pin "2") (pinfunction "NC_2") (pintype "passive"))
    )
    (net (code "127") (name "Net-(U10-IN)") (class "Default")
      (node (ref "R61") (pin "2") (pinfunction "2_2") (pintype "passive"))
      (node (ref "U10") (pin "2") (pinfunction "IN_2") (pintype "input"))
    )
    (net (code "128") (name "Net-(U10-NC)") (class "Default")
      (node (ref "R71") (pin "2") (pinfunction "2_2") (pintype "passive"))
      (node (ref "U10") (pin "3") (pinfunction "NC_3") (pintype "passive"))
    )
    (net (code "129") (name "Net-(U11-IN)") (class "Default")
      (node (ref "C30") (pin "2") (pinfunction "2_2") (pintype "passive"))
      (node (ref "C31") (pin "2") (pinfunction "2_2") (pintype "passive"))
      (node (ref "FB2") (pin "2") (pinfunction "2_2") (pintype "power_in"))
      (node (ref "U11") (pin "1") (pinfunction "~{SHDN}_1") (pintype "input"))
      (node (ref "U11") (pin "2") (pinfunction "IN_2") (pintype "power_in"))
    )
    (net (code "130") (name "Net-(U13-VOUT)") (class "Default")
      (node (ref "C41") (pin "2") (pinfunction "2_2") (pintype "passive"))
      (node (ref "FB3") (pin "1") (pinfunction "1_1") (pintype "power_in"))
      (node (ref "U13") (pin "2") (pinfunction "VOUT_2") (pintype "passive"))
    )
    (net (code "131") (name "Net-(U14-A)") (class "Default")
      (node (ref "R74") (pin "2") (pinfunction "2_2") (pintype "passive"))
      (node (ref "U14") (pin "2") (pinfunction "A_2") (pintype "input"))
    )
    (net (code "132") (name "Net-(U14-NC)") (class "Default")
      (node (ref "R78") (pin "2") (pinfunction "2_2") (pintype "passive"))
      (node (ref "U14") (pin "1") (pinfunction "NC_1") (pintype "passive"))
    )
    (net (code "133") (name "Net-(U14-VCC)") (class "Default")
      (node (ref "C62") (pin "1") (pinfunction "1_1") (pintype "passive"))
      (node (ref "R72") (pin "2") (pinfunction "2_2") (pintype "passive"))
      (node (ref "R94") (pin "1") (pinfunction "1_1") (pintype "passive"))
      (node (ref "U14") (pin "5") (pinfunction "VCC_5") (pintype "power_in"))
    )
    (net (code "134") (name "Net-(U15-A)") (class "Default")
      (node (ref "R76") (pin "2") (pinfunction "2_2") (pintype "passive"))
      (node (ref "U15") (pin "2") (pinfunction "A_2") (pintype "input"))
    )
    (net (code "135") (name "Net-(U15-NC)") (class "Default")
      (node (ref "R79") (pin "2") (pinfunction "2_2") (pintype "passive"))
      (node (ref "U15") (pin "1") (pinfunction "NC_1") (pintype "passive"))
    )
    (net (code "136") (name "Net-(U15-VCC)") (class "Default")
      (node (ref "C63") (pin "1") (pinfunction "1_1") (pintype "passive"))
      (node (ref "R73") (pin "2") (pinfunction "2_2") (pintype "passive"))
      (node (ref "R95") (pin "1") (pinfunction "1_1") (pintype "passive"))
      (node (ref "U15") (pin "5") (pinfunction "VCC_5") (pintype "power_in"))
    )
    (net (code "137") (name "Net-(U16-A)") (class "Default")
      (node (ref "R77") (pin "2") (pinfunction "2_2") (pintype "passive"))
      (node (ref "U16") (pin "1") (pinfunction "A_1") (pintype "passive"))
    )
    (net (code "138") (name "Net-(U17-A)") (class "Default")
      (node (ref "R75") (pin "2") (pinfunction "2_2") (pintype "passive"))
      (node (ref "U17") (pin "1") (pinfunction "A_1") (pintype "passive"))
    )
    (net (code "139") (name "Net-(U17-C)") (class "Default")
      (node (ref "U17") (pin "4") (pinfunction "C_4") (pintype "passive"))
      (node (ref "U20") (pin "3") (pinfunction "3_3") (pintype "passive"))
    )
    (net (code "140") (name "Net-(U18-VIN)") (class "Default")
      (node (ref "C59") (pin "2") (pinfunction "2_2") (pintype "passive"))
      (node (ref "R123") (pin "2") (pinfunction "2_2") (pintype "passive"))
      (node (ref "U18") (pin "2") (pinfunction "VIN_2") (pintype "input"))
    )
    (net (code "141") (name "Net-(U18-VOUTN)") (class "Default")
      (node (ref "R124") (pin "1") (pinfunction "1_1") (pintype "passive"))
      (node (ref "TP58") (pin "1") (pinfunction "1_1") (pintype "passive"))
      (node (ref "U18") (pin "6") (pinfunction "VOUTN_6") (pintype "output"))
    )
    (net (code "142") (name "Net-(U18-VOUTP)") (class "Default")
      (node (ref "R127") (pin "1") (pinfunction "1_1") (pintype "passive"))
      (node (ref "TP55") (pin "1") (pinfunction "1_1") (pintype "passive"))
      (node (ref "U18") (pin "7") (pinfunction "VOUTP_7") (pintype "output"))
    )
    (net (code "143") (name "Net-(U19-IN+)") (class "Default")
      (node (ref "C65") (pin "2") (pinfunction "2_2") (pintype "passive"))
      (node (ref "R128") (pin "2") (pinfunction "2_2") (pintype "passive"))
      (node (ref "R129") (pin "2") (pinfunction "2_2") (pintype "passive"))
      (node (ref "TP57") (pin "1") (pinfunction "1_1") (pintype "passive"))
      (node (ref "U19") (pin "3") (pinfunction "IN+_3") (pintype "input"))
    )
    (net (code "144") (name "Net-(U19-IN-)") (class "Default")
      (node (ref "C46") (pin "2") (pinfunction "2_2") (pintype "passive"))
      (node (ref "R121") (pin "1") (pinfunction "1_1") (pintype "passive"))
      (node (ref "R125") (pin "2") (pinfunction "2_2") (pintype "passive"))
      (node (ref "TP54") (pin "1") (pinfunction "1_1") (pintype "passive"))
      (node (ref "U19") (pin "4") (pinfunction "IN-_4") (pintype "input"))
    )
    (net (code "145") (name "Net-(U19-OUT)") (class "Default")
      (node (ref "C46") (pin "1") (pinfunction "1_1") (pintype "passive"))
      (node (ref "R122") (pin "2") (pinfunction "2_2") (pintype "passive"))
      (node (ref "R126") (pin "1") (pinfunction "1_1") (pintype "passive"))
      (node (ref "U19") (pin "1") (pinfunction "OUT_1") (pintype "output"))
    )
    (net (code "146") (name "Output 500V") (class "Default")
      (node (ref "C18") (pin "1") (pinfunction "1_1") (pintype "passive"))
      (node (ref "C19") (pin "1") (pinfunction "1_1") (pintype "passive"))
      (node (ref "C20") (pin "1") (pinfunction "1_1") (pintype "passive"))
      (node (ref "C21") (pin "1") (pinfunction "1_1") (pintype "passive"))
      (node (ref "J6") (pin "1") (pinfunction "1_1") (pintype "passive"))
      (node (ref "L3") (pin "2") (pinfunction "2_2") (pintype "passive"))
      (node (ref "R10") (pin "2") (pinfunction "2_2") (pintype "passive"))
      (node (ref "R108") (pin "1") (pinfunction "1_1") (pintype "passive"))
      (node (ref "R109") (pin "1") (pinfunction "1_1") (pintype "passive"))
      (node (ref "R9") (pin "2") (pinfunction "2_2") (pintype "passive"))
      (node (ref "TP1") (pin "1") (pinfunction "1_1") (pintype "passive"))
      (node (ref "TP4") (pin "1") (pinfunction "1_1") (pintype "passive"))
    )
    (net (code "147") (name "Output Current of FB to micro controller") (class "Default")
      (node (ref "EC2") (pin "101") (pinfunction "101_101") (pintype "bidirectional"))
      (node (ref "J4") (pin "12") (pinfunction "12_12") (pintype "passive"))
    )
    (net (code "148") (name "Output Current to micro controller") (class "Default")
      (node (ref "EC2") (pin "104") (pinfunction "104_104") (pintype "bidirectional"))
      (node (ref "FB10") (pin "2") (pinfunction "2_2") (pintype "power_in"))
      (node (ref "J5") (pin "7") (pinfunction "7_7") (pintype "passive"))
    )
    (net (code "149") (name "Output voltage of Buck") (class "Default")
      (node (ref "EC2") (pin "110") (pinfunction "110_110") (pintype "bidirectional"))
      (node (ref "FB7") (pin "2") (pinfunction "2_2") (pintype "power_in"))
      (node (ref "J5") (pin "6") (pinfunction "6_6") (pintype "passive"))
      (node (ref "TP30") (pin "1") (pinfunction "1_1") (pintype "passive"))
    )
    (net (code "150") (name "Output voltage of FB") (class "Default")
      (node (ref "EC2") (pin "107") (pinfunction "107_107") (pintype "bidirectional"))
      (node (ref "J4") (pin "11") (pinfunction "11_11") (pintype "passive"))
    )
    (net (code "151") (name "P1 OP37") (class "Default")
      (node (ref "R17") (pin "2") (pinfunction "2_2") (pintype "passive"))
      (node (ref "U1") (pin "1") (pinfunction "OFFSET_TRIM_1") (pintype "input"))
    )
    (net (code "152") (name "P1 OP37-2") (class "Default")
      (node (ref "R19") (pin "2") (pinfunction "2_2") (pintype "passive"))
      (node (ref "U2") (pin "1") (pinfunction "OFFSET_TRIM_1") (pintype "input"))
    )
    (net (code "153") (name "P2 OP37") (class "Default")
      (node (ref "C11") (pin "1") (pinfunction "1_1") (pintype "passive"))
      (node (ref "R22") (pin "1") (pinfunction "1_1") (pintype "passive"))
      (node (ref "R25") (pin "2") (pinfunction "2_2") (pintype "passive"))
      (node (ref "R39") (pin "2") (pinfunction "2_2") (pintype "passive"))
      (node (ref "R40") (pin "2") (pinfunction "2_2") (pintype "passive"))
      (node (ref "U1") (pin "2") (pinfunction "IN-_2") (pintype "input"))
    )
    (net (code "154") (name "P2 OP37-2") (class "Default")
      (node (ref "C12") (pin "1") (pinfunction "1_1") (pintype "passive"))
      (node (ref "R24") (pin "1") (pinfunction "1_1") (pintype "passive"))
      (node (ref "R27") (pin "2") (pinfunction "2_2") (pintype "passive"))
      (node (ref "R41") (pin "2") (pinfunction "2_2") (pintype "passive"))
      (node (ref "R42") (pin "2") (pinfunction "2_2") (pintype "passive"))
      (node (ref "U2") (pin "2") (pinfunction "IN-_2") (pintype "input"))
    )
    (net (code "155") (name "P3 OP37") (class "Default")
      (node (ref "C9") (pin "1") (pinfunction "1_1") (pintype "passive"))
      (node (ref "R21") (pin "1") (pinfunction "1_1") (pintype "passive"))
      (node (ref "R33") (pin "1") (pinfunction "1_1") (pintype "passive"))
      (node (ref "U1") (pin "3") (pinfunction "IN+_3") (pintype "input"))
    )
    (net (code "156") (name "P3 OP37-2") (class "Default")
      (node (ref "C10") (pin "1") (pinfunction "1_1") (pintype "passive"))
      (node (ref "R23") (pin "1") (pinfunction "1_1") (pintype "passive"))
      (node (ref "R34") (pin "1") (pinfunction "1_1") (pintype "passive"))
      (node (ref "U2") (pin "3") (pinfunction "IN+_3") (pintype "input"))
    )
    (net (code "157") (name "P4 OP37") (class "Default")
      (node (ref "R3") (pin "1") (pinfunction "1_1") (pintype "passive"))
      (node (ref "U1") (pin "4") (pinfunction "VCC-_4") (pintype "power_in"))
    )
    (net (code "158") (name "P4 OP37-2") (class "Default")
      (node (ref "R4") (pin "1") (pinfunction "1_1") (pintype "passive"))
      (node (ref "U2") (pin "4") (pinfunction "VCC-_4") (pintype "power_in"))
    )
    (net (code "159") (name "P5 OP37") (class "Default")
      (node (ref "R5") (pin "1") (pinfunction "1_1") (pintype "passive"))
      (node (ref "U1") (pin "5") (pinfunction "NC_5") (pintype "passive"))
    )
    (net (code "160") (name "P5 OP37-2") (class "Default")
      (node (ref "R6") (pin "1") (pinfunction "1_1") (pintype "passive"))
      (node (ref "U2") (pin "5") (pinfunction "NC_5") (pintype "passive"))
    )
    (net (code "161") (name "P6 OP37") (class "Default")
      (node (ref "C11") (pin "2") (pinfunction "2_2") (pintype "passive"))
      (node (ref "C13") (pin "1") (pinfunction "1_1") (pintype "passive"))
      (node (ref "R39") (pin "1") (pinfunction "1_1") (pintype "passive"))
      (node (ref "R40") (pin "1") (pinfunction "1_1") (pintype "passive"))
      (node (ref "R45") (pin "1") (pinfunction "1_1") (pintype "passive"))
      (node (ref "TP19") (pin "1") (pinfunction "1_1") (pintype "passive"))
      (node (ref "U1") (pin "6") (pinfunction "OUT_6") (pintype "output"))
    )
    (net (code "162") (name "P6 OP37-2") (class "Default")
      (node (ref "C12") (pin "2") (pinfunction "2_2") (pintype "passive"))
      (node (ref "C14") (pin "1") (pinfunction "1_1") (pintype "passive"))
      (node (ref "R41") (pin "1") (pinfunction "1_1") (pintype "passive"))
      (node (ref "R42") (pin "1") (pinfunction "1_1") (pintype "passive"))
      (node (ref "R46") (pin "1") (pinfunction "1_1") (pintype "passive"))
      (node (ref "TP20") (pin "1") (pinfunction "1_1") (pintype "passive"))
      (node (ref "U2") (pin "6") (pinfunction "OUT_6") (pintype "output"))
    )
    (net (code "163") (name "P7 OP37") (class "Default")
      (node (ref "C55") (pin "1") (pinfunction "1_1") (pintype "passive"))
      (node (ref "R1") (pin "2") (pinfunction "2_2") (pintype "passive"))
      (node (ref "R87") (pin "2") (pinfunction "2_2") (pintype "passive"))
      (node (ref "U1") (pin "7") (pinfunction "VCC+_7") (pintype "power_in"))
    )
    (net (code "164") (name "P7 OP37-2") (class "Default")
      (node (ref "C56") (pin "1") (pinfunction "1_1") (pintype "passive"))
      (node (ref "R2") (pin "2") (pinfunction "2_2") (pintype "passive"))
      (node (ref "R86") (pin "2") (pinfunction "2_2") (pintype "passive"))
      (node (ref "U2") (pin "7") (pinfunction "VCC+_7") (pintype "power_in"))
    )
    (net (code "165") (name "P8 OP37") (class "Default")
      (node (ref "R35") (pin "2") (pinfunction "2_2") (pintype "passive"))
      (node (ref "U1") (pin "8") (pinfunction "OFFSET_TRIM_8") (pintype "input"))
    )
    (net (code "166") (name "P8 OP37-2") (class "Default")
      (node (ref "R37") (pin "2") (pinfunction "2_2") (pintype "passive"))
      (node (ref "U2") (pin "8") (pinfunction "OFFSET_TRIM_8") (pintype "input"))
    )
    (net (code "167") (name "Relay 2") (class "Default")
      (node (ref "D5") (pin "1") (pinfunction "A_1") (pintype "passive"))
      (node (ref "K1") (pin "A1") (pinfunction "A1_A1") (pintype "passive"))
      (node (ref "TP39") (pin "1") (pinfunction "1_1") (pintype "passive"))
      (node (ref "U16") (pin "4") (pinfunction "C_4") (pintype "passive"))
    )
    (net (code "168") (name "Relay FB command") (class "Default")
      (node (ref "EC2") (pin "16") (pinfunction "16_16") (pintype "bidirectional"))
      (node (ref "J4") (pin "3") (pinfunction "3_3") (pintype "passive"))
    )
    (net (code "169") (name "Relay command") (class "Default")
      (node (ref "EC2") (pin "54") (pinfunction "54_54") (pintype "bidirectional"))
      (node (ref "FB5") (pin "1") (pinfunction "1_1") (pintype "power_in"))
      (node (ref "J5") (pin "11") (pinfunction "11_11") (pintype "passive"))
      (node (ref "R100") (pin "1") (pinfunction "1_1") (pintype "passive"))
      (node (ref "TP36") (pin "1") (pinfunction "1_1") (pintype "passive"))
    )
    (net (code "170") (name "Spare Analog FB 1") (class "Default")
      (node (ref "J4") (pin "10") (pinfunction "10_10") (pintype "passive"))
      (node (ref "Rj10") (pin "2") (pinfunction "2_2") (pintype "passive"))
    )
    (net (code "171") (name "Spare Analog FB 2") (class "Default")
      (node (ref "J4") (pin "22") (pinfunction "22_22") (pintype "passive"))
      (node (ref "Rj12") (pin "1") (pinfunction "1_1") (pintype "passive"))
    )
    (net (code "172") (name "Spare Analog FB 3") (class "Default")
      (node (ref "J4") (pin "9") (pinfunction "9_9") (pintype "passive"))
      (node (ref "Rj11") (pin "1") (pinfunction "1_1") (pintype "passive"))
    )
    (net (code "173") (name "Spare Analog FB 4") (class "Default")
      (node (ref "J4") (pin "21") (pinfunction "21_21") (pintype "passive"))
      (node (ref "Rj9") (pin "1") (pinfunction "1_1") (pintype "passive"))
    )
    (net (code "174") (name "Spare Dig FB 1") (class "Default")
      (node (ref "J4") (pin "19") (pinfunction "19_19") (pintype "passive"))
      (node (ref "Rj1") (pin "1") (pinfunction "1_1") (pintype "passive"))
    )
    (net (code "175") (name "Spare Dig FB 2") (class "Default")
      (node (ref "J4") (pin "7") (pinfunction "7_7") (pintype "passive"))
      (node (ref "Rj2") (pin "1") (pinfunction "1_1") (pintype "passive"))
    )
    (net (code "176") (name "Spare Dig FB 3") (class "Default")
      (node (ref "J4") (pin "20") (pinfunction "20_20") (pintype "passive"))
      (node (ref "Rj3") (pin "1") (pinfunction "1_1") (pintype "passive"))
    )
    (net (code "177") (name "Spare Dig FB 4") (class "Default")
      (node (ref "J4") (pin "8") (pinfunction "8_8") (pintype "passive"))
      (node (ref "Rj4") (pin "1") (pinfunction "1_1") (pintype "passive"))
    )
    (net (code "178") (name "TEMP") (class "Default")
      (node (ref "EC2") (pin "98") (pinfunction "98_98") (pintype "bidirectional"))
      (node (ref "FB8") (pin "2") (pinfunction "2_2") (pintype "power_in"))
      (node (ref "J5") (pin "5") (pinfunction "5_5") (pintype "passive"))
    )
    (net (code "179") (name "TEMP of the heatsink") (class "Default")
      (node (ref "EC2") (pin "112") (pinfunction "112_112") (pintype "bidirectional"))
      (node (ref "FB9") (pin "2") (pinfunction "2_2") (pintype "power_in"))
      (node (ref "J5") (pin "13") (pinfunction "13_13") (pintype "passive"))
    )
    (net (code "180") (name "VDD Sensor voltage input") (class "Default")
      (node (ref "C37") (pin "1") (pinfunction "1_1") (pintype "passive"))
      (node (ref "C6") (pin "1") (pinfunction "1_1") (pintype "passive"))
      (node (ref "DS9") (pin "1") (pinfunction "A_1") (pintype "passive"))
      (node (ref "Q1") (pin "1") (pinfunction "VDD1_1") (pintype "power_in"))
      (node (ref "TP10") (pin "1") (pinfunction "1_1") (pintype "passive"))
      (node (ref "TP16") (pin "1") (pinfunction "1_1") (pintype "passive"))
      (node (ref "U5") (pin "3") (pinfunction "+Out_3") (pintype "passive"))
    )
    (net (code "181") (name "VDD Sensor voltage out") (class "Default")
      (node (ref "C39") (pin "1") (pinfunction "1_1") (pintype "passive"))
      (node (ref "C8") (pin "1") (pinfunction "1_1") (pintype "passive"))
      (node (ref "DS8") (pin "1") (pinfunction "A_1") (pintype "passive"))
      (node (ref "Q2") (pin "1") (pinfunction "VDD1_1") (pintype "power_in"))
      (node (ref "TP22") (pin "1") (pinfunction "1_1") (pintype "passive"))
      (node (ref "U6") (pin "3") (pinfunction "+Out_3") (pintype "passive"))
    )
    (net (code "182") (name "VGS B") (class "Default")
      (node (ref "C34") (pin "1") (pinfunction "1_1") (pintype "passive"))
      (node (ref "C45") (pin "2") (pinfunction "2_2") (pintype "passive"))
      (node (ref "C53") (pin "1") (pinfunction "1_1") (pintype "passive"))
      (node (ref "C54") (pin "1") (pinfunction "1_1") (pintype "passive"))
      (node (ref "C66") (pin "1") (pinfunction "1_1") (pintype "passive"))
      (node (ref "C67") (pin "1") (pinfunction "1_1") (pintype "passive"))
      (node (ref "CR6") (pin "2") (pinfunction "K_2") (pintype "passive"))
      (node (ref "CR9") (pin "2") (pinfunction "K_2") (pintype "passive"))
      (node (ref "DS7") (pin "1") (pinfunction "A_1") (pintype "passive"))
      (node (ref "TP5") (pin "1") (pinfunction "1_1") (pintype "passive"))
      (node (ref "U10") (pin "1") (pinfunction "VCC_1") (pintype "power_in"))
      (node (ref "U10") (pin "8") (pinfunction "VCC_8") (pintype "power_in"))
      (node (ref "U3") (pin "3") (pinfunction "+Out_3") (pintype "passive"))
      (node (ref "U9") (pin "6") (pinfunction "VDD_6") (pintype "power_in"))
    )
    (net (code "183") (name "unconnected-(EC2-121-PadG1)") (class "Default")
      (node (ref "EC2") (pin "G1") (pinfunction "121_G1") (pintype "bidirectional"))
    )
    (net (code "184") (name "unconnected-(EC2-Pad2)") (class "Default")
      (node (ref "EC2") (pin "2") (pinfunction "2_2") (pintype "bidirectional"))
    )
    (net (code "185") (name "unconnected-(EC2-Pad3)") (class "Default")
      (node (ref "EC2") (pin "3") (pinfunction "3_3") (pintype "bidirectional"))
    )
    (net (code "186") (name "unconnected-(EC2-Pad4)") (class "Default")
      (node (ref "EC2") (pin "4") (pinfunction "4_4") (pintype "bidirectional"))
    )
    (net (code "187") (name "unconnected-(EC2-Pad5)") (class "Default")
      (node (ref "EC2") (pin "5") (pinfunction "5_5") (pintype "bidirectional"))
    )
    (net (code "188") (name "unconnected-(EC2-Pad6)") (class "Default")
      (node (ref "EC2") (pin "6") (pinfunction "6_6") (pintype "bidirectional"))
    )
    (net (code "189") (name "unconnected-(EC2-Pad7)") (class "Default")
      (node (ref "EC2") (pin "7") (pinfunction "7_7") (pintype "bidirectional"))
    )
    (net (code "190") (name "unconnected-(EC2-Pad8)") (class "Default")
      (node (ref "EC2") (pin "8") (pinfunction "8_8") (pintype "bidirectional"))
    )
    (net (code "191") (name "unconnected-(EC2-Pad11)") (class "Default")
      (node (ref "EC2") (pin "11") (pinfunction "11_11") (pintype "bidirectional"))
    )
    (net (code "192") (name "unconnected-(EC2-Pad12)") (class "Default")
      (node (ref "EC2") (pin "12") (pinfunction "12_12") (pintype "bidirectional"))
    )
    (net (code "193") (name "unconnected-(EC2-Pad13)") (class "Default")
      (node (ref "EC2") (pin "13") (pinfunction "13_13") (pintype "bidirectional"))
    )
    (net (code "194") (name "unconnected-(EC2-Pad14)") (class "Default")
      (node (ref "EC2") (pin "14") (pinfunction "14_14") (pintype "bidirectional"))
    )
    (net (code "195") (name "unconnected-(EC2-Pad15)") (class "Default")
      (node (ref "EC2") (pin "15") (pinfunction "15_15") (pintype "bidirectional"))
    )
    (net (code "196") (name "unconnected-(EC2-Pad17)") (class "Default")
      (node (ref "EC2") (pin "17") (pinfunction "17_17") (pintype "bidirectional"))
    )
    (net (code "197") (name "unconnected-(EC2-Pad19)") (class "Default")
      (node (ref "EC2") (pin "19") (pinfunction "19_19") (pintype "bidirectional"))
    )
    (net (code "198") (name "unconnected-(EC2-Pad20)") (class "Default")
      (node (ref "EC2") (pin "20") (pinfunction "20_20") (pintype "bidirectional"))
    )
    (net (code "199") (name "unconnected-(EC2-Pad21)") (class "Default")
      (node (ref "EC2") (pin "21") (pinfunction "21_21") (pintype "bidirectional"))
    )
    (net (code "200") (name "unconnected-(EC2-Pad22)") (class "Default")
      (node (ref "EC2") (pin "22") (pinfunction "22_22") (pintype "bidirectional"))
    )
    (net (code "201") (name "unconnected-(EC2-Pad25)") (class "Default")
      (node (ref "EC2") (pin "25") (pinfunction "25_25") (pintype "bidirectional"))
    )
    (net (code "202") (name "unconnected-(EC2-Pad26)") (class "Default")
      (node (ref "EC2") (pin "26") (pinfunction "26_26") (pintype "bidirectional"))
    )
    (net (code "203") (name "unconnected-(EC2-Pad27)") (class "Default")
      (node (ref "EC2") (pin "27") (pinfunction "27_27") (pintype "bidirectional"))
    )
    (net (code "204") (name "unconnected-(EC2-Pad28)") (class "Default")
      (node (ref "EC2") (pin "28") (pinfunction "28_28") (pintype "bidirectional"))
    )
    (net (code "205") (name "unconnected-(EC2-Pad29)") (class "Default")
      (node (ref "EC2") (pin "29") (pinfunction "29_29") (pintype "bidirectional"))
    )
    (net (code "206") (name "unconnected-(EC2-Pad30)") (class "Default")
      (node (ref "EC2") (pin "30") (pinfunction "30_30") (pintype "bidirectional"))
    )
    (net (code "207") (name "unconnected-(EC2-Pad31)") (class "Default")
      (node (ref "EC2") (pin "31") (pinfunction "31_31") (pintype "bidirectional"))
    )
    (net (code "208") (name "unconnected-(EC2-Pad32)") (class "Default")
      (node (ref "EC2") (pin "32") (pinfunction "32_32") (pintype "bidirectional"))
    )
    (net (code "209") (name "unconnected-(EC2-Pad33)") (class "Default")
      (node (ref "EC2") (pin "33") (pinfunction "33_33") (pintype "bidirectional"))
    )
    (net (code "210") (name "unconnected-(EC2-Pad35)") (class "Default")
      (node (ref "EC2") (pin "35") (pinfunction "35_35") (pintype "bidirectional"))
    )
    (net (code "211") (name "unconnected-(EC2-Pad39)") (class "Default")
      (node (ref "EC2") (pin "39") (pinfunction "39_39") (pintype "bidirectional"))
    )
    (net (code "212") (name "unconnected-(EC2-Pad41)") (class "Default")
      (node (ref "EC2") (pin "41") (pinfunction "41_41") (pintype "bidirectional"))
    )
    (net (code "213") (name "unconnected-(EC2-Pad43)") (class "Default")
      (node (ref "EC2") (pin "43") (pinfunction "43_43") (pintype "bidirectional"))
    )
    (net (code "214") (name "unconnected-(EC2-Pad44)") (class "Default")
      (node (ref "EC2") (pin "44") (pinfunction "44_44") (pintype "bidirectional"))
    )
    (net (code "215") (name "unconnected-(EC2-Pad45)") (class "Default")
      (node (ref "EC2") (pin "45") (pinfunction "45_45") (pintype "bidirectional"))
    )
    (net (code "216") (name "unconnected-(EC2-Pad46)") (class "Default")
      (node (ref "EC2") (pin "46") (pinfunction "46_46") (pintype "bidirectional"))
    )
    (net (code "217") (name "unconnected-(EC2-Pad47)") (class "Default")
      (node (ref "EC2") (pin "47") (pinfunction "47_47") (pintype "bidirectional"))
    )
    (net (code "218") (name "unconnected-(EC2-Pad48)") (class "Default")
      (node (ref "EC2") (pin "48") (pinfunction "48_48") (pintype "bidirectional"))
    )
    (net (code "219") (name "unconnected-(EC2-Pad49)") (class "Default")
      (node (ref "EC2") (pin "49") (pinfunction "49_49") (pintype "bidirectional"))
    )
    (net (code "220") (name "unconnected-(EC2-Pad50)") (class "Default")
      (node (ref "EC2") (pin "50") (pinfunction "50_50") (pintype "bidirectional"))
    )
    (net (code "221") (name "unconnected-(EC2-Pad51)") (class "Default")
      (node (ref "EC2") (pin "51") (pinfunction "51_51") (pintype "bidirectional"))
    )
    (net (code "222") (name "unconnected-(EC2-Pad52)") (class "Default")
      (node (ref "EC2") (pin "52") (pinfunction "52_52") (pintype "bidirectional"))
    )
    (net (code "223") (name "unconnected-(EC2-Pad53)") (class "Default")
      (node (ref "EC2") (pin "53") (pinfunction "53_53") (pintype "bidirectional"))
    )
    (net (code "224") (name "unconnected-(EC2-Pad55)") (class "Default")
      (node (ref "EC2") (pin "55") (pinfunction "55_55") (pintype "bidirectional"))
    )
    (net (code "225") (name "unconnected-(EC2-Pad58)") (class "Default")
      (node (ref "EC2") (pin "58") (pinfunction "58_58") (pintype "bidirectional"))
    )
    (net (code "226") (name "unconnected-(EC2-Pad61)") (class "Default")
      (node (ref "EC2") (pin "61") (pinfunction "61_61") (pintype "bidirectional"))
    )
    (net (code "227") (name "unconnected-(EC2-Pad62)") (class "Default")
      (node (ref "EC2") (pin "62") (pinfunction "62_62") (pintype "bidirectional"))
    )
    (net (code "228") (name "unconnected-(EC2-Pad63)") (class "Default")
      (node (ref "EC2") (pin "63") (pinfunction "63_63") (pintype "bidirectional"))
    )
    (net (code "229") (name "unconnected-(EC2-Pad76)") (class "Default")
      (node (ref "EC2") (pin "76") (pinfunction "76_76") (pintype "bidirectional"))
    )
    (net (code "230") (name "unconnected-(EC2-Pad77)") (class "Default")
      (node (ref "EC2") (pin "77") (pinfunction "77_77") (pintype "bidirectional"))
    )
    (net (code "231") (name "unconnected-(EC2-Pad78)") (class "Default")
      (node (ref "EC2") (pin "78") (pinfunction "78_78") (pintype "bidirectional"))
    )
    (net (code "232") (name "unconnected-(EC2-Pad79)") (class "Default")
      (node (ref "EC2") (pin "79") (pinfunction "79_79") (pintype "bidirectional"))
    )
    (net (code "233") (name "unconnected-(EC2-Pad80)") (class "Default")
      (node (ref "EC2") (pin "80") (pinfunction "80_80") (pintype "bidirectional"))
    )
    (net (code "234") (name "unconnected-(EC2-Pad81)") (class "Default")
      (node (ref "EC2") (pin "81") (pinfunction "81_81") (pintype "bidirectional"))
    )
    (net (code "235") (name "unconnected-(EC2-Pad82)") (class "Default")
      (node (ref "EC2") (pin "82") (pinfunction "82_82") (pintype "bidirectional"))
    )
    (net (code "236") (name "unconnected-(EC2-Pad84)") (class "Default")
      (node (ref "EC2") (pin "84") (pinfunction "84_84") (pintype "bidirectional"))
    )
    (net (code "237") (name "unconnected-(EC2-Pad85)") (class "Default")
      (node (ref "EC2") (pin "85") (pinfunction "85_85") (pintype "bidirectional"))
    )
    (net (code "238") (name "unconnected-(EC2-Pad87)") (class "Default")
      (node (ref "EC2") (pin "87") (pinfunction "87_87") (pintype "bidirectional"))
    )
    (net (code "239") (name "unconnected-(EC2-Pad88)") (class "Default")
      (node (ref "EC2") (pin "88") (pinfunction "88_88") (pintype "bidirectional"))
    )
    (net (code "240") (name "unconnected-(EC2-Pad89)") (class "Default")
      (node (ref "EC2") (pin "89") (pinfunction "89_89") (pintype "bidirectional"))
    )
    (net (code "241") (name "unconnected-(EC2-Pad90)") (class "Default")
      (node (ref "EC2") (pin "90") (pinfunction "90_90") (pintype "bidirectional"))
    )
    (net (code "242") (name "unconnected-(EC2-Pad91)") (class "Default")
      (node (ref "EC2") (pin "91") (pinfunction "91_91") (pintype "bidirectional"))
    )
    (net (code "243") (name "unconnected-(EC2-Pad93)") (class "Default")
      (node (ref "EC2") (pin "93") (pinfunction "93_93") (pintype "bidirectional"))
    )
    (net (code "244") (name "unconnected-(EC2-Pad113)") (class "Default")
      (node (ref "EC2") (pin "113") (pinfunction "113_113") (pintype "bidirectional"))
    )
    (net (code "245") (name "unconnected-(EC2-Pad115)") (class "Default")
      (node (ref "EC2") (pin "115") (pinfunction "115_115") (pintype "bidirectional"))
    )
    (net (code "246") (name "unconnected-(EC2-Pad116)") (class "Default")
      (node (ref "EC2") (pin "116") (pinfunction "116_116") (pintype "bidirectional"))
    )
    (net (code "247") (name "unconnected-(EC2-Pad117)") (class "Default")
      (node (ref "EC2") (pin "117") (pinfunction "117_117") (pintype "bidirectional"))
    )
    (net (code "248") (name "unconnected-(EC2-Pad118)") (class "Default")
      (node (ref "EC2") (pin "118") (pinfunction "118_118") (pintype "bidirectional"))
    )
    (net (code "249") (name "unconnected-(EC2-Pad119)") (class "Default")
      (node (ref "EC2") (pin "119") (pinfunction "119_119") (pintype "bidirectional"))
    )
    (net (code "250") (name "unconnected-(EC2-Pad120)") (class "Default")
      (node (ref "EC2") (pin "120") (pinfunction "120_120") (pintype "bidirectional"))
    )
    (net (code "251") (name "unconnected-(J4-PadM1)") (class "Default")
      (node (ref "J4") (pin "M1") (pinfunction "M1_M1") (pintype "passive"))
    )
    (net (code "252") (name "unconnected-(J4-PadM2)") (class "Default")
      (node (ref "J4") (pin "M2") (pinfunction "M2_M2") (pintype "passive"))
    )
    (net (code "253") (name "unconnected-(J5-PadM1)") (class "Default")
      (node (ref "J5") (pin "M1") (pinfunction "M1_M1") (pintype "passive"))
    )
    (net (code "254") (name "unconnected-(J5-PadM2)") (class "Default")
      (node (ref "J5") (pin "M2") (pinfunction "M2_M2") (pintype "passive"))
    )
    (net (code "255") (name "unconnected-(OK1A-Open-Pad3)") (class "Default")
      (node (ref "OK1") (pin "3") (pinfunction "Open_3") (pintype "passive"))
    )
    (net (code "256") (name "unconnected-(U3-on{slash}off-Pad6)") (class "Default")
      (node (ref "U3") (pin "6") (pinfunction "on/off_6") (pintype "passive"))
    )
    (net (code "257") (name "unconnected-(U3-trim-Pad4)") (class "Default")
      (node (ref "U3") (pin "4") (pinfunction "trim_4") (pintype "passive"))
    )
    (net (code "258") (name "unconnected-(U4-Pad1)") (class "Default")
      (node (ref "U4") (pin "1") (pinfunction "1_1") (pintype "passive"))
    )
    (net (code "259") (name "unconnected-(U4-Pad2)") (class "Default")
      (node (ref "U4") (pin "2") (pinfunction "2_2") (pintype "passive"))
    )
    (net (code "260") (name "unconnected-(U4-Pad3)") (class "Default")
      (node (ref "U4") (pin "3") (pinfunction "3_3") (pintype "passive"))
    )
    (net (code "261") (name "unconnected-(U4-Pad4)") (class "Default")
      (node (ref "U4") (pin "4") (pinfunction "4_4") (pintype "passive"))
    )
    (net (code "262") (name "unconnected-(U4-Pad5)") (class "Default")
      (node (ref "U4") (pin "5") (pinfunction "5_5") (pintype "passive"))
    )
    (net (code "263") (name "unconnected-(U4-Pad6)") (class "Default")
      (node (ref "U4") (pin "6") (pinfunction "6_6") (pintype "passive"))
    )
    (net (code "264") (name "unconnected-(U5-on{slash}off-Pad6)") (class "Default")
      (node (ref "U5") (pin "6") (pinfunction "on/off_6") (pintype "passive"))
    )
    (net (code "265") (name "unconnected-(U5-trim-Pad4)") (class "Default")
      (node (ref "U5") (pin "4") (pinfunction "trim_4") (pintype "passive"))
    )
    (net (code "266") (name "unconnected-(U6-on{slash}off-Pad6)") (class "Default")
      (node (ref "U6") (pin "6") (pinfunction "on/off_6") (pintype "passive"))
    )
    (net (code "267") (name "unconnected-(U6-trim-Pad4)") (class "Default")
      (node (ref "U6") (pin "4") (pinfunction "trim_4") (pintype "passive"))
    )
    (net (code "268") (name "unconnected-(U12-on{slash}off-Pad6)") (class "Default")
      (node (ref "U12") (pin "6") (pinfunction "on/off_6") (pintype "passive+no_connect"))
    )
    (net (code "269") (name "unconnected-(U12-trim-Pad4)") (class "Default")
      (node (ref "U12") (pin "4") (pinfunction "trim_4") (pintype "passive+no_connect"))
    )
    (net (code "270") (name "unconnected-(U20-Pad8)") (class "Default")
      (node (ref "U20") (pin "8") (pinfunction "8_8") (pintype "passive"))
    )
  )
)
